# CPU_Power.net
KiCad netlist of a schematic drawn in Altium Designer
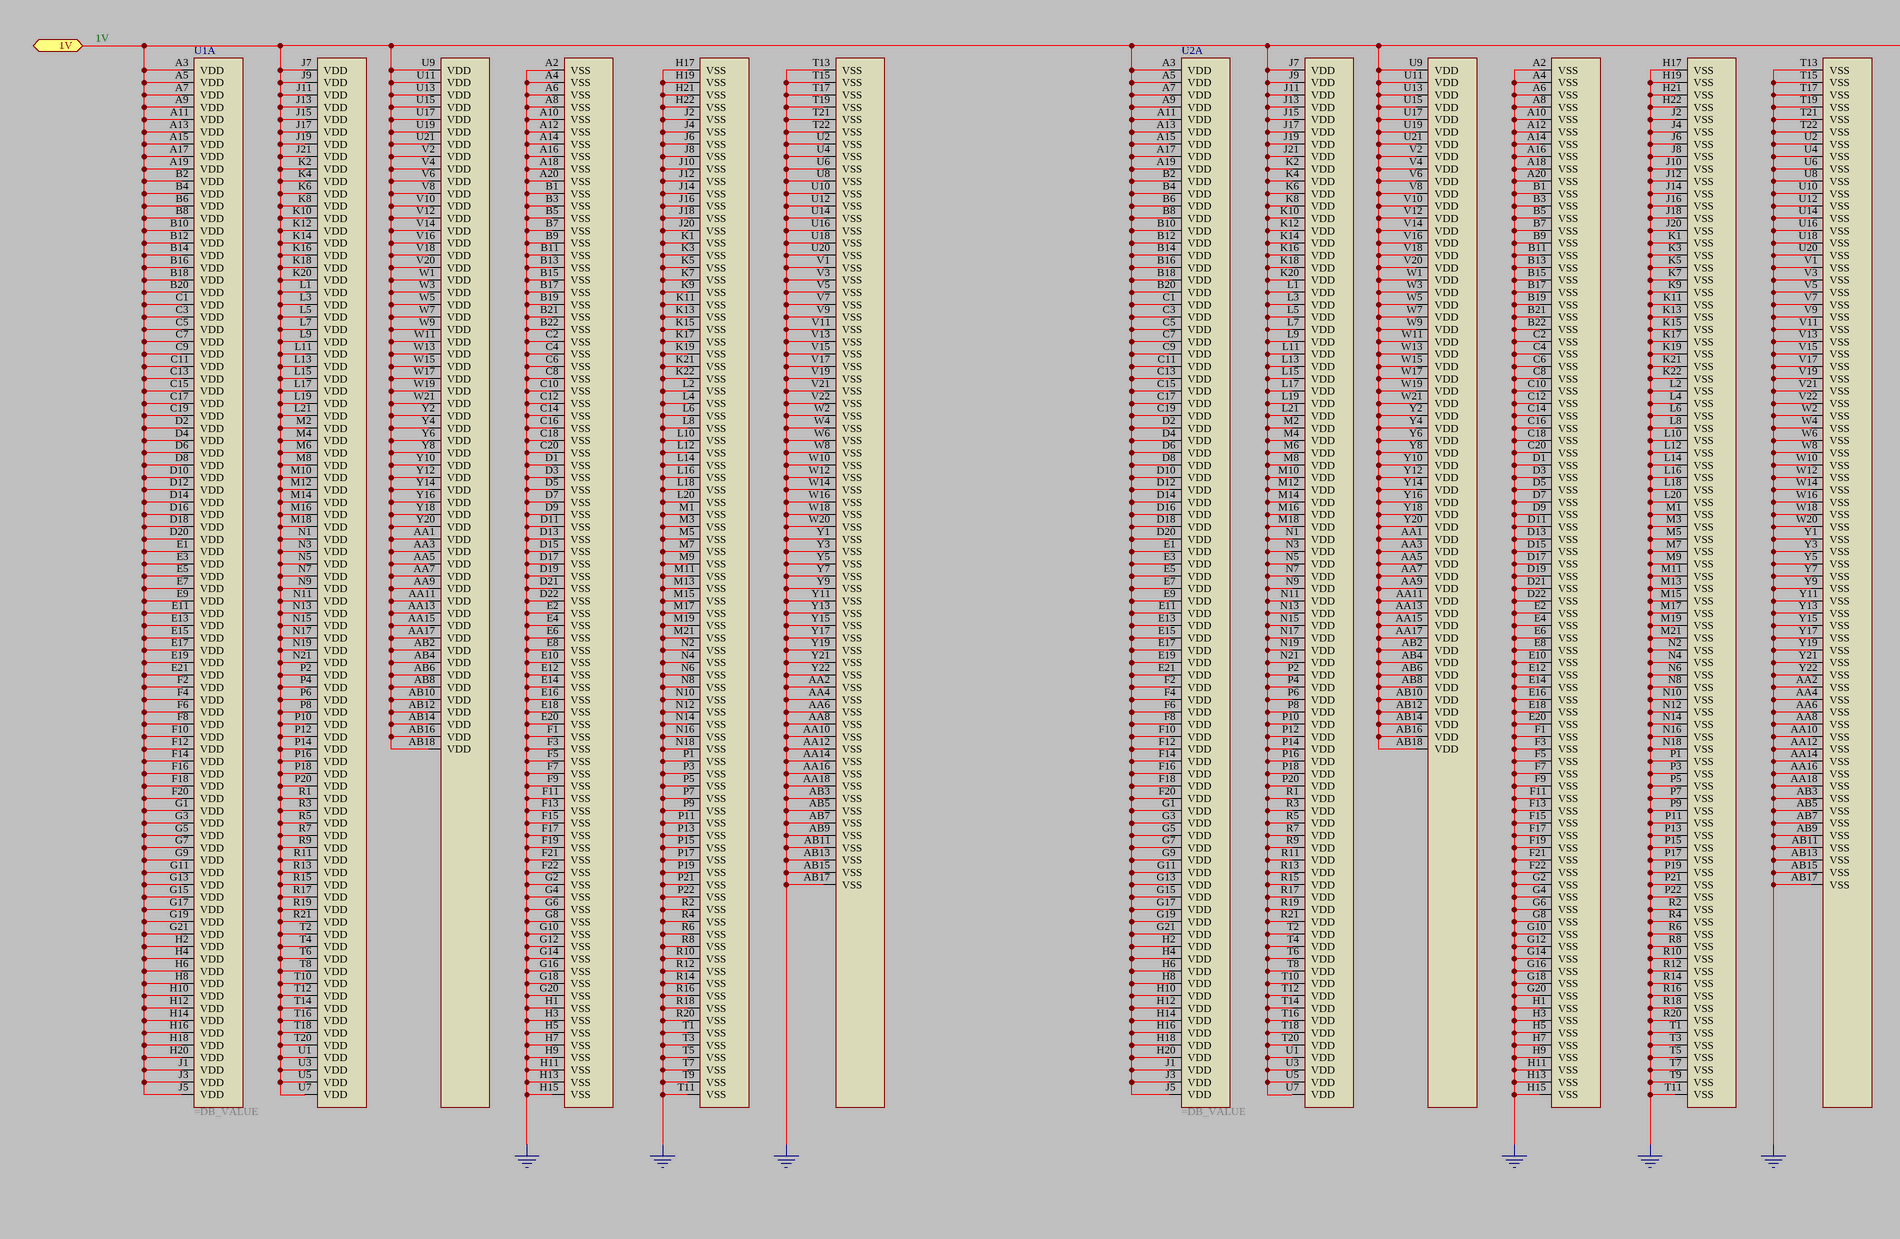
[diagram p0: CPU_Power.SchDoc, top left]
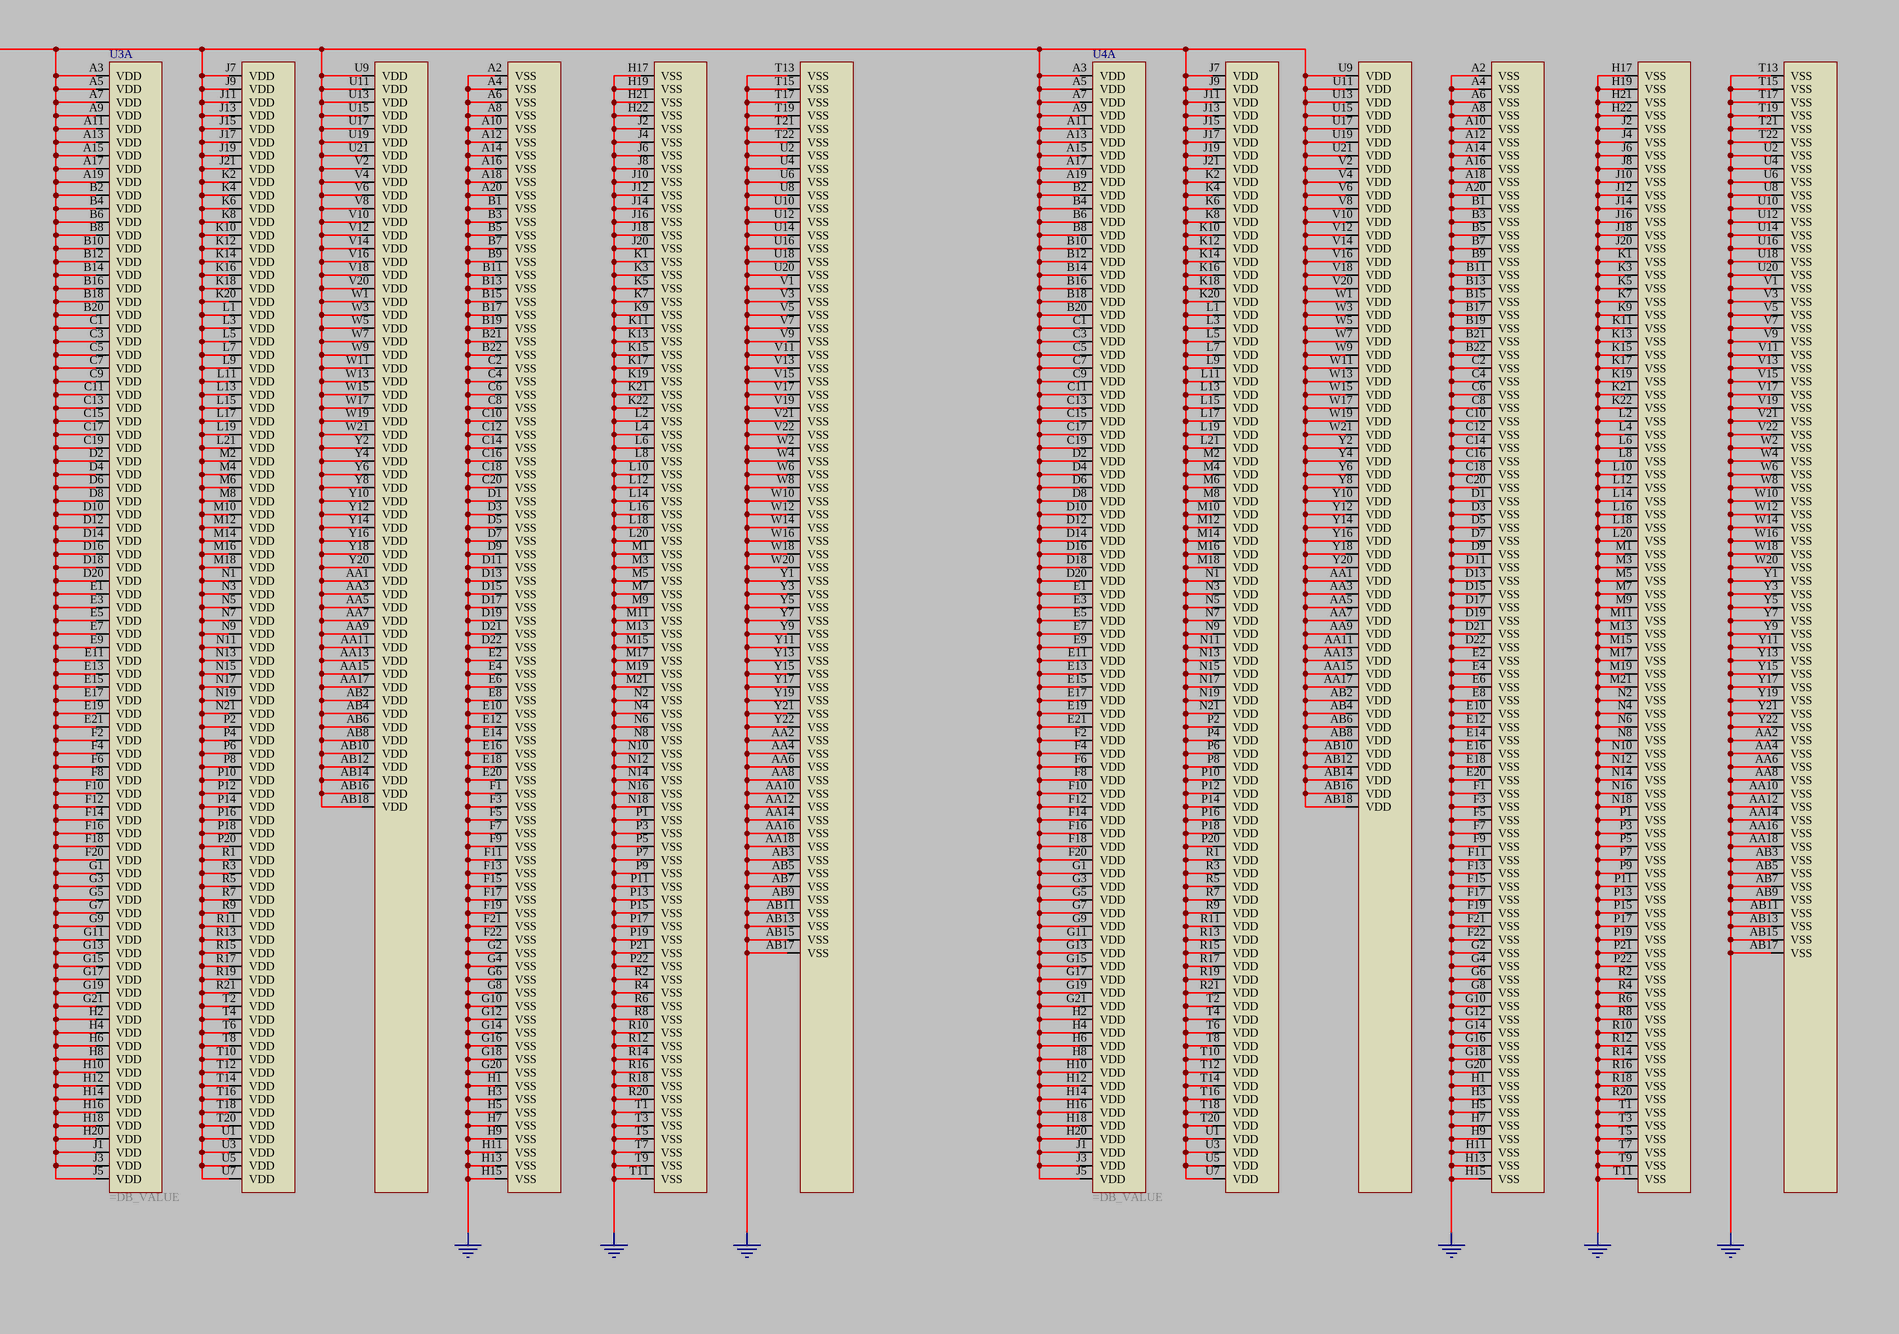
[diagram p1: CPU_Power.SchDoc, top right]
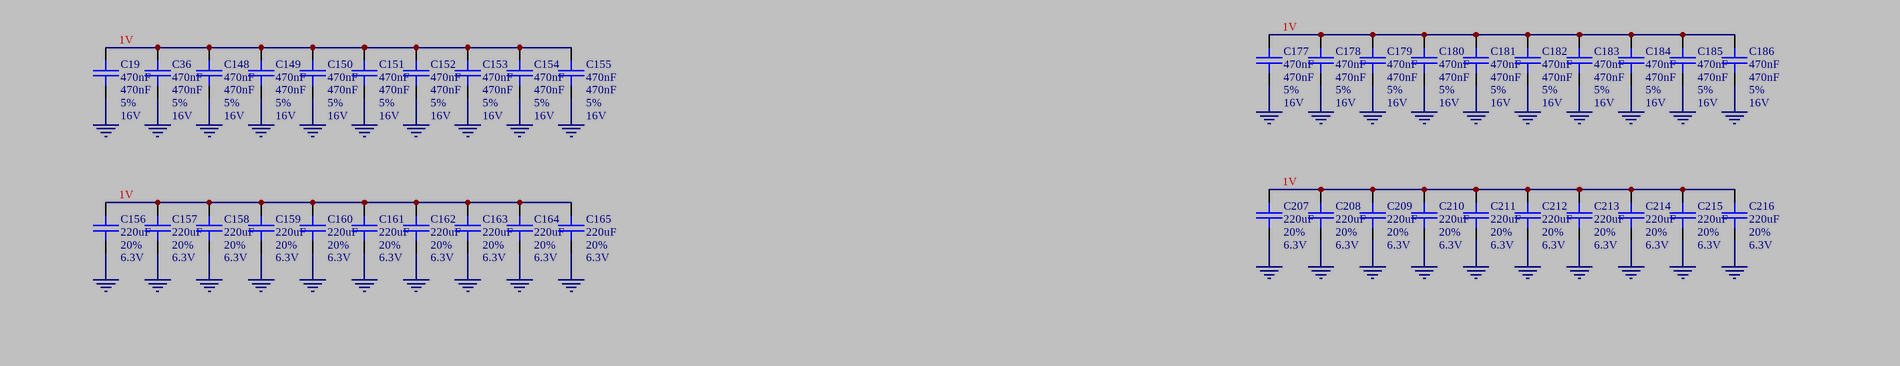
[diagram p2: CPU_Power.SchDoc, bottom left]
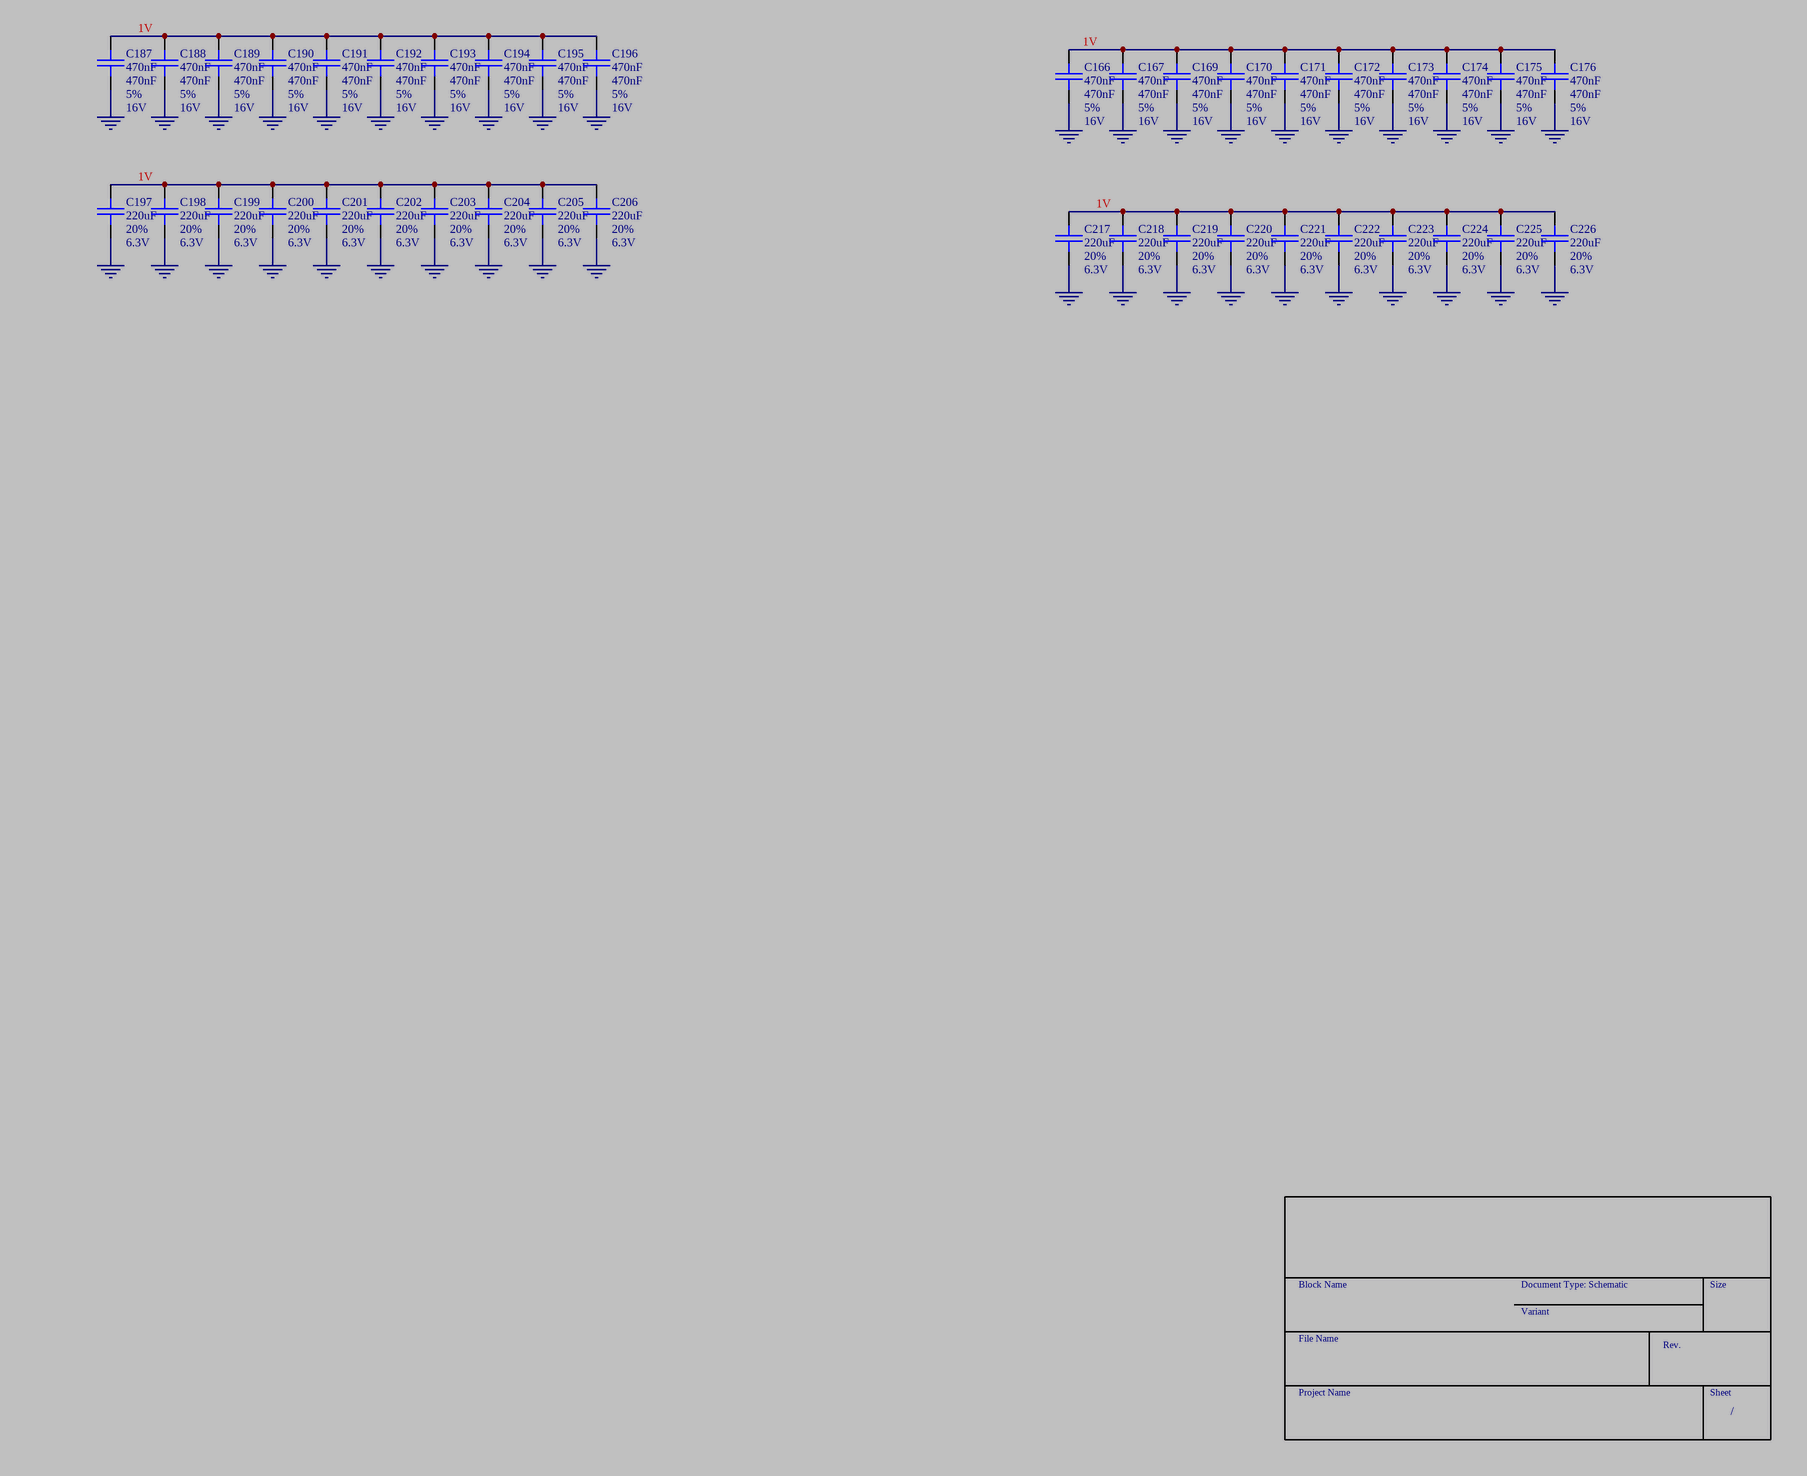
[diagram p3: CPU_Power.SchDoc, bottom right]

(export (version "E")
  (design (tool "Eeschema 10.0.6"))
  (components
    (comp (ref "C19")
      (value "470nF")
      (footprint "SMD_0603_CAPC1608X95N")
      (fields
        (field (name "DB_PART_NUMBER") "CAP000028169")
        (field (name "DB_VALUE") "470nF")
        (field (name "DB_TOLERANCE") "5%")
        (field (name "DB_VOLTAGE") "16V")
        (field (name "DB_MANUFACTURER_PART") "KEMET    C0603C474J4RAC")
      )
      (libsource (lib "Database_Libs1") (part "=DB_VALUE"))
    )
    (comp (ref "C36")
      (value "470nF")
      (footprint "SMD_0603_CAPC1608X95N")
      (fields
        (field (name "DB_PART_NUMBER") "CAP000028169")
        (field (name "DB_VALUE") "470nF")
        (field (name "DB_TOLERANCE") "5%")
        (field (name "DB_VOLTAGE") "16V")
        (field (name "DB_MANUFACTURER_PART") "KEMET    C0603C474J4RAC")
      )
      (libsource (lib "Database_Libs1") (part "=DB_VALUE"))
    )
    (comp (ref "C148")
      (value "470nF")
      (footprint "SMD_0603_CAPC1608X95N")
      (fields
        (field (name "DB_PART_NUMBER") "CAP000028169")
        (field (name "DB_VALUE") "470nF")
        (field (name "DB_TOLERANCE") "5%")
        (field (name "DB_VOLTAGE") "16V")
        (field (name "DB_MANUFACTURER_PART") "KEMET    C0603C474J4RAC")
      )
      (libsource (lib "Database_Libs1") (part "=DB_VALUE"))
    )
    (comp (ref "C149")
      (value "470nF")
      (footprint "SMD_0603_CAPC1608X95N")
      (fields
        (field (name "DB_PART_NUMBER") "CAP000028169")
        (field (name "DB_VALUE") "470nF")
        (field (name "DB_TOLERANCE") "5%")
        (field (name "DB_VOLTAGE") "16V")
        (field (name "DB_MANUFACTURER_PART") "KEMET    C0603C474J4RAC")
      )
      (libsource (lib "Database_Libs1") (part "=DB_VALUE"))
    )
    (comp (ref "C150")
      (value "470nF")
      (footprint "SMD_0603_CAPC1608X95N")
      (fields
        (field (name "DB_PART_NUMBER") "CAP000028169")
        (field (name "DB_VALUE") "470nF")
        (field (name "DB_TOLERANCE") "5%")
        (field (name "DB_VOLTAGE") "16V")
        (field (name "DB_MANUFACTURER_PART") "KEMET    C0603C474J4RAC")
      )
      (libsource (lib "Database_Libs1") (part "=DB_VALUE"))
    )
    (comp (ref "C151")
      (value "470nF")
      (footprint "SMD_0603_CAPC1608X95N")
      (fields
        (field (name "DB_PART_NUMBER") "CAP000028169")
        (field (name "DB_VALUE") "470nF")
        (field (name "DB_TOLERANCE") "5%")
        (field (name "DB_VOLTAGE") "16V")
        (field (name "DB_MANUFACTURER_PART") "KEMET    C0603C474J4RAC")
      )
      (libsource (lib "Database_Libs1") (part "=DB_VALUE"))
    )
    (comp (ref "C152")
      (value "470nF")
      (footprint "SMD_0603_CAPC1608X95N")
      (fields
        (field (name "DB_PART_NUMBER") "CAP000028169")
        (field (name "DB_VALUE") "470nF")
        (field (name "DB_TOLERANCE") "5%")
        (field (name "DB_VOLTAGE") "16V")
        (field (name "DB_MANUFACTURER_PART") "KEMET    C0603C474J4RAC")
      )
      (libsource (lib "Database_Libs1") (part "=DB_VALUE"))
    )
    (comp (ref "C153")
      (value "470nF")
      (footprint "SMD_0603_CAPC1608X95N")
      (fields
        (field (name "DB_PART_NUMBER") "CAP000028169")
        (field (name "DB_VALUE") "470nF")
        (field (name "DB_TOLERANCE") "5%")
        (field (name "DB_VOLTAGE") "16V")
        (field (name "DB_MANUFACTURER_PART") "KEMET    C0603C474J4RAC")
      )
      (libsource (lib "Database_Libs1") (part "=DB_VALUE"))
    )
    (comp (ref "C154")
      (value "470nF")
      (footprint "SMD_0603_CAPC1608X95N")
      (fields
        (field (name "DB_PART_NUMBER") "CAP000028169")
        (field (name "DB_VALUE") "470nF")
        (field (name "DB_TOLERANCE") "5%")
        (field (name "DB_VOLTAGE") "16V")
        (field (name "DB_MANUFACTURER_PART") "KEMET    C0603C474J4RAC")
      )
      (libsource (lib "Database_Libs1") (part "=DB_VALUE"))
    )
    (comp (ref "C155")
      (value "470nF")
      (footprint "SMD_0603_CAPC1608X95N")
      (fields
        (field (name "DB_PART_NUMBER") "CAP000028169")
        (field (name "DB_VALUE") "470nF")
        (field (name "DB_TOLERANCE") "5%")
        (field (name "DB_VOLTAGE") "16V")
        (field (name "DB_MANUFACTURER_PART") "KEMET    C0603C474J4RAC")
      )
      (libsource (lib "Database_Libs1") (part "=DB_VALUE"))
    )
    (comp (ref "C156")
      (value "220uF")
      (footprint "SMD_1210_CAPC3225X279N")
      (fields
        (field (name "DB_PART_NUMBER") "CAP000047355")
        (field (name "DB_VALUE") "220uF")
        (field (name "DB_TOLERANCE") "20%")
        (field (name "DB_VOLTAGE") "6.3V")
        (field (name "DB_MANUFACTURER_PART") "SAMSUNG    CL32A227MQVNNNE")
        (field (name "DB_APPROVED_BY") "VSN")
      )
      (libsource (lib "Database_Libs1") (part "=DB_VALUE"))
    )
    (comp (ref "C157")
      (value "220uF")
      (footprint "SMD_1210_CAPC3225X279N")
      (fields
        (field (name "DB_PART_NUMBER") "CAP000047355")
        (field (name "DB_VALUE") "220uF")
        (field (name "DB_TOLERANCE") "20%")
        (field (name "DB_VOLTAGE") "6.3V")
        (field (name "DB_MANUFACTURER_PART") "SAMSUNG    CL32A227MQVNNNE")
        (field (name "DB_APPROVED_BY") "VSN")
      )
      (libsource (lib "Database_Libs1") (part "=DB_VALUE"))
    )
    (comp (ref "C158")
      (value "220uF")
      (footprint "SMD_1210_CAPC3225X279N")
      (fields
        (field (name "DB_PART_NUMBER") "CAP000047355")
        (field (name "DB_VALUE") "220uF")
        (field (name "DB_TOLERANCE") "20%")
        (field (name "DB_VOLTAGE") "6.3V")
        (field (name "DB_MANUFACTURER_PART") "SAMSUNG    CL32A227MQVNNNE")
        (field (name "DB_APPROVED_BY") "VSN")
      )
      (libsource (lib "Database_Libs1") (part "=DB_VALUE"))
    )
    (comp (ref "C159")
      (value "220uF")
      (footprint "SMD_1210_CAPC3225X279N")
      (fields
        (field (name "DB_PART_NUMBER") "CAP000047355")
        (field (name "DB_VALUE") "220uF")
        (field (name "DB_TOLERANCE") "20%")
        (field (name "DB_VOLTAGE") "6.3V")
        (field (name "DB_MANUFACTURER_PART") "SAMSUNG    CL32A227MQVNNNE")
        (field (name "DB_APPROVED_BY") "VSN")
      )
      (libsource (lib "Database_Libs1") (part "=DB_VALUE"))
    )
    (comp (ref "C160")
      (value "220uF")
      (footprint "SMD_1210_CAPC3225X279N")
      (fields
        (field (name "DB_PART_NUMBER") "CAP000047355")
        (field (name "DB_VALUE") "220uF")
        (field (name "DB_TOLERANCE") "20%")
        (field (name "DB_VOLTAGE") "6.3V")
        (field (name "DB_MANUFACTURER_PART") "SAMSUNG    CL32A227MQVNNNE")
        (field (name "DB_APPROVED_BY") "VSN")
      )
      (libsource (lib "Database_Libs1") (part "=DB_VALUE"))
    )
    (comp (ref "C161")
      (value "220uF")
      (footprint "SMD_1210_CAPC3225X279N")
      (fields
        (field (name "DB_PART_NUMBER") "CAP000047355")
        (field (name "DB_VALUE") "220uF")
        (field (name "DB_TOLERANCE") "20%")
        (field (name "DB_VOLTAGE") "6.3V")
        (field (name "DB_MANUFACTURER_PART") "SAMSUNG    CL32A227MQVNNNE")
        (field (name "DB_APPROVED_BY") "VSN")
      )
      (libsource (lib "Database_Libs1") (part "=DB_VALUE"))
    )
    (comp (ref "C162")
      (value "220uF")
      (footprint "SMD_1210_CAPC3225X279N")
      (fields
        (field (name "DB_PART_NUMBER") "CAP000047355")
        (field (name "DB_VALUE") "220uF")
        (field (name "DB_TOLERANCE") "20%")
        (field (name "DB_VOLTAGE") "6.3V")
        (field (name "DB_MANUFACTURER_PART") "SAMSUNG    CL32A227MQVNNNE")
        (field (name "DB_APPROVED_BY") "VSN")
      )
      (libsource (lib "Database_Libs1") (part "=DB_VALUE"))
    )
    (comp (ref "C163")
      (value "220uF")
      (footprint "SMD_1210_CAPC3225X279N")
      (fields
        (field (name "DB_PART_NUMBER") "CAP000047355")
        (field (name "DB_VALUE") "220uF")
        (field (name "DB_TOLERANCE") "20%")
        (field (name "DB_VOLTAGE") "6.3V")
        (field (name "DB_MANUFACTURER_PART") "SAMSUNG    CL32A227MQVNNNE")
        (field (name "DB_APPROVED_BY") "VSN")
      )
      (libsource (lib "Database_Libs1") (part "=DB_VALUE"))
    )
    (comp (ref "C164")
      (value "220uF")
      (footprint "SMD_1210_CAPC3225X279N")
      (fields
        (field (name "DB_PART_NUMBER") "CAP000047355")
        (field (name "DB_VALUE") "220uF")
        (field (name "DB_TOLERANCE") "20%")
        (field (name "DB_VOLTAGE") "6.3V")
        (field (name "DB_MANUFACTURER_PART") "SAMSUNG    CL32A227MQVNNNE")
        (field (name "DB_APPROVED_BY") "VSN")
      )
      (libsource (lib "Database_Libs1") (part "=DB_VALUE"))
    )
    (comp (ref "C165")
      (value "220uF")
      (footprint "SMD_1210_CAPC3225X279N")
      (fields
        (field (name "DB_PART_NUMBER") "CAP000047355")
        (field (name "DB_VALUE") "220uF")
        (field (name "DB_TOLERANCE") "20%")
        (field (name "DB_VOLTAGE") "6.3V")
        (field (name "DB_MANUFACTURER_PART") "SAMSUNG    CL32A227MQVNNNE")
        (field (name "DB_APPROVED_BY") "VSN")
      )
      (libsource (lib "Database_Libs1") (part "=DB_VALUE"))
    )
    (comp (ref "C166")
      (value "470nF")
      (footprint "SMD_0603_CAPC1608X95N")
      (fields
        (field (name "DB_PART_NUMBER") "CAP000028169")
        (field (name "DB_VALUE") "470nF")
        (field (name "DB_TOLERANCE") "5%")
        (field (name "DB_VOLTAGE") "16V")
        (field (name "DB_MANUFACTURER_PART") "KEMET    C0603C474J4RAC")
      )
      (libsource (lib "Database_Libs1") (part "=DB_VALUE"))
    )
    (comp (ref "C167")
      (value "470nF")
      (footprint "SMD_0603_CAPC1608X95N")
      (fields
        (field (name "DB_PART_NUMBER") "CAP000028169")
        (field (name "DB_VALUE") "470nF")
        (field (name "DB_TOLERANCE") "5%")
        (field (name "DB_VOLTAGE") "16V")
        (field (name "DB_MANUFACTURER_PART") "KEMET    C0603C474J4RAC")
      )
      (libsource (lib "Database_Libs1") (part "=DB_VALUE"))
    )
    (comp (ref "C169")
      (value "470nF")
      (footprint "SMD_0603_CAPC1608X95N")
      (fields
        (field (name "DB_PART_NUMBER") "CAP000028169")
        (field (name "DB_VALUE") "470nF")
        (field (name "DB_TOLERANCE") "5%")
        (field (name "DB_VOLTAGE") "16V")
        (field (name "DB_MANUFACTURER_PART") "KEMET    C0603C474J4RAC")
      )
      (libsource (lib "Database_Libs1") (part "=DB_VALUE"))
    )
    (comp (ref "C170")
      (value "470nF")
      (footprint "SMD_0603_CAPC1608X95N")
      (fields
        (field (name "DB_PART_NUMBER") "CAP000028169")
        (field (name "DB_VALUE") "470nF")
        (field (name "DB_TOLERANCE") "5%")
        (field (name "DB_VOLTAGE") "16V")
        (field (name "DB_MANUFACTURER_PART") "KEMET    C0603C474J4RAC")
      )
      (libsource (lib "Database_Libs1") (part "=DB_VALUE"))
    )
    (comp (ref "C171")
      (value "470nF")
      (footprint "SMD_0603_CAPC1608X95N")
      (fields
        (field (name "DB_PART_NUMBER") "CAP000028169")
        (field (name "DB_VALUE") "470nF")
        (field (name "DB_TOLERANCE") "5%")
        (field (name "DB_VOLTAGE") "16V")
        (field (name "DB_MANUFACTURER_PART") "KEMET    C0603C474J4RAC")
      )
      (libsource (lib "Database_Libs1") (part "=DB_VALUE"))
    )
    (comp (ref "C172")
      (value "470nF")
      (footprint "SMD_0603_CAPC1608X95N")
      (fields
        (field (name "DB_PART_NUMBER") "CAP000028169")
        (field (name "DB_VALUE") "470nF")
        (field (name "DB_TOLERANCE") "5%")
        (field (name "DB_VOLTAGE") "16V")
        (field (name "DB_MANUFACTURER_PART") "KEMET    C0603C474J4RAC")
      )
      (libsource (lib "Database_Libs1") (part "=DB_VALUE"))
    )
    (comp (ref "C173")
      (value "470nF")
      (footprint "SMD_0603_CAPC1608X95N")
      (fields
        (field (name "DB_PART_NUMBER") "CAP000028169")
        (field (name "DB_VALUE") "470nF")
        (field (name "DB_TOLERANCE") "5%")
        (field (name "DB_VOLTAGE") "16V")
        (field (name "DB_MANUFACTURER_PART") "KEMET    C0603C474J4RAC")
      )
      (libsource (lib "Database_Libs1") (part "=DB_VALUE"))
    )
    (comp (ref "C174")
      (value "470nF")
      (footprint "SMD_0603_CAPC1608X95N")
      (fields
        (field (name "DB_PART_NUMBER") "CAP000028169")
        (field (name "DB_VALUE") "470nF")
        (field (name "DB_TOLERANCE") "5%")
        (field (name "DB_VOLTAGE") "16V")
        (field (name "DB_MANUFACTURER_PART") "KEMET    C0603C474J4RAC")
      )
      (libsource (lib "Database_Libs1") (part "=DB_VALUE"))
    )
    (comp (ref "C175")
      (value "470nF")
      (footprint "SMD_0603_CAPC1608X95N")
      (fields
        (field (name "DB_PART_NUMBER") "CAP000028169")
        (field (name "DB_VALUE") "470nF")
        (field (name "DB_TOLERANCE") "5%")
        (field (name "DB_VOLTAGE") "16V")
        (field (name "DB_MANUFACTURER_PART") "KEMET    C0603C474J4RAC")
      )
      (libsource (lib "Database_Libs1") (part "=DB_VALUE"))
    )
    (comp (ref "C176")
      (value "470nF")
      (footprint "SMD_0603_CAPC1608X95N")
      (fields
        (field (name "DB_PART_NUMBER") "CAP000028169")
        (field (name "DB_VALUE") "470nF")
        (field (name "DB_TOLERANCE") "5%")
        (field (name "DB_VOLTAGE") "16V")
        (field (name "DB_MANUFACTURER_PART") "KEMET    C0603C474J4RAC")
      )
      (libsource (lib "Database_Libs1") (part "=DB_VALUE"))
    )
    (comp (ref "C177")
      (value "470nF")
      (footprint "SMD_0603_CAPC1608X95N")
      (fields
        (field (name "DB_PART_NUMBER") "CAP000028169")
        (field (name "DB_VALUE") "470nF")
        (field (name "DB_TOLERANCE") "5%")
        (field (name "DB_VOLTAGE") "16V")
        (field (name "DB_MANUFACTURER_PART") "KEMET    C0603C474J4RAC")
      )
      (libsource (lib "Database_Libs1") (part "=DB_VALUE"))
    )
    (comp (ref "C178")
      (value "470nF")
      (footprint "SMD_0603_CAPC1608X95N")
      (fields
        (field (name "DB_PART_NUMBER") "CAP000028169")
        (field (name "DB_VALUE") "470nF")
        (field (name "DB_TOLERANCE") "5%")
        (field (name "DB_VOLTAGE") "16V")
        (field (name "DB_MANUFACTURER_PART") "KEMET    C0603C474J4RAC")
      )
      (libsource (lib "Database_Libs1") (part "=DB_VALUE"))
    )
    (comp (ref "C179")
      (value "470nF")
      (footprint "SMD_0603_CAPC1608X95N")
      (fields
        (field (name "DB_PART_NUMBER") "CAP000028169")
        (field (name "DB_VALUE") "470nF")
        (field (name "DB_TOLERANCE") "5%")
        (field (name "DB_VOLTAGE") "16V")
        (field (name "DB_MANUFACTURER_PART") "KEMET    C0603C474J4RAC")
      )
      (libsource (lib "Database_Libs1") (part "=DB_VALUE"))
    )
    (comp (ref "C180")
      (value "470nF")
      (footprint "SMD_0603_CAPC1608X95N")
      (fields
        (field (name "DB_PART_NUMBER") "CAP000028169")
        (field (name "DB_VALUE") "470nF")
        (field (name "DB_TOLERANCE") "5%")
        (field (name "DB_VOLTAGE") "16V")
        (field (name "DB_MANUFACTURER_PART") "KEMET    C0603C474J4RAC")
      )
      (libsource (lib "Database_Libs1") (part "=DB_VALUE"))
    )
    (comp (ref "C181")
      (value "470nF")
      (footprint "SMD_0603_CAPC1608X95N")
      (fields
        (field (name "DB_PART_NUMBER") "CAP000028169")
        (field (name "DB_VALUE") "470nF")
        (field (name "DB_TOLERANCE") "5%")
        (field (name "DB_VOLTAGE") "16V")
        (field (name "DB_MANUFACTURER_PART") "KEMET    C0603C474J4RAC")
      )
      (libsource (lib "Database_Libs1") (part "=DB_VALUE"))
    )
    (comp (ref "C182")
      (value "470nF")
      (footprint "SMD_0603_CAPC1608X95N")
      (fields
        (field (name "DB_PART_NUMBER") "CAP000028169")
        (field (name "DB_VALUE") "470nF")
        (field (name "DB_TOLERANCE") "5%")
        (field (name "DB_VOLTAGE") "16V")
        (field (name "DB_MANUFACTURER_PART") "KEMET    C0603C474J4RAC")
      )
      (libsource (lib "Database_Libs1") (part "=DB_VALUE"))
    )
    (comp (ref "C183")
      (value "470nF")
      (footprint "SMD_0603_CAPC1608X95N")
      (fields
        (field (name "DB_PART_NUMBER") "CAP000028169")
        (field (name "DB_VALUE") "470nF")
        (field (name "DB_TOLERANCE") "5%")
        (field (name "DB_VOLTAGE") "16V")
        (field (name "DB_MANUFACTURER_PART") "KEMET    C0603C474J4RAC")
      )
      (libsource (lib "Database_Libs1") (part "=DB_VALUE"))
    )
    (comp (ref "C184")
      (value "470nF")
      (footprint "SMD_0603_CAPC1608X95N")
      (fields
        (field (name "DB_PART_NUMBER") "CAP000028169")
        (field (name "DB_VALUE") "470nF")
        (field (name "DB_TOLERANCE") "5%")
        (field (name "DB_VOLTAGE") "16V")
        (field (name "DB_MANUFACTURER_PART") "KEMET    C0603C474J4RAC")
      )
      (libsource (lib "Database_Libs1") (part "=DB_VALUE"))
    )
    (comp (ref "C185")
      (value "470nF")
      (footprint "SMD_0603_CAPC1608X95N")
      (fields
        (field (name "DB_PART_NUMBER") "CAP000028169")
        (field (name "DB_VALUE") "470nF")
        (field (name "DB_TOLERANCE") "5%")
        (field (name "DB_VOLTAGE") "16V")
        (field (name "DB_MANUFACTURER_PART") "KEMET    C0603C474J4RAC")
      )
      (libsource (lib "Database_Libs1") (part "=DB_VALUE"))
    )
    (comp (ref "C186")
      (value "470nF")
      (footprint "SMD_0603_CAPC1608X95N")
      (fields
        (field (name "DB_PART_NUMBER") "CAP000028169")
        (field (name "DB_VALUE") "470nF")
        (field (name "DB_TOLERANCE") "5%")
        (field (name "DB_VOLTAGE") "16V")
        (field (name "DB_MANUFACTURER_PART") "KEMET    C0603C474J4RAC")
      )
      (libsource (lib "Database_Libs1") (part "=DB_VALUE"))
    )
    (comp (ref "C187")
      (value "470nF")
      (footprint "SMD_0603_CAPC1608X95N")
      (fields
        (field (name "DB_PART_NUMBER") "CAP000028169")
        (field (name "DB_VALUE") "470nF")
        (field (name "DB_TOLERANCE") "5%")
        (field (name "DB_VOLTAGE") "16V")
        (field (name "DB_MANUFACTURER_PART") "KEMET    C0603C474J4RAC")
      )
      (libsource (lib "Database_Libs1") (part "=DB_VALUE"))
    )
    (comp (ref "C188")
      (value "470nF")
      (footprint "SMD_0603_CAPC1608X95N")
      (fields
        (field (name "DB_PART_NUMBER") "CAP000028169")
        (field (name "DB_VALUE") "470nF")
        (field (name "DB_TOLERANCE") "5%")
        (field (name "DB_VOLTAGE") "16V")
        (field (name "DB_MANUFACTURER_PART") "KEMET    C0603C474J4RAC")
      )
      (libsource (lib "Database_Libs1") (part "=DB_VALUE"))
    )
    (comp (ref "C189")
      (value "470nF")
      (footprint "SMD_0603_CAPC1608X95N")
      (fields
        (field (name "DB_PART_NUMBER") "CAP000028169")
        (field (name "DB_VALUE") "470nF")
        (field (name "DB_TOLERANCE") "5%")
        (field (name "DB_VOLTAGE") "16V")
        (field (name "DB_MANUFACTURER_PART") "KEMET    C0603C474J4RAC")
      )
      (libsource (lib "Database_Libs1") (part "=DB_VALUE"))
    )
    (comp (ref "C190")
      (value "470nF")
      (footprint "SMD_0603_CAPC1608X95N")
      (fields
        (field (name "DB_PART_NUMBER") "CAP000028169")
        (field (name "DB_VALUE") "470nF")
        (field (name "DB_TOLERANCE") "5%")
        (field (name "DB_VOLTAGE") "16V")
        (field (name "DB_MANUFACTURER_PART") "KEMET    C0603C474J4RAC")
      )
      (libsource (lib "Database_Libs1") (part "=DB_VALUE"))
    )
    (comp (ref "C191")
      (value "470nF")
      (footprint "SMD_0603_CAPC1608X95N")
      (fields
        (field (name "DB_PART_NUMBER") "CAP000028169")
        (field (name "DB_VALUE") "470nF")
        (field (name "DB_TOLERANCE") "5%")
        (field (name "DB_VOLTAGE") "16V")
        (field (name "DB_MANUFACTURER_PART") "KEMET    C0603C474J4RAC")
      )
      (libsource (lib "Database_Libs1") (part "=DB_VALUE"))
    )
    (comp (ref "C192")
      (value "470nF")
      (footprint "SMD_0603_CAPC1608X95N")
      (fields
        (field (name "DB_PART_NUMBER") "CAP000028169")
        (field (name "DB_VALUE") "470nF")
        (field (name "DB_TOLERANCE") "5%")
        (field (name "DB_VOLTAGE") "16V")
        (field (name "DB_MANUFACTURER_PART") "KEMET    C0603C474J4RAC")
      )
      (libsource (lib "Database_Libs1") (part "=DB_VALUE"))
    )
    (comp (ref "C193")
      (value "470nF")
      (footprint "SMD_0603_CAPC1608X95N")
      (fields
        (field (name "DB_PART_NUMBER") "CAP000028169")
        (field (name "DB_VALUE") "470nF")
        (field (name "DB_TOLERANCE") "5%")
        (field (name "DB_VOLTAGE") "16V")
        (field (name "DB_MANUFACTURER_PART") "KEMET    C0603C474J4RAC")
      )
      (libsource (lib "Database_Libs1") (part "=DB_VALUE"))
    )
    (comp (ref "C194")
      (value "470nF")
      (footprint "SMD_0603_CAPC1608X95N")
      (fields
        (field (name "DB_PART_NUMBER") "CAP000028169")
        (field (name "DB_VALUE") "470nF")
        (field (name "DB_TOLERANCE") "5%")
        (field (name "DB_VOLTAGE") "16V")
        (field (name "DB_MANUFACTURER_PART") "KEMET    C0603C474J4RAC")
      )
      (libsource (lib "Database_Libs1") (part "=DB_VALUE"))
    )
    (comp (ref "C195")
      (value "470nF")
      (footprint "SMD_0603_CAPC1608X95N")
      (fields
        (field (name "DB_PART_NUMBER") "CAP000028169")
        (field (name "DB_VALUE") "470nF")
        (field (name "DB_TOLERANCE") "5%")
        (field (name "DB_VOLTAGE") "16V")
        (field (name "DB_MANUFACTURER_PART") "KEMET    C0603C474J4RAC")
      )
      (libsource (lib "Database_Libs1") (part "=DB_VALUE"))
    )
    (comp (ref "C196")
      (value "470nF")
      (footprint "SMD_0603_CAPC1608X95N")
      (fields
        (field (name "DB_PART_NUMBER") "CAP000028169")
        (field (name "DB_VALUE") "470nF")
        (field (name "DB_TOLERANCE") "5%")
        (field (name "DB_VOLTAGE") "16V")
        (field (name "DB_MANUFACTURER_PART") "KEMET    C0603C474J4RAC")
      )
      (libsource (lib "Database_Libs1") (part "=DB_VALUE"))
    )
    (comp (ref "C197")
      (value "220uF")
      (footprint "SMD_1210_CAPC3225X279N")
      (fields
        (field (name "DB_PART_NUMBER") "CAP000047355")
        (field (name "DB_VALUE") "220uF")
        (field (name "DB_TOLERANCE") "20%")
        (field (name "DB_VOLTAGE") "6.3V")
        (field (name "DB_MANUFACTURER_PART") "SAMSUNG    CL32A227MQVNNNE")
        (field (name "DB_APPROVED_BY") "VSN")
      )
      (libsource (lib "Database_Libs1") (part "=DB_VALUE"))
    )
    (comp (ref "C198")
      (value "220uF")
      (footprint "SMD_1210_CAPC3225X279N")
      (fields
        (field (name "DB_PART_NUMBER") "CAP000047355")
        (field (name "DB_VALUE") "220uF")
        (field (name "DB_TOLERANCE") "20%")
        (field (name "DB_VOLTAGE") "6.3V")
        (field (name "DB_MANUFACTURER_PART") "SAMSUNG    CL32A227MQVNNNE")
        (field (name "DB_APPROVED_BY") "VSN")
      )
      (libsource (lib "Database_Libs1") (part "=DB_VALUE"))
    )
    (comp (ref "C199")
      (value "220uF")
      (footprint "SMD_1210_CAPC3225X279N")
      (fields
        (field (name "DB_PART_NUMBER") "CAP000047355")
        (field (name "DB_VALUE") "220uF")
        (field (name "DB_TOLERANCE") "20%")
        (field (name "DB_VOLTAGE") "6.3V")
        (field (name "DB_MANUFACTURER_PART") "SAMSUNG    CL32A227MQVNNNE")
        (field (name "DB_APPROVED_BY") "VSN")
      )
      (libsource (lib "Database_Libs1") (part "=DB_VALUE"))
    )
    (comp (ref "C200")
      (value "220uF")
      (footprint "SMD_1210_CAPC3225X279N")
      (fields
        (field (name "DB_PART_NUMBER") "CAP000047355")
        (field (name "DB_VALUE") "220uF")
        (field (name "DB_TOLERANCE") "20%")
        (field (name "DB_VOLTAGE") "6.3V")
        (field (name "DB_MANUFACTURER_PART") "SAMSUNG    CL32A227MQVNNNE")
        (field (name "DB_APPROVED_BY") "VSN")
      )
      (libsource (lib "Database_Libs1") (part "=DB_VALUE"))
    )
    (comp (ref "C201")
      (value "220uF")
      (footprint "SMD_1210_CAPC3225X279N")
      (fields
        (field (name "DB_PART_NUMBER") "CAP000047355")
        (field (name "DB_VALUE") "220uF")
        (field (name "DB_TOLERANCE") "20%")
        (field (name "DB_VOLTAGE") "6.3V")
        (field (name "DB_MANUFACTURER_PART") "SAMSUNG    CL32A227MQVNNNE")
        (field (name "DB_APPROVED_BY") "VSN")
      )
      (libsource (lib "Database_Libs1") (part "=DB_VALUE"))
    )
    (comp (ref "C202")
      (value "220uF")
      (footprint "SMD_1210_CAPC3225X279N")
      (fields
        (field (name "DB_PART_NUMBER") "CAP000047355")
        (field (name "DB_VALUE") "220uF")
        (field (name "DB_TOLERANCE") "20%")
        (field (name "DB_VOLTAGE") "6.3V")
        (field (name "DB_MANUFACTURER_PART") "SAMSUNG    CL32A227MQVNNNE")
        (field (name "DB_APPROVED_BY") "VSN")
      )
      (libsource (lib "Database_Libs1") (part "=DB_VALUE"))
    )
    (comp (ref "C203")
      (value "220uF")
      (footprint "SMD_1210_CAPC3225X279N")
      (fields
        (field (name "DB_PART_NUMBER") "CAP000047355")
        (field (name "DB_VALUE") "220uF")
        (field (name "DB_TOLERANCE") "20%")
        (field (name "DB_VOLTAGE") "6.3V")
        (field (name "DB_MANUFACTURER_PART") "SAMSUNG    CL32A227MQVNNNE")
        (field (name "DB_APPROVED_BY") "VSN")
      )
      (libsource (lib "Database_Libs1") (part "=DB_VALUE"))
    )
    (comp (ref "C204")
      (value "220uF")
      (footprint "SMD_1210_CAPC3225X279N")
      (fields
        (field (name "DB_PART_NUMBER") "CAP000047355")
        (field (name "DB_VALUE") "220uF")
        (field (name "DB_TOLERANCE") "20%")
        (field (name "DB_VOLTAGE") "6.3V")
        (field (name "DB_MANUFACTURER_PART") "SAMSUNG    CL32A227MQVNNNE")
        (field (name "DB_APPROVED_BY") "VSN")
      )
      (libsource (lib "Database_Libs1") (part "=DB_VALUE"))
    )
    (comp (ref "C205")
      (value "220uF")
      (footprint "SMD_1210_CAPC3225X279N")
      (fields
        (field (name "DB_PART_NUMBER") "CAP000047355")
        (field (name "DB_VALUE") "220uF")
        (field (name "DB_TOLERANCE") "20%")
        (field (name "DB_VOLTAGE") "6.3V")
        (field (name "DB_MANUFACTURER_PART") "SAMSUNG    CL32A227MQVNNNE")
        (field (name "DB_APPROVED_BY") "VSN")
      )
      (libsource (lib "Database_Libs1") (part "=DB_VALUE"))
    )
    (comp (ref "C206")
      (value "220uF")
      (footprint "SMD_1210_CAPC3225X279N")
      (fields
        (field (name "DB_PART_NUMBER") "CAP000047355")
        (field (name "DB_VALUE") "220uF")
        (field (name "DB_TOLERANCE") "20%")
        (field (name "DB_VOLTAGE") "6.3V")
        (field (name "DB_MANUFACTURER_PART") "SAMSUNG    CL32A227MQVNNNE")
        (field (name "DB_APPROVED_BY") "VSN")
      )
      (libsource (lib "Database_Libs1") (part "=DB_VALUE"))
    )
    (comp (ref "C207")
      (value "220uF")
      (footprint "SMD_1210_CAPC3225X279N")
      (fields
        (field (name "DB_PART_NUMBER") "CAP000047355")
        (field (name "DB_VALUE") "220uF")
        (field (name "DB_TOLERANCE") "20%")
        (field (name "DB_VOLTAGE") "6.3V")
        (field (name "DB_MANUFACTURER_PART") "SAMSUNG    CL32A227MQVNNNE")
        (field (name "DB_APPROVED_BY") "VSN")
      )
      (libsource (lib "Database_Libs1") (part "=DB_VALUE"))
    )
    (comp (ref "C208")
      (value "220uF")
      (footprint "SMD_1210_CAPC3225X279N")
      (fields
        (field (name "DB_PART_NUMBER") "CAP000047355")
        (field (name "DB_VALUE") "220uF")
        (field (name "DB_TOLERANCE") "20%")
        (field (name "DB_VOLTAGE") "6.3V")
        (field (name "DB_MANUFACTURER_PART") "SAMSUNG    CL32A227MQVNNNE")
        (field (name "DB_APPROVED_BY") "VSN")
      )
      (libsource (lib "Database_Libs1") (part "=DB_VALUE"))
    )
    (comp (ref "C209")
      (value "220uF")
      (footprint "SMD_1210_CAPC3225X279N")
      (fields
        (field (name "DB_PART_NUMBER") "CAP000047355")
        (field (name "DB_VALUE") "220uF")
        (field (name "DB_TOLERANCE") "20%")
        (field (name "DB_VOLTAGE") "6.3V")
        (field (name "DB_MANUFACTURER_PART") "SAMSUNG    CL32A227MQVNNNE")
        (field (name "DB_APPROVED_BY") "VSN")
      )
      (libsource (lib "Database_Libs1") (part "=DB_VALUE"))
    )
    (comp (ref "C210")
      (value "220uF")
      (footprint "SMD_1210_CAPC3225X279N")
      (fields
        (field (name "DB_PART_NUMBER") "CAP000047355")
        (field (name "DB_VALUE") "220uF")
        (field (name "DB_TOLERANCE") "20%")
        (field (name "DB_VOLTAGE") "6.3V")
        (field (name "DB_MANUFACTURER_PART") "SAMSUNG    CL32A227MQVNNNE")
        (field (name "DB_APPROVED_BY") "VSN")
      )
      (libsource (lib "Database_Libs1") (part "=DB_VALUE"))
    )
    (comp (ref "C211")
      (value "220uF")
      (footprint "SMD_1210_CAPC3225X279N")
      (fields
        (field (name "DB_PART_NUMBER") "CAP000047355")
        (field (name "DB_VALUE") "220uF")
        (field (name "DB_TOLERANCE") "20%")
        (field (name "DB_VOLTAGE") "6.3V")
        (field (name "DB_MANUFACTURER_PART") "SAMSUNG    CL32A227MQVNNNE")
        (field (name "DB_APPROVED_BY") "VSN")
      )
      (libsource (lib "Database_Libs1") (part "=DB_VALUE"))
    )
    (comp (ref "C212")
      (value "220uF")
      (footprint "SMD_1210_CAPC3225X279N")
      (fields
        (field (name "DB_PART_NUMBER") "CAP000047355")
        (field (name "DB_VALUE") "220uF")
        (field (name "DB_TOLERANCE") "20%")
        (field (name "DB_VOLTAGE") "6.3V")
        (field (name "DB_MANUFACTURER_PART") "SAMSUNG    CL32A227MQVNNNE")
        (field (name "DB_APPROVED_BY") "VSN")
      )
      (libsource (lib "Database_Libs1") (part "=DB_VALUE"))
    )
    (comp (ref "C213")
      (value "220uF")
      (footprint "SMD_1210_CAPC3225X279N")
      (fields
        (field (name "DB_PART_NUMBER") "CAP000047355")
        (field (name "DB_VALUE") "220uF")
        (field (name "DB_TOLERANCE") "20%")
        (field (name "DB_VOLTAGE") "6.3V")
        (field (name "DB_MANUFACTURER_PART") "SAMSUNG    CL32A227MQVNNNE")
        (field (name "DB_APPROVED_BY") "VSN")
      )
      (libsource (lib "Database_Libs1") (part "=DB_VALUE"))
    )
    (comp (ref "C214")
      (value "220uF")
      (footprint "SMD_1210_CAPC3225X279N")
      (fields
        (field (name "DB_PART_NUMBER") "CAP000047355")
        (field (name "DB_VALUE") "220uF")
        (field (name "DB_TOLERANCE") "20%")
        (field (name "DB_VOLTAGE") "6.3V")
        (field (name "DB_MANUFACTURER_PART") "SAMSUNG    CL32A227MQVNNNE")
        (field (name "DB_APPROVED_BY") "VSN")
      )
      (libsource (lib "Database_Libs1") (part "=DB_VALUE"))
    )
    (comp (ref "C215")
      (value "220uF")
      (footprint "SMD_1210_CAPC3225X279N")
      (fields
        (field (name "DB_PART_NUMBER") "CAP000047355")
        (field (name "DB_VALUE") "220uF")
        (field (name "DB_TOLERANCE") "20%")
        (field (name "DB_VOLTAGE") "6.3V")
        (field (name "DB_MANUFACTURER_PART") "SAMSUNG    CL32A227MQVNNNE")
        (field (name "DB_APPROVED_BY") "VSN")
      )
      (libsource (lib "Database_Libs1") (part "=DB_VALUE"))
    )
    (comp (ref "C216")
      (value "220uF")
      (footprint "SMD_1210_CAPC3225X279N")
      (fields
        (field (name "DB_PART_NUMBER") "CAP000047355")
        (field (name "DB_VALUE") "220uF")
        (field (name "DB_TOLERANCE") "20%")
        (field (name "DB_VOLTAGE") "6.3V")
        (field (name "DB_MANUFACTURER_PART") "SAMSUNG    CL32A227MQVNNNE")
        (field (name "DB_APPROVED_BY") "VSN")
      )
      (libsource (lib "Database_Libs1") (part "=DB_VALUE"))
    )
    (comp (ref "C217")
      (value "220uF")
      (footprint "SMD_1210_CAPC3225X279N")
      (fields
        (field (name "DB_PART_NUMBER") "CAP000047355")
        (field (name "DB_VALUE") "220uF")
        (field (name "DB_TOLERANCE") "20%")
        (field (name "DB_VOLTAGE") "6.3V")
        (field (name "DB_MANUFACTURER_PART") "SAMSUNG    CL32A227MQVNNNE")
        (field (name "DB_APPROVED_BY") "VSN")
      )
      (libsource (lib "Database_Libs1") (part "=DB_VALUE"))
    )
    (comp (ref "C218")
      (value "220uF")
      (footprint "SMD_1210_CAPC3225X279N")
      (fields
        (field (name "DB_PART_NUMBER") "CAP000047355")
        (field (name "DB_VALUE") "220uF")
        (field (name "DB_TOLERANCE") "20%")
        (field (name "DB_VOLTAGE") "6.3V")
        (field (name "DB_MANUFACTURER_PART") "SAMSUNG    CL32A227MQVNNNE")
        (field (name "DB_APPROVED_BY") "VSN")
      )
      (libsource (lib "Database_Libs1") (part "=DB_VALUE"))
    )
    (comp (ref "C219")
      (value "220uF")
      (footprint "SMD_1210_CAPC3225X279N")
      (fields
        (field (name "DB_PART_NUMBER") "CAP000047355")
        (field (name "DB_VALUE") "220uF")
        (field (name "DB_TOLERANCE") "20%")
        (field (name "DB_VOLTAGE") "6.3V")
        (field (name "DB_MANUFACTURER_PART") "SAMSUNG    CL32A227MQVNNNE")
        (field (name "DB_APPROVED_BY") "VSN")
      )
      (libsource (lib "Database_Libs1") (part "=DB_VALUE"))
    )
    (comp (ref "C220")
      (value "220uF")
      (footprint "SMD_1210_CAPC3225X279N")
      (fields
        (field (name "DB_PART_NUMBER") "CAP000047355")
        (field (name "DB_VALUE") "220uF")
        (field (name "DB_TOLERANCE") "20%")
        (field (name "DB_VOLTAGE") "6.3V")
        (field (name "DB_MANUFACTURER_PART") "SAMSUNG    CL32A227MQVNNNE")
        (field (name "DB_APPROVED_BY") "VSN")
      )
      (libsource (lib "Database_Libs1") (part "=DB_VALUE"))
    )
    (comp (ref "C221")
      (value "220uF")
      (footprint "SMD_1210_CAPC3225X279N")
      (fields
        (field (name "DB_PART_NUMBER") "CAP000047355")
        (field (name "DB_VALUE") "220uF")
        (field (name "DB_TOLERANCE") "20%")
        (field (name "DB_VOLTAGE") "6.3V")
        (field (name "DB_MANUFACTURER_PART") "SAMSUNG    CL32A227MQVNNNE")
        (field (name "DB_APPROVED_BY") "VSN")
      )
      (libsource (lib "Database_Libs1") (part "=DB_VALUE"))
    )
    (comp (ref "C222")
      (value "220uF")
      (footprint "SMD_1210_CAPC3225X279N")
      (fields
        (field (name "DB_PART_NUMBER") "CAP000047355")
        (field (name "DB_VALUE") "220uF")
        (field (name "DB_TOLERANCE") "20%")
        (field (name "DB_VOLTAGE") "6.3V")
        (field (name "DB_MANUFACTURER_PART") "SAMSUNG    CL32A227MQVNNNE")
        (field (name "DB_APPROVED_BY") "VSN")
      )
      (libsource (lib "Database_Libs1") (part "=DB_VALUE"))
    )
    (comp (ref "C223")
      (value "220uF")
      (footprint "SMD_1210_CAPC3225X279N")
      (fields
        (field (name "DB_PART_NUMBER") "CAP000047355")
        (field (name "DB_VALUE") "220uF")
        (field (name "DB_TOLERANCE") "20%")
        (field (name "DB_VOLTAGE") "6.3V")
        (field (name "DB_MANUFACTURER_PART") "SAMSUNG    CL32A227MQVNNNE")
        (field (name "DB_APPROVED_BY") "VSN")
      )
      (libsource (lib "Database_Libs1") (part "=DB_VALUE"))
    )
    (comp (ref "C224")
      (value "220uF")
      (footprint "SMD_1210_CAPC3225X279N")
      (fields
        (field (name "DB_PART_NUMBER") "CAP000047355")
        (field (name "DB_VALUE") "220uF")
        (field (name "DB_TOLERANCE") "20%")
        (field (name "DB_VOLTAGE") "6.3V")
        (field (name "DB_MANUFACTURER_PART") "SAMSUNG    CL32A227MQVNNNE")
        (field (name "DB_APPROVED_BY") "VSN")
      )
      (libsource (lib "Database_Libs1") (part "=DB_VALUE"))
    )
    (comp (ref "C225")
      (value "220uF")
      (footprint "SMD_1210_CAPC3225X279N")
      (fields
        (field (name "DB_PART_NUMBER") "CAP000047355")
        (field (name "DB_VALUE") "220uF")
        (field (name "DB_TOLERANCE") "20%")
        (field (name "DB_VOLTAGE") "6.3V")
        (field (name "DB_MANUFACTURER_PART") "SAMSUNG    CL32A227MQVNNNE")
        (field (name "DB_APPROVED_BY") "VSN")
      )
      (libsource (lib "Database_Libs1") (part "=DB_VALUE"))
    )
    (comp (ref "C226")
      (value "220uF")
      (footprint "SMD_1210_CAPC3225X279N")
      (fields
        (field (name "DB_PART_NUMBER") "CAP000047355")
        (field (name "DB_VALUE") "220uF")
        (field (name "DB_TOLERANCE") "20%")
        (field (name "DB_VOLTAGE") "6.3V")
        (field (name "DB_MANUFACTURER_PART") "SAMSUNG    CL32A227MQVNNNE")
        (field (name "DB_APPROVED_BY") "VSN")
      )
      (libsource (lib "Database_Libs1") (part "=DB_VALUE"))
    )
    (comp (ref "U1")
      (value "~")
      (footprint "SMD_BGA480C80P22X22")
      (libsource (lib "RockerBox") (part "=DB_VALUE"))
    )
    (comp (ref "U2")
      (value "~")
      (footprint "SMD_BGA480C80P22X22")
      (libsource (lib "RockerBox") (part "=DB_VALUE"))
    )
    (comp (ref "U3")
      (value "~")
      (footprint "SMD_BGA480C80P22X22")
      (libsource (lib "RockerBox") (part "=DB_VALUE"))
    )
    (comp (ref "U4")
      (value "~")
      (footprint "SMD_BGA480C80P22X22")
      (libsource (lib "RockerBox") (part "=DB_VALUE"))
    )
  )
  (nets
    (net (code "1") (name "/1V") (class "Default")
      (node (ref "C148") (pin "2") (pinfunction "2_2") (pintype "passive"))
      (node (ref "C149") (pin "2") (pinfunction "2_2") (pintype "passive"))
      (node (ref "C150") (pin "2") (pinfunction "2_2") (pintype "passive"))
      (node (ref "C151") (pin "2") (pinfunction "2_2") (pintype "passive"))
      (node (ref "C152") (pin "2") (pinfunction "2_2") (pintype "passive"))
      (node (ref "C153") (pin "2") (pinfunction "2_2") (pintype "passive"))
      (node (ref "C154") (pin "2") (pinfunction "2_2") (pintype "passive"))
      (node (ref "C155") (pin "2") (pinfunction "2_2") (pintype "passive"))
      (node (ref "C156") (pin "2") (pinfunction "2_2") (pintype "passive"))
      (node (ref "C157") (pin "2") (pinfunction "2_2") (pintype "passive"))
      (node (ref "C158") (pin "2") (pinfunction "2_2") (pintype "passive"))
      (node (ref "C159") (pin "2") (pinfunction "2_2") (pintype "passive"))
      (node (ref "C160") (pin "2") (pinfunction "2_2") (pintype "passive"))
      (node (ref "C161") (pin "2") (pinfunction "2_2") (pintype "passive"))
      (node (ref "C162") (pin "2") (pinfunction "2_2") (pintype "passive"))
      (node (ref "C163") (pin "2") (pinfunction "2_2") (pintype "passive"))
      (node (ref "C164") (pin "2") (pinfunction "2_2") (pintype "passive"))
      (node (ref "C165") (pin "2") (pinfunction "2_2") (pintype "passive"))
      (node (ref "C166") (pin "2") (pinfunction "2_2") (pintype "passive"))
      (node (ref "C167") (pin "2") (pinfunction "2_2") (pintype "passive"))
      (node (ref "C169") (pin "2") (pinfunction "2_2") (pintype "passive"))
      (node (ref "C170") (pin "2") (pinfunction "2_2") (pintype "passive"))
      (node (ref "C171") (pin "2") (pinfunction "2_2") (pintype "passive"))
      (node (ref "C172") (pin "2") (pinfunction "2_2") (pintype "passive"))
      (node (ref "C173") (pin "2") (pinfunction "2_2") (pintype "passive"))
      (node (ref "C174") (pin "2") (pinfunction "2_2") (pintype "passive"))
      (node (ref "C175") (pin "2") (pinfunction "2_2") (pintype "passive"))
      (node (ref "C176") (pin "2") (pinfunction "2_2") (pintype "passive"))
      (node (ref "C177") (pin "2") (pinfunction "2_2") (pintype "passive"))
      (node (ref "C178") (pin "2") (pinfunction "2_2") (pintype "passive"))
      (node (ref "C179") (pin "2") (pinfunction "2_2") (pintype "passive"))
      (node (ref "C180") (pin "2") (pinfunction "2_2") (pintype "passive"))
      (node (ref "C181") (pin "2") (pinfunction "2_2") (pintype "passive"))
      (node (ref "C182") (pin "2") (pinfunction "2_2") (pintype "passive"))
      (node (ref "C183") (pin "2") (pinfunction "2_2") (pintype "passive"))
      (node (ref "C184") (pin "2") (pinfunction "2_2") (pintype "passive"))
      (node (ref "C185") (pin "2") (pinfunction "2_2") (pintype "passive"))
      (node (ref "C186") (pin "2") (pinfunction "2_2") (pintype "passive"))
      (node (ref "C187") (pin "2") (pinfunction "2_2") (pintype "passive"))
      (node (ref "C188") (pin "2") (pinfunction "2_2") (pintype "passive"))
      (node (ref "C189") (pin "2") (pinfunction "2_2") (pintype "passive"))
      (node (ref "C19") (pin "2") (pinfunction "2_2") (pintype "passive"))
      (node (ref "C190") (pin "2") (pinfunction "2_2") (pintype "passive"))
      (node (ref "C191") (pin "2") (pinfunction "2_2") (pintype "passive"))
      (node (ref "C192") (pin "2") (pinfunction "2_2") (pintype "passive"))
      (node (ref "C193") (pin "2") (pinfunction "2_2") (pintype "passive"))
      (node (ref "C194") (pin "2") (pinfunction "2_2") (pintype "passive"))
      (node (ref "C195") (pin "2") (pinfunction "2_2") (pintype "passive"))
      (node (ref "C196") (pin "2") (pinfunction "2_2") (pintype "passive"))
      (node (ref "C197") (pin "2") (pinfunction "2_2") (pintype "passive"))
      (node (ref "C198") (pin "2") (pinfunction "2_2") (pintype "passive"))
      (node (ref "C199") (pin "2") (pinfunction "2_2") (pintype "passive"))
      (node (ref "C200") (pin "2") (pinfunction "2_2") (pintype "passive"))
      (node (ref "C201") (pin "2") (pinfunction "2_2") (pintype "passive"))
      (node (ref "C202") (pin "2") (pinfunction "2_2") (pintype "passive"))
      (node (ref "C203") (pin "2") (pinfunction "2_2") (pintype "passive"))
      (node (ref "C204") (pin "2") (pinfunction "2_2") (pintype "passive"))
      (node (ref "C205") (pin "2") (pinfunction "2_2") (pintype "passive"))
      (node (ref "C206") (pin "2") (pinfunction "2_2") (pintype "passive"))
      (node (ref "C207") (pin "2") (pinfunction "2_2") (pintype "passive"))
      (node (ref "C208") (pin "2") (pinfunction "2_2") (pintype "passive"))
      (node (ref "C209") (pin "2") (pinfunction "2_2") (pintype "passive"))
      (node (ref "C210") (pin "2") (pinfunction "2_2") (pintype "passive"))
      (node (ref "C211") (pin "2") (pinfunction "2_2") (pintype "passive"))
      (node (ref "C212") (pin "2") (pinfunction "2_2") (pintype "passive"))
      (node (ref "C213") (pin "2") (pinfunction "2_2") (pintype "passive"))
      (node (ref "C214") (pin "2") (pinfunction "2_2") (pintype "passive"))
      (node (ref "C215") (pin "2") (pinfunction "2_2") (pintype "passive"))
      (node (ref "C216") (pin "2") (pinfunction "2_2") (pintype "passive"))
      (node (ref "C217") (pin "2") (pinfunction "2_2") (pintype "passive"))
      (node (ref "C218") (pin "2") (pinfunction "2_2") (pintype "passive"))
      (node (ref "C219") (pin "2") (pinfunction "2_2") (pintype "passive"))
      (node (ref "C220") (pin "2") (pinfunction "2_2") (pintype "passive"))
      (node (ref "C221") (pin "2") (pinfunction "2_2") (pintype "passive"))
      (node (ref "C222") (pin "2") (pinfunction "2_2") (pintype "passive"))
      (node (ref "C223") (pin "2") (pinfunction "2_2") (pintype "passive"))
      (node (ref "C224") (pin "2") (pinfunction "2_2") (pintype "passive"))
      (node (ref "C225") (pin "2") (pinfunction "2_2") (pintype "passive"))
      (node (ref "C226") (pin "2") (pinfunction "2_2") (pintype "passive"))
      (node (ref "C36") (pin "2") (pinfunction "2_2") (pintype "passive"))
      (node (ref "U1") (pin "A11") (pinfunction "VDD_A11") (pintype "passive"))
      (node (ref "U1") (pin "A13") (pinfunction "VDD_A13") (pintype "passive"))
      (node (ref "U1") (pin "A15") (pinfunction "VDD_A15") (pintype "passive"))
      (node (ref "U1") (pin "A17") (pinfunction "VDD_A17") (pintype "passive"))
      (node (ref "U1") (pin "A19") (pinfunction "VDD_A19") (pintype "passive"))
      (node (ref "U1") (pin "A3") (pinfunction "VDD_A3") (pintype "passive"))
      (node (ref "U1") (pin "A5") (pinfunction "VDD_A5") (pintype "passive"))
      (node (ref "U1") (pin "A7") (pinfunction "VDD_A7") (pintype "passive"))
      (node (ref "U1") (pin "A9") (pinfunction "VDD_A9") (pintype "passive"))
      (node (ref "U1") (pin "AA1") (pinfunction "VDD_AA1") (pintype "passive"))
      (node (ref "U1") (pin "AA11") (pinfunction "VDD_AA11") (pintype "passive"))
      (node (ref "U1") (pin "AA13") (pinfunction "VDD_AA13") (pintype "passive"))
      (node (ref "U1") (pin "AA15") (pinfunction "VDD_AA15") (pintype "passive"))
      (node (ref "U1") (pin "AA17") (pinfunction "VDD_AA17") (pintype "passive"))
      (node (ref "U1") (pin "AA3") (pinfunction "VDD_AA3") (pintype "passive"))
      (node (ref "U1") (pin "AA5") (pinfunction "VDD_AA5") (pintype "passive"))
      (node (ref "U1") (pin "AA7") (pinfunction "VDD_AA7") (pintype "passive"))
      (node (ref "U1") (pin "AA9") (pinfunction "VDD_AA9") (pintype "passive"))
      (node (ref "U1") (pin "AB10") (pinfunction "VDD_AB10") (pintype "passive"))
      (node (ref "U1") (pin "AB12") (pinfunction "VDD_AB12") (pintype "passive"))
      (node (ref "U1") (pin "AB14") (pinfunction "VDD_AB14") (pintype "passive"))
      (node (ref "U1") (pin "AB16") (pinfunction "VDD_AB16") (pintype "passive"))
      (node (ref "U1") (pin "AB18") (pinfunction "VDD_AB18") (pintype "passive"))
      (node (ref "U1") (pin "AB2") (pinfunction "VDD_AB2") (pintype "passive"))
      (node (ref "U1") (pin "AB4") (pinfunction "VDD_AB4") (pintype "passive"))
      (node (ref "U1") (pin "AB6") (pinfunction "VDD_AB6") (pintype "passive"))
      (node (ref "U1") (pin "AB8") (pinfunction "VDD_AB8") (pintype "passive"))
      (node (ref "U1") (pin "B10") (pinfunction "VDD_B10") (pintype "passive"))
      (node (ref "U1") (pin "B12") (pinfunction "VDD_B12") (pintype "passive"))
      (node (ref "U1") (pin "B14") (pinfunction "VDD_B14") (pintype "passive"))
      (node (ref "U1") (pin "B16") (pinfunction "VDD_B16") (pintype "passive"))
      (node (ref "U1") (pin "B18") (pinfunction "VDD_B18") (pintype "passive"))
      (node (ref "U1") (pin "B2") (pinfunction "VDD_B2") (pintype "passive"))
      (node (ref "U1") (pin "B20") (pinfunction "VDD_B20") (pintype "passive"))
      (node (ref "U1") (pin "B4") (pinfunction "VDD_B4") (pintype "passive"))
      (node (ref "U1") (pin "B6") (pinfunction "VDD_B6") (pintype "passive"))
      (node (ref "U1") (pin "B8") (pinfunction "VDD_B8") (pintype "passive"))
      (node (ref "U1") (pin "C1") (pinfunction "VDD_C1") (pintype "passive"))
      (node (ref "U1") (pin "C11") (pinfunction "VDD_C11") (pintype "passive"))
      (node (ref "U1") (pin "C13") (pinfunction "VDD_C13") (pintype "passive"))
      (node (ref "U1") (pin "C15") (pinfunction "VDD_C15") (pintype "passive"))
      (node (ref "U1") (pin "C17") (pinfunction "VDD_C17") (pintype "passive"))
      (node (ref "U1") (pin "C19") (pinfunction "VDD_C19") (pintype "passive"))
      (node (ref "U1") (pin "C3") (pinfunction "VDD_C3") (pintype "passive"))
      (node (ref "U1") (pin "C5") (pinfunction "VDD_C5") (pintype "passive"))
      (node (ref "U1") (pin "C7") (pinfunction "VDD_C7") (pintype "passive"))
      (node (ref "U1") (pin "C9") (pinfunction "VDD_C9") (pintype "passive"))
      (node (ref "U1") (pin "D10") (pinfunction "VDD_D10") (pintype "passive"))
      (node (ref "U1") (pin "D12") (pinfunction "VDD_D12") (pintype "passive"))
      (node (ref "U1") (pin "D14") (pinfunction "VDD_D14") (pintype "passive"))
      (node (ref "U1") (pin "D16") (pinfunction "VDD_D16") (pintype "passive"))
      (node (ref "U1") (pin "D18") (pinfunction "VDD_D18") (pintype "passive"))
      (node (ref "U1") (pin "D2") (pinfunction "VDD_D2") (pintype "passive"))
      (node (ref "U1") (pin "D20") (pinfunction "VDD_D20") (pintype "passive"))
      (node (ref "U1") (pin "D4") (pinfunction "VDD_D4") (pintype "passive"))
      (node (ref "U1") (pin "D6") (pinfunction "VDD_D6") (pintype "passive"))
      (node (ref "U1") (pin "D8") (pinfunction "VDD_D8") (pintype "passive"))
      (node (ref "U1") (pin "E1") (pinfunction "VDD_E1") (pintype "passive"))
      (node (ref "U1") (pin "E11") (pinfunction "VDD_E11") (pintype "passive"))
      (node (ref "U1") (pin "E13") (pinfunction "VDD_E13") (pintype "passive"))
      (node (ref "U1") (pin "E15") (pinfunction "VDD_E15") (pintype "passive"))
      (node (ref "U1") (pin "E17") (pinfunction "VDD_E17") (pintype "passive"))
      (node (ref "U1") (pin "E19") (pinfunction "VDD_E19") (pintype "passive"))
      (node (ref "U1") (pin "E21") (pinfunction "VDD_E21") (pintype "passive"))
      (node (ref "U1") (pin "E3") (pinfunction "VDD_E3") (pintype "passive"))
      (node (ref "U1") (pin "E5") (pinfunction "VDD_E5") (pintype "passive"))
      (node (ref "U1") (pin "E7") (pinfunction "VDD_E7") (pintype "passive"))
      (node (ref "U1") (pin "E9") (pinfunction "VDD_E9") (pintype "passive"))
      (node (ref "U1") (pin "F10") (pinfunction "VDD_F10") (pintype "passive"))
      (node (ref "U1") (pin "F12") (pinfunction "VDD_F12") (pintype "passive"))
      (node (ref "U1") (pin "F14") (pinfunction "VDD_F14") (pintype "passive"))
      (node (ref "U1") (pin "F16") (pinfunction "VDD_F16") (pintype "passive"))
      (node (ref "U1") (pin "F18") (pinfunction "VDD_F18") (pintype "passive"))
      (node (ref "U1") (pin "F2") (pinfunction "VDD_F2") (pintype "passive"))
      (node (ref "U1") (pin "F20") (pinfunction "VDD_F20") (pintype "passive"))
      (node (ref "U1") (pin "F4") (pinfunction "VDD_F4") (pintype "passive"))
      (node (ref "U1") (pin "F6") (pinfunction "VDD_F6") (pintype "passive"))
      (node (ref "U1") (pin "F8") (pinfunction "VDD_F8") (pintype "passive"))
      (node (ref "U1") (pin "G1") (pinfunction "VDD_G1") (pintype "passive"))
      (node (ref "U1") (pin "G11") (pinfunction "VDD_G11") (pintype "passive"))
      (node (ref "U1") (pin "G13") (pinfunction "VDD_G13") (pintype "passive"))
      (node (ref "U1") (pin "G15") (pinfunction "VDD_G15") (pintype "passive"))
      (node (ref "U1") (pin "G17") (pinfunction "VDD_G17") (pintype "passive"))
      (node (ref "U1") (pin "G19") (pinfunction "VDD_G19") (pintype "passive"))
      (node (ref "U1") (pin "G21") (pinfunction "VDD_G21") (pintype "passive"))
      (node (ref "U1") (pin "G3") (pinfunction "VDD_G3") (pintype "passive"))
      (node (ref "U1") (pin "G5") (pinfunction "VDD_G5") (pintype "passive"))
      (node (ref "U1") (pin "G7") (pinfunction "VDD_G7") (pintype "passive"))
      (node (ref "U1") (pin "G9") (pinfunction "VDD_G9") (pintype "passive"))
      (node (ref "U1") (pin "H10") (pinfunction "VDD_H10") (pintype "passive"))
      (node (ref "U1") (pin "H12") (pinfunction "VDD_H12") (pintype "passive"))
      (node (ref "U1") (pin "H14") (pinfunction "VDD_H14") (pintype "passive"))
      (node (ref "U1") (pin "H16") (pinfunction "VDD_H16") (pintype "passive"))
      (node (ref "U1") (pin "H18") (pinfunction "VDD_H18") (pintype "passive"))
      (node (ref "U1") (pin "H2") (pinfunction "VDD_H2") (pintype "passive"))
      (node (ref "U1") (pin "H20") (pinfunction "VDD_H20") (pintype "passive"))
      (node (ref "U1") (pin "H4") (pinfunction "VDD_H4") (pintype "passive"))
      (node (ref "U1") (pin "H6") (pinfunction "VDD_H6") (pintype "passive"))
      (node (ref "U1") (pin "H8") (pinfunction "VDD_H8") (pintype "passive"))
      (node (ref "U1") (pin "J1") (pinfunction "VDD_J1") (pintype "passive"))
      (node (ref "U1") (pin "J11") (pinfunction "VDD_J11") (pintype "passive"))
      (node (ref "U1") (pin "J13") (pinfunction "VDD_J13") (pintype "passive"))
      (node (ref "U1") (pin "J15") (pinfunction "VDD_J15") (pintype "passive"))
      (node (ref "U1") (pin "J17") (pinfunction "VDD_J17") (pintype "passive"))
      (node (ref "U1") (pin "J19") (pinfunction "VDD_J19") (pintype "passive"))
      (node (ref "U1") (pin "J21") (pinfunction "VDD_J21") (pintype "passive"))
      (node (ref "U1") (pin "J3") (pinfunction "VDD_J3") (pintype "passive"))
      (node (ref "U1") (pin "J5") (pinfunction "VDD_J5") (pintype "passive"))
      (node (ref "U1") (pin "J7") (pinfunction "VDD_J7") (pintype "passive"))
      (node (ref "U1") (pin "J9") (pinfunction "VDD_J9") (pintype "passive"))
      (node (ref "U1") (pin "K10") (pinfunction "VDD_K10") (pintype "passive"))
      (node (ref "U1") (pin "K12") (pinfunction "VDD_K12") (pintype "passive"))
      (node (ref "U1") (pin "K14") (pinfunction "VDD_K14") (pintype "passive"))
      (node (ref "U1") (pin "K16") (pinfunction "VDD_K16") (pintype "passive"))
      (node (ref "U1") (pin "K18") (pinfunction "VDD_K18") (pintype "passive"))
      (node (ref "U1") (pin "K2") (pinfunction "VDD_K2") (pintype "passive"))
      (node (ref "U1") (pin "K20") (pinfunction "VDD_K20") (pintype "passive"))
      (node (ref "U1") (pin "K4") (pinfunction "VDD_K4") (pintype "passive"))
      (node (ref "U1") (pin "K6") (pinfunction "VDD_K6") (pintype "passive"))
      (node (ref "U1") (pin "K8") (pinfunction "VDD_K8") (pintype "passive"))
      (node (ref "U1") (pin "L1") (pinfunction "VDD_L1") (pintype "passive"))
      (node (ref "U1") (pin "L11") (pinfunction "VDD_L11") (pintype "passive"))
      (node (ref "U1") (pin "L13") (pinfunction "VDD_L13") (pintype "passive"))
      (node (ref "U1") (pin "L15") (pinfunction "VDD_L15") (pintype "passive"))
      (node (ref "U1") (pin "L17") (pinfunction "VDD_L17") (pintype "passive"))
      (node (ref "U1") (pin "L19") (pinfunction "VDD_L19") (pintype "passive"))
      (node (ref "U1") (pin "L21") (pinfunction "VDD_L21") (pintype "passive"))
      (node (ref "U1") (pin "L3") (pinfunction "VDD_L3") (pintype "passive"))
      (node (ref "U1") (pin "L5") (pinfunction "VDD_L5") (pintype "passive"))
      (node (ref "U1") (pin "L7") (pinfunction "VDD_L7") (pintype "passive"))
      (node (ref "U1") (pin "L9") (pinfunction "VDD_L9") (pintype "passive"))
      (node (ref "U1") (pin "M10") (pinfunction "VDD_M10") (pintype "passive"))
      (node (ref "U1") (pin "M12") (pinfunction "VDD_M12") (pintype "passive"))
      (node (ref "U1") (pin "M14") (pinfunction "VDD_M14") (pintype "passive"))
      (node (ref "U1") (pin "M16") (pinfunction "VDD_M16") (pintype "passive"))
      (node (ref "U1") (pin "M18") (pinfunction "VDD_M18") (pintype "passive"))
      (node (ref "U1") (pin "M2") (pinfunction "VDD_M2") (pintype "passive"))
      (node (ref "U1") (pin "M4") (pinfunction "VDD_M4") (pintype "passive"))
      (node (ref "U1") (pin "M6") (pinfunction "VDD_M6") (pintype "passive"))
      (node (ref "U1") (pin "M8") (pinfunction "VDD_M8") (pintype "passive"))
      (node (ref "U1") (pin "N1") (pinfunction "VDD_N1") (pintype "passive"))
      (node (ref "U1") (pin "N11") (pinfunction "VDD_N11") (pintype "passive"))
      (node (ref "U1") (pin "N13") (pinfunction "VDD_N13") (pintype "passive"))
      (node (ref "U1") (pin "N15") (pinfunction "VDD_N15") (pintype "passive"))
      (node (ref "U1") (pin "N17") (pinfunction "VDD_N17") (pintype "passive"))
      (node (ref "U1") (pin "N19") (pinfunction "VDD_N19") (pintype "passive"))
      (node (ref "U1") (pin "N21") (pinfunction "VDD_N21") (pintype "passive"))
      (node (ref "U1") (pin "N3") (pinfunction "VDD_N3") (pintype "passive"))
      (node (ref "U1") (pin "N5") (pinfunction "VDD_N5") (pintype "passive"))
      (node (ref "U1") (pin "N7") (pinfunction "VDD_N7") (pintype "passive"))
      (node (ref "U1") (pin "N9") (pinfunction "VDD_N9") (pintype "passive"))
      (node (ref "U1") (pin "P10") (pinfunction "VDD_P10") (pintype "passive"))
      (node (ref "U1") (pin "P12") (pinfunction "VDD_P12") (pintype "passive"))
      (node (ref "U1") (pin "P14") (pinfunction "VDD_P14") (pintype "passive"))
      (node (ref "U1") (pin "P16") (pinfunction "VDD_P16") (pintype "passive"))
      (node (ref "U1") (pin "P18") (pinfunction "VDD_P18") (pintype "passive"))
      (node (ref "U1") (pin "P2") (pinfunction "VDD_P2") (pintype "passive"))
      (node (ref "U1") (pin "P20") (pinfunction "VDD_P20") (pintype "passive"))
      (node (ref "U1") (pin "P4") (pinfunction "VDD_P4") (pintype "passive"))
      (node (ref "U1") (pin "P6") (pinfunction "VDD_P6") (pintype "passive"))
      (node (ref "U1") (pin "P8") (pinfunction "VDD_P8") (pintype "passive"))
      (node (ref "U1") (pin "R1") (pinfunction "VDD_R1") (pintype "passive"))
      (node (ref "U1") (pin "R11") (pinfunction "VDD_R11") (pintype "passive"))
      (node (ref "U1") (pin "R13") (pinfunction "VDD_R13") (pintype "passive"))
      (node (ref "U1") (pin "R15") (pinfunction "VDD_R15") (pintype "passive"))
      (node (ref "U1") (pin "R17") (pinfunction "VDD_R17") (pintype "passive"))
      (node (ref "U1") (pin "R19") (pinfunction "VDD_R19") (pintype "passive"))
      (node (ref "U1") (pin "R21") (pinfunction "VDD_R21") (pintype "passive"))
      (node (ref "U1") (pin "R3") (pinfunction "VDD_R3") (pintype "passive"))
      (node (ref "U1") (pin "R5") (pinfunction "VDD_R5") (pintype "passive"))
      (node (ref "U1") (pin "R7") (pinfunction "VDD_R7") (pintype "passive"))
      (node (ref "U1") (pin "R9") (pinfunction "VDD_R9") (pintype "passive"))
      (node (ref "U1") (pin "T10") (pinfunction "VDD_T10") (pintype "passive"))
      (node (ref "U1") (pin "T12") (pinfunction "VDD_T12") (pintype "passive"))
      (node (ref "U1") (pin "T14") (pinfunction "VDD_T14") (pintype "passive"))
      (node (ref "U1") (pin "T16") (pinfunction "VDD_T16") (pintype "passive"))
      (node (ref "U1") (pin "T18") (pinfunction "VDD_T18") (pintype "passive"))
      (node (ref "U1") (pin "T2") (pinfunction "VDD_T2") (pintype "passive"))
      (node (ref "U1") (pin "T20") (pinfunction "VDD_T20") (pintype "passive"))
      (node (ref "U1") (pin "T4") (pinfunction "VDD_T4") (pintype "passive"))
      (node (ref "U1") (pin "T6") (pinfunction "VDD_T6") (pintype "passive"))
      (node (ref "U1") (pin "T8") (pinfunction "VDD_T8") (pintype "passive"))
      (node (ref "U1") (pin "U1") (pinfunction "VDD_U1") (pintype "passive"))
      (node (ref "U1") (pin "U11") (pinfunction "VDD_U11") (pintype "passive"))
      (node (ref "U1") (pin "U13") (pinfunction "VDD_U13") (pintype "passive"))
      (node (ref "U1") (pin "U15") (pinfunction "VDD_U15") (pintype "passive"))
      (node (ref "U1") (pin "U17") (pinfunction "VDD_U17") (pintype "passive"))
      (node (ref "U1") (pin "U19") (pinfunction "VDD_U19") (pintype "passive"))
      (node (ref "U1") (pin "U21") (pinfunction "VDD_U21") (pintype "passive"))
      (node (ref "U1") (pin "U3") (pinfunction "VDD_U3") (pintype "passive"))
      (node (ref "U1") (pin "U5") (pinfunction "VDD_U5") (pintype "passive"))
      (node (ref "U1") (pin "U7") (pinfunction "VDD_U7") (pintype "passive"))
      (node (ref "U1") (pin "U9") (pinfunction "VDD_U9") (pintype "passive"))
      (node (ref "U1") (pin "V10") (pinfunction "VDD_V10") (pintype "passive"))
      (node (ref "U1") (pin "V12") (pinfunction "VDD_V12") (pintype "passive"))
      (node (ref "U1") (pin "V14") (pinfunction "VDD_V14") (pintype "passive"))
      (node (ref "U1") (pin "V16") (pinfunction "VDD_V16") (pintype "passive"))
      (node (ref "U1") (pin "V18") (pinfunction "VDD_V18") (pintype "passive"))
      (node (ref "U1") (pin "V2") (pinfunction "VDD_V2") (pintype "passive"))
      (node (ref "U1") (pin "V20") (pinfunction "VDD_V20") (pintype "passive"))
      (node (ref "U1") (pin "V4") (pinfunction "VDD_V4") (pintype "passive"))
      (node (ref "U1") (pin "V6") (pinfunction "VDD_V6") (pintype "passive"))
      (node (ref "U1") (pin "V8") (pinfunction "VDD_V8") (pintype "passive"))
      (node (ref "U1") (pin "W1") (pinfunction "VDD_W1") (pintype "passive"))
      (node (ref "U1") (pin "W11") (pinfunction "VDD_W11") (pintype "passive"))
      (node (ref "U1") (pin "W13") (pinfunction "VDD_W13") (pintype "passive"))
      (node (ref "U1") (pin "W15") (pinfunction "VDD_W15") (pintype "passive"))
      (node (ref "U1") (pin "W17") (pinfunction "VDD_W17") (pintype "passive"))
      (node (ref "U1") (pin "W19") (pinfunction "VDD_W19") (pintype "passive"))
      (node (ref "U1") (pin "W21") (pinfunction "VDD_W21") (pintype "passive"))
      (node (ref "U1") (pin "W3") (pinfunction "VDD_W3") (pintype "passive"))
      (node (ref "U1") (pin "W5") (pinfunction "VDD_W5") (pintype "passive"))
      (node (ref "U1") (pin "W7") (pinfunction "VDD_W7") (pintype "passive"))
      (node (ref "U1") (pin "W9") (pinfunction "VDD_W9") (pintype "passive"))
      (node (ref "U1") (pin "Y10") (pinfunction "VDD_Y10") (pintype "passive"))
      (node (ref "U1") (pin "Y12") (pinfunction "VDD_Y12") (pintype "passive"))
      (node (ref "U1") (pin "Y14") (pinfunction "VDD_Y14") (pintype "passive"))
      (node (ref "U1") (pin "Y16") (pinfunction "VDD_Y16") (pintype "passive"))
      (node (ref "U1") (pin "Y18") (pinfunction "VDD_Y18") (pintype "passive"))
      (node (ref "U1") (pin "Y2") (pinfunction "VDD_Y2") (pintype "passive"))
      (node (ref "U1") (pin "Y20") (pinfunction "VDD_Y20") (pintype "passive"))
      (node (ref "U1") (pin "Y4") (pinfunction "VDD_Y4") (pintype "passive"))
      (node (ref "U1") (pin "Y6") (pinfunction "VDD_Y6") (pintype "passive"))
      (node (ref "U1") (pin "Y8") (pinfunction "VDD_Y8") (pintype "passive"))
      (node (ref "U2") (pin "A11") (pinfunction "VDD_A11") (pintype "passive"))
      (node (ref "U2") (pin "A13") (pinfunction "VDD_A13") (pintype "passive"))
      (node (ref "U2") (pin "A15") (pinfunction "VDD_A15") (pintype "passive"))
      (node (ref "U2") (pin "A17") (pinfunction "VDD_A17") (pintype "passive"))
      (node (ref "U2") (pin "A19") (pinfunction "VDD_A19") (pintype "passive"))
      (node (ref "U2") (pin "A3") (pinfunction "VDD_A3") (pintype "passive"))
      (node (ref "U2") (pin "A5") (pinfunction "VDD_A5") (pintype "passive"))
      (node (ref "U2") (pin "A7") (pinfunction "VDD_A7") (pintype "passive"))
      (node (ref "U2") (pin "A9") (pinfunction "VDD_A9") (pintype "passive"))
      (node (ref "U2") (pin "AA1") (pinfunction "VDD_AA1") (pintype "passive"))
      (node (ref "U2") (pin "AA11") (pinfunction "VDD_AA11") (pintype "passive"))
      (node (ref "U2") (pin "AA13") (pinfunction "VDD_AA13") (pintype "passive"))
      (node (ref "U2") (pin "AA15") (pinfunction "VDD_AA15") (pintype "passive"))
      (node (ref "U2") (pin "AA17") (pinfunction "VDD_AA17") (pintype "passive"))
      (node (ref "U2") (pin "AA3") (pinfunction "VDD_AA3") (pintype "passive"))
      (node (ref "U2") (pin "AA5") (pinfunction "VDD_AA5") (pintype "passive"))
      (node (ref "U2") (pin "AA7") (pinfunction "VDD_AA7") (pintype "passive"))
      (node (ref "U2") (pin "AA9") (pinfunction "VDD_AA9") (pintype "passive"))
      (node (ref "U2") (pin "AB10") (pinfunction "VDD_AB10") (pintype "passive"))
      (node (ref "U2") (pin "AB12") (pinfunction "VDD_AB12") (pintype "passive"))
      (node (ref "U2") (pin "AB14") (pinfunction "VDD_AB14") (pintype "passive"))
      (node (ref "U2") (pin "AB16") (pinfunction "VDD_AB16") (pintype "passive"))
      (node (ref "U2") (pin "AB18") (pinfunction "VDD_AB18") (pintype "passive"))
      (node (ref "U2") (pin "AB2") (pinfunction "VDD_AB2") (pintype "passive"))
      (node (ref "U2") (pin "AB4") (pinfunction "VDD_AB4") (pintype "passive"))
      (node (ref "U2") (pin "AB6") (pinfunction "VDD_AB6") (pintype "passive"))
      (node (ref "U2") (pin "AB8") (pinfunction "VDD_AB8") (pintype "passive"))
      (node (ref "U2") (pin "B10") (pinfunction "VDD_B10") (pintype "passive"))
      (node (ref "U2") (pin "B12") (pinfunction "VDD_B12") (pintype "passive"))
      (node (ref "U2") (pin "B14") (pinfunction "VDD_B14") (pintype "passive"))
      (node (ref "U2") (pin "B16") (pinfunction "VDD_B16") (pintype "passive"))
      (node (ref "U2") (pin "B18") (pinfunction "VDD_B18") (pintype "passive"))
      (node (ref "U2") (pin "B2") (pinfunction "VDD_B2") (pintype "passive"))
      (node (ref "U2") (pin "B20") (pinfunction "VDD_B20") (pintype "passive"))
      (node (ref "U2") (pin "B4") (pinfunction "VDD_B4") (pintype "passive"))
      (node (ref "U2") (pin "B6") (pinfunction "VDD_B6") (pintype "passive"))
      (node (ref "U2") (pin "B8") (pinfunction "VDD_B8") (pintype "passive"))
      (node (ref "U2") (pin "C1") (pinfunction "VDD_C1") (pintype "passive"))
      (node (ref "U2") (pin "C11") (pinfunction "VDD_C11") (pintype "passive"))
      (node (ref "U2") (pin "C13") (pinfunction "VDD_C13") (pintype "passive"))
      (node (ref "U2") (pin "C15") (pinfunction "VDD_C15") (pintype "passive"))
      (node (ref "U2") (pin "C17") (pinfunction "VDD_C17") (pintype "passive"))
      (node (ref "U2") (pin "C19") (pinfunction "VDD_C19") (pintype "passive"))
      (node (ref "U2") (pin "C3") (pinfunction "VDD_C3") (pintype "passive"))
      (node (ref "U2") (pin "C5") (pinfunction "VDD_C5") (pintype "passive"))
      (node (ref "U2") (pin "C7") (pinfunction "VDD_C7") (pintype "passive"))
      (node (ref "U2") (pin "C9") (pinfunction "VDD_C9") (pintype "passive"))
      (node (ref "U2") (pin "D10") (pinfunction "VDD_D10") (pintype "passive"))
      (node (ref "U2") (pin "D12") (pinfunction "VDD_D12") (pintype "passive"))
      (node (ref "U2") (pin "D14") (pinfunction "VDD_D14") (pintype "passive"))
      (node (ref "U2") (pin "D16") (pinfunction "VDD_D16") (pintype "passive"))
      (node (ref "U2") (pin "D18") (pinfunction "VDD_D18") (pintype "passive"))
      (node (ref "U2") (pin "D2") (pinfunction "VDD_D2") (pintype "passive"))
      (node (ref "U2") (pin "D20") (pinfunction "VDD_D20") (pintype "passive"))
      (node (ref "U2") (pin "D4") (pinfunction "VDD_D4") (pintype "passive"))
      (node (ref "U2") (pin "D6") (pinfunction "VDD_D6") (pintype "passive"))
      (node (ref "U2") (pin "D8") (pinfunction "VDD_D8") (pintype "passive"))
      (node (ref "U2") (pin "E1") (pinfunction "VDD_E1") (pintype "passive"))
      (node (ref "U2") (pin "E11") (pinfunction "VDD_E11") (pintype "passive"))
      (node (ref "U2") (pin "E13") (pinfunction "VDD_E13") (pintype "passive"))
      (node (ref "U2") (pin "E15") (pinfunction "VDD_E15") (pintype "passive"))
      (node (ref "U2") (pin "E17") (pinfunction "VDD_E17") (pintype "passive"))
      (node (ref "U2") (pin "E19") (pinfunction "VDD_E19") (pintype "passive"))
      (node (ref "U2") (pin "E21") (pinfunction "VDD_E21") (pintype "passive"))
      (node (ref "U2") (pin "E3") (pinfunction "VDD_E3") (pintype "passive"))
      (node (ref "U2") (pin "E5") (pinfunction "VDD_E5") (pintype "passive"))
      (node (ref "U2") (pin "E7") (pinfunction "VDD_E7") (pintype "passive"))
      (node (ref "U2") (pin "E9") (pinfunction "VDD_E9") (pintype "passive"))
      (node (ref "U2") (pin "F10") (pinfunction "VDD_F10") (pintype "passive"))
      (node (ref "U2") (pin "F12") (pinfunction "VDD_F12") (pintype "passive"))
      (node (ref "U2") (pin "F14") (pinfunction "VDD_F14") (pintype "passive"))
      (node (ref "U2") (pin "F16") (pinfunction "VDD_F16") (pintype "passive"))
      (node (ref "U2") (pin "F18") (pinfunction "VDD_F18") (pintype "passive"))
      (node (ref "U2") (pin "F2") (pinfunction "VDD_F2") (pintype "passive"))
      (node (ref "U2") (pin "F20") (pinfunction "VDD_F20") (pintype "passive"))
      (node (ref "U2") (pin "F4") (pinfunction "VDD_F4") (pintype "passive"))
      (node (ref "U2") (pin "F6") (pinfunction "VDD_F6") (pintype "passive"))
      (node (ref "U2") (pin "F8") (pinfunction "VDD_F8") (pintype "passive"))
      (node (ref "U2") (pin "G1") (pinfunction "VDD_G1") (pintype "passive"))
      (node (ref "U2") (pin "G11") (pinfunction "VDD_G11") (pintype "passive"))
      (node (ref "U2") (pin "G13") (pinfunction "VDD_G13") (pintype "passive"))
      (node (ref "U2") (pin "G15") (pinfunction "VDD_G15") (pintype "passive"))
      (node (ref "U2") (pin "G17") (pinfunction "VDD_G17") (pintype "passive"))
      (node (ref "U2") (pin "G19") (pinfunction "VDD_G19") (pintype "passive"))
      (node (ref "U2") (pin "G21") (pinfunction "VDD_G21") (pintype "passive"))
      (node (ref "U2") (pin "G3") (pinfunction "VDD_G3") (pintype "passive"))
      (node (ref "U2") (pin "G5") (pinfunction "VDD_G5") (pintype "passive"))
      (node (ref "U2") (pin "G7") (pinfunction "VDD_G7") (pintype "passive"))
      (node (ref "U2") (pin "G9") (pinfunction "VDD_G9") (pintype "passive"))
      (node (ref "U2") (pin "H10") (pinfunction "VDD_H10") (pintype "passive"))
      (node (ref "U2") (pin "H12") (pinfunction "VDD_H12") (pintype "passive"))
      (node (ref "U2") (pin "H14") (pinfunction "VDD_H14") (pintype "passive"))
      (node (ref "U2") (pin "H16") (pinfunction "VDD_H16") (pintype "passive"))
      (node (ref "U2") (pin "H18") (pinfunction "VDD_H18") (pintype "passive"))
      (node (ref "U2") (pin "H2") (pinfunction "VDD_H2") (pintype "passive"))
      (node (ref "U2") (pin "H20") (pinfunction "VDD_H20") (pintype "passive"))
      (node (ref "U2") (pin "H4") (pinfunction "VDD_H4") (pintype "passive"))
      (node (ref "U2") (pin "H6") (pinfunction "VDD_H6") (pintype "passive"))
      (node (ref "U2") (pin "H8") (pinfunction "VDD_H8") (pintype "passive"))
      (node (ref "U2") (pin "J1") (pinfunction "VDD_J1") (pintype "passive"))
      (node (ref "U2") (pin "J11") (pinfunction "VDD_J11") (pintype "passive"))
      (node (ref "U2") (pin "J13") (pinfunction "VDD_J13") (pintype "passive"))
      (node (ref "U2") (pin "J15") (pinfunction "VDD_J15") (pintype "passive"))
      (node (ref "U2") (pin "J17") (pinfunction "VDD_J17") (pintype "passive"))
      (node (ref "U2") (pin "J19") (pinfunction "VDD_J19") (pintype "passive"))
      (node (ref "U2") (pin "J21") (pinfunction "VDD_J21") (pintype "passive"))
      (node (ref "U2") (pin "J3") (pinfunction "VDD_J3") (pintype "passive"))
      (node (ref "U2") (pin "J5") (pinfunction "VDD_J5") (pintype "passive"))
      (node (ref "U2") (pin "J7") (pinfunction "VDD_J7") (pintype "passive"))
      (node (ref "U2") (pin "J9") (pinfunction "VDD_J9") (pintype "passive"))
      (node (ref "U2") (pin "K10") (pinfunction "VDD_K10") (pintype "passive"))
      (node (ref "U2") (pin "K12") (pinfunction "VDD_K12") (pintype "passive"))
      (node (ref "U2") (pin "K14") (pinfunction "VDD_K14") (pintype "passive"))
      (node (ref "U2") (pin "K16") (pinfunction "VDD_K16") (pintype "passive"))
      (node (ref "U2") (pin "K18") (pinfunction "VDD_K18") (pintype "passive"))
      (node (ref "U2") (pin "K2") (pinfunction "VDD_K2") (pintype "passive"))
      (node (ref "U2") (pin "K20") (pinfunction "VDD_K20") (pintype "passive"))
      (node (ref "U2") (pin "K4") (pinfunction "VDD_K4") (pintype "passive"))
      (node (ref "U2") (pin "K6") (pinfunction "VDD_K6") (pintype "passive"))
      (node (ref "U2") (pin "K8") (pinfunction "VDD_K8") (pintype "passive"))
      (node (ref "U2") (pin "L1") (pinfunction "VDD_L1") (pintype "passive"))
      (node (ref "U2") (pin "L11") (pinfunction "VDD_L11") (pintype "passive"))
      (node (ref "U2") (pin "L13") (pinfunction "VDD_L13") (pintype "passive"))
      (node (ref "U2") (pin "L15") (pinfunction "VDD_L15") (pintype "passive"))
      (node (ref "U2") (pin "L17") (pinfunction "VDD_L17") (pintype "passive"))
      (node (ref "U2") (pin "L19") (pinfunction "VDD_L19") (pintype "passive"))
      (node (ref "U2") (pin "L21") (pinfunction "VDD_L21") (pintype "passive"))
      (node (ref "U2") (pin "L3") (pinfunction "VDD_L3") (pintype "passive"))
      (node (ref "U2") (pin "L5") (pinfunction "VDD_L5") (pintype "passive"))
      (node (ref "U2") (pin "L7") (pinfunction "VDD_L7") (pintype "passive"))
      (node (ref "U2") (pin "L9") (pinfunction "VDD_L9") (pintype "passive"))
      (node (ref "U2") (pin "M10") (pinfunction "VDD_M10") (pintype "passive"))
      (node (ref "U2") (pin "M12") (pinfunction "VDD_M12") (pintype "passive"))
      (node (ref "U2") (pin "M14") (pinfunction "VDD_M14") (pintype "passive"))
      (node (ref "U2") (pin "M16") (pinfunction "VDD_M16") (pintype "passive"))
      (node (ref "U2") (pin "M18") (pinfunction "VDD_M18") (pintype "passive"))
      (node (ref "U2") (pin "M2") (pinfunction "VDD_M2") (pintype "passive"))
      (node (ref "U2") (pin "M4") (pinfunction "VDD_M4") (pintype "passive"))
      (node (ref "U2") (pin "M6") (pinfunction "VDD_M6") (pintype "passive"))
      (node (ref "U2") (pin "M8") (pinfunction "VDD_M8") (pintype "passive"))
      (node (ref "U2") (pin "N1") (pinfunction "VDD_N1") (pintype "passive"))
      (node (ref "U2") (pin "N11") (pinfunction "VDD_N11") (pintype "passive"))
      (node (ref "U2") (pin "N13") (pinfunction "VDD_N13") (pintype "passive"))
      (node (ref "U2") (pin "N15") (pinfunction "VDD_N15") (pintype "passive"))
      (node (ref "U2") (pin "N17") (pinfunction "VDD_N17") (pintype "passive"))
      (node (ref "U2") (pin "N19") (pinfunction "VDD_N19") (pintype "passive"))
      (node (ref "U2") (pin "N21") (pinfunction "VDD_N21") (pintype "passive"))
      (node (ref "U2") (pin "N3") (pinfunction "VDD_N3") (pintype "passive"))
      (node (ref "U2") (pin "N5") (pinfunction "VDD_N5") (pintype "passive"))
      (node (ref "U2") (pin "N7") (pinfunction "VDD_N7") (pintype "passive"))
      (node (ref "U2") (pin "N9") (pinfunction "VDD_N9") (pintype "passive"))
      (node (ref "U2") (pin "P10") (pinfunction "VDD_P10") (pintype "passive"))
      (node (ref "U2") (pin "P12") (pinfunction "VDD_P12") (pintype "passive"))
      (node (ref "U2") (pin "P14") (pinfunction "VDD_P14") (pintype "passive"))
      (node (ref "U2") (pin "P16") (pinfunction "VDD_P16") (pintype "passive"))
      (node (ref "U2") (pin "P18") (pinfunction "VDD_P18") (pintype "passive"))
      (node (ref "U2") (pin "P2") (pinfunction "VDD_P2") (pintype "passive"))
      (node (ref "U2") (pin "P20") (pinfunction "VDD_P20") (pintype "passive"))
      (node (ref "U2") (pin "P4") (pinfunction "VDD_P4") (pintype "passive"))
      (node (ref "U2") (pin "P6") (pinfunction "VDD_P6") (pintype "passive"))
      (node (ref "U2") (pin "P8") (pinfunction "VDD_P8") (pintype "passive"))
      (node (ref "U2") (pin "R1") (pinfunction "VDD_R1") (pintype "passive"))
      (node (ref "U2") (pin "R11") (pinfunction "VDD_R11") (pintype "passive"))
      (node (ref "U2") (pin "R13") (pinfunction "VDD_R13") (pintype "passive"))
      (node (ref "U2") (pin "R15") (pinfunction "VDD_R15") (pintype "passive"))
      (node (ref "U2") (pin "R17") (pinfunction "VDD_R17") (pintype "passive"))
      (node (ref "U2") (pin "R19") (pinfunction "VDD_R19") (pintype "passive"))
      (node (ref "U2") (pin "R21") (pinfunction "VDD_R21") (pintype "passive"))
      (node (ref "U2") (pin "R3") (pinfunction "VDD_R3") (pintype "passive"))
      (node (ref "U2") (pin "R5") (pinfunction "VDD_R5") (pintype "passive"))
      (node (ref "U2") (pin "R7") (pinfunction "VDD_R7") (pintype "passive"))
      (node (ref "U2") (pin "R9") (pinfunction "VDD_R9") (pintype "passive"))
      (node (ref "U2") (pin "T10") (pinfunction "VDD_T10") (pintype "passive"))
      (node (ref "U2") (pin "T12") (pinfunction "VDD_T12") (pintype "passive"))
      (node (ref "U2") (pin "T14") (pinfunction "VDD_T14") (pintype "passive"))
      (node (ref "U2") (pin "T16") (pinfunction "VDD_T16") (pintype "passive"))
      (node (ref "U2") (pin "T18") (pinfunction "VDD_T18") (pintype "passive"))
      (node (ref "U2") (pin "T2") (pinfunction "VDD_T2") (pintype "passive"))
      (node (ref "U2") (pin "T20") (pinfunction "VDD_T20") (pintype "passive"))
      (node (ref "U2") (pin "T4") (pinfunction "VDD_T4") (pintype "passive"))
      (node (ref "U2") (pin "T6") (pinfunction "VDD_T6") (pintype "passive"))
      (node (ref "U2") (pin "T8") (pinfunction "VDD_T8") (pintype "passive"))
      (node (ref "U2") (pin "U1") (pinfunction "VDD_U1") (pintype "passive"))
      (node (ref "U2") (pin "U11") (pinfunction "VDD_U11") (pintype "passive"))
      (node (ref "U2") (pin "U13") (pinfunction "VDD_U13") (pintype "passive"))
      (node (ref "U2") (pin "U15") (pinfunction "VDD_U15") (pintype "passive"))
      (node (ref "U2") (pin "U17") (pinfunction "VDD_U17") (pintype "passive"))
      (node (ref "U2") (pin "U19") (pinfunction "VDD_U19") (pintype "passive"))
      (node (ref "U2") (pin "U21") (pinfunction "VDD_U21") (pintype "passive"))
      (node (ref "U2") (pin "U3") (pinfunction "VDD_U3") (pintype "passive"))
      (node (ref "U2") (pin "U5") (pinfunction "VDD_U5") (pintype "passive"))
      (node (ref "U2") (pin "U7") (pinfunction "VDD_U7") (pintype "passive"))
      (node (ref "U2") (pin "U9") (pinfunction "VDD_U9") (pintype "passive"))
      (node (ref "U2") (pin "V10") (pinfunction "VDD_V10") (pintype "passive"))
      (node (ref "U2") (pin "V12") (pinfunction "VDD_V12") (pintype "passive"))
      (node (ref "U2") (pin "V14") (pinfunction "VDD_V14") (pintype "passive"))
      (node (ref "U2") (pin "V16") (pinfunction "VDD_V16") (pintype "passive"))
      (node (ref "U2") (pin "V18") (pinfunction "VDD_V18") (pintype "passive"))
      (node (ref "U2") (pin "V2") (pinfunction "VDD_V2") (pintype "passive"))
      (node (ref "U2") (pin "V20") (pinfunction "VDD_V20") (pintype "passive"))
      (node (ref "U2") (pin "V4") (pinfunction "VDD_V4") (pintype "passive"))
      (node (ref "U2") (pin "V6") (pinfunction "VDD_V6") (pintype "passive"))
      (node (ref "U2") (pin "V8") (pinfunction "VDD_V8") (pintype "passive"))
      (node (ref "U2") (pin "W1") (pinfunction "VDD_W1") (pintype "passive"))
      (node (ref "U2") (pin "W11") (pinfunction "VDD_W11") (pintype "passive"))
      (node (ref "U2") (pin "W13") (pinfunction "VDD_W13") (pintype "passive"))
      (node (ref "U2") (pin "W15") (pinfunction "VDD_W15") (pintype "passive"))
      (node (ref "U2") (pin "W17") (pinfunction "VDD_W17") (pintype "passive"))
      (node (ref "U2") (pin "W19") (pinfunction "VDD_W19") (pintype "passive"))
      (node (ref "U2") (pin "W21") (pinfunction "VDD_W21") (pintype "passive"))
      (node (ref "U2") (pin "W3") (pinfunction "VDD_W3") (pintype "passive"))
      (node (ref "U2") (pin "W5") (pinfunction "VDD_W5") (pintype "passive"))
      (node (ref "U2") (pin "W7") (pinfunction "VDD_W7") (pintype "passive"))
      (node (ref "U2") (pin "W9") (pinfunction "VDD_W9") (pintype "passive"))
      (node (ref "U2") (pin "Y10") (pinfunction "VDD_Y10") (pintype "passive"))
      (node (ref "U2") (pin "Y12") (pinfunction "VDD_Y12") (pintype "passive"))
      (node (ref "U2") (pin "Y14") (pinfunction "VDD_Y14") (pintype "passive"))
      (node (ref "U2") (pin "Y16") (pinfunction "VDD_Y16") (pintype "passive"))
      (node (ref "U2") (pin "Y18") (pinfunction "VDD_Y18") (pintype "passive"))
      (node (ref "U2") (pin "Y2") (pinfunction "VDD_Y2") (pintype "passive"))
      (node (ref "U2") (pin "Y20") (pinfunction "VDD_Y20") (pintype "passive"))
      (node (ref "U2") (pin "Y4") (pinfunction "VDD_Y4") (pintype "passive"))
      (node (ref "U2") (pin "Y6") (pinfunction "VDD_Y6") (pintype "passive"))
      (node (ref "U2") (pin "Y8") (pinfunction "VDD_Y8") (pintype "passive"))
      (node (ref "U3") (pin "A11") (pinfunction "VDD_A11") (pintype "passive"))
      (node (ref "U3") (pin "A13") (pinfunction "VDD_A13") (pintype "passive"))
      (node (ref "U3") (pin "A15") (pinfunction "VDD_A15") (pintype "passive"))
      (node (ref "U3") (pin "A17") (pinfunction "VDD_A17") (pintype "passive"))
      (node (ref "U3") (pin "A19") (pinfunction "VDD_A19") (pintype "passive"))
      (node (ref "U3") (pin "A3") (pinfunction "VDD_A3") (pintype "passive"))
      (node (ref "U3") (pin "A5") (pinfunction "VDD_A5") (pintype "passive"))
      (node (ref "U3") (pin "A7") (pinfunction "VDD_A7") (pintype "passive"))
      (node (ref "U3") (pin "A9") (pinfunction "VDD_A9") (pintype "passive"))
      (node (ref "U3") (pin "AA1") (pinfunction "VDD_AA1") (pintype "passive"))
      (node (ref "U3") (pin "AA11") (pinfunction "VDD_AA11") (pintype "passive"))
      (node (ref "U3") (pin "AA13") (pinfunction "VDD_AA13") (pintype "passive"))
      (node (ref "U3") (pin "AA15") (pinfunction "VDD_AA15") (pintype "passive"))
      (node (ref "U3") (pin "AA17") (pinfunction "VDD_AA17") (pintype "passive"))
      (node (ref "U3") (pin "AA3") (pinfunction "VDD_AA3") (pintype "passive"))
      (node (ref "U3") (pin "AA5") (pinfunction "VDD_AA5") (pintype "passive"))
      (node (ref "U3") (pin "AA7") (pinfunction "VDD_AA7") (pintype "passive"))
      (node (ref "U3") (pin "AA9") (pinfunction "VDD_AA9") (pintype "passive"))
      (node (ref "U3") (pin "AB10") (pinfunction "VDD_AB10") (pintype "passive"))
      (node (ref "U3") (pin "AB12") (pinfunction "VDD_AB12") (pintype "passive"))
      (node (ref "U3") (pin "AB14") (pinfunction "VDD_AB14") (pintype "passive"))
      (node (ref "U3") (pin "AB16") (pinfunction "VDD_AB16") (pintype "passive"))
      (node (ref "U3") (pin "AB18") (pinfunction "VDD_AB18") (pintype "passive"))
      (node (ref "U3") (pin "AB2") (pinfunction "VDD_AB2") (pintype "passive"))
      (node (ref "U3") (pin "AB4") (pinfunction "VDD_AB4") (pintype "passive"))
      (node (ref "U3") (pin "AB6") (pinfunction "VDD_AB6") (pintype "passive"))
      (node (ref "U3") (pin "AB8") (pinfunction "VDD_AB8") (pintype "passive"))
      (node (ref "U3") (pin "B10") (pinfunction "VDD_B10") (pintype "passive"))
      (node (ref "U3") (pin "B12") (pinfunction "VDD_B12") (pintype "passive"))
      (node (ref "U3") (pin "B14") (pinfunction "VDD_B14") (pintype "passive"))
      (node (ref "U3") (pin "B16") (pinfunction "VDD_B16") (pintype "passive"))
      (node (ref "U3") (pin "B18") (pinfunction "VDD_B18") (pintype "passive"))
      (node (ref "U3") (pin "B2") (pinfunction "VDD_B2") (pintype "passive"))
      (node (ref "U3") (pin "B20") (pinfunction "VDD_B20") (pintype "passive"))
      (node (ref "U3") (pin "B4") (pinfunction "VDD_B4") (pintype "passive"))
      (node (ref "U3") (pin "B6") (pinfunction "VDD_B6") (pintype "passive"))
      (node (ref "U3") (pin "B8") (pinfunction "VDD_B8") (pintype "passive"))
      (node (ref "U3") (pin "C1") (pinfunction "VDD_C1") (pintype "passive"))
      (node (ref "U3") (pin "C11") (pinfunction "VDD_C11") (pintype "passive"))
      (node (ref "U3") (pin "C13") (pinfunction "VDD_C13") (pintype "passive"))
      (node (ref "U3") (pin "C15") (pinfunction "VDD_C15") (pintype "passive"))
      (node (ref "U3") (pin "C17") (pinfunction "VDD_C17") (pintype "passive"))
      (node (ref "U3") (pin "C19") (pinfunction "VDD_C19") (pintype "passive"))
      (node (ref "U3") (pin "C3") (pinfunction "VDD_C3") (pintype "passive"))
      (node (ref "U3") (pin "C5") (pinfunction "VDD_C5") (pintype "passive"))
      (node (ref "U3") (pin "C7") (pinfunction "VDD_C7") (pintype "passive"))
      (node (ref "U3") (pin "C9") (pinfunction "VDD_C9") (pintype "passive"))
      (node (ref "U3") (pin "D10") (pinfunction "VDD_D10") (pintype "passive"))
      (node (ref "U3") (pin "D12") (pinfunction "VDD_D12") (pintype "passive"))
      (node (ref "U3") (pin "D14") (pinfunction "VDD_D14") (pintype "passive"))
      (node (ref "U3") (pin "D16") (pinfunction "VDD_D16") (pintype "passive"))
      (node (ref "U3") (pin "D18") (pinfunction "VDD_D18") (pintype "passive"))
      (node (ref "U3") (pin "D2") (pinfunction "VDD_D2") (pintype "passive"))
      (node (ref "U3") (pin "D20") (pinfunction "VDD_D20") (pintype "passive"))
      (node (ref "U3") (pin "D4") (pinfunction "VDD_D4") (pintype "passive"))
      (node (ref "U3") (pin "D6") (pinfunction "VDD_D6") (pintype "passive"))
      (node (ref "U3") (pin "D8") (pinfunction "VDD_D8") (pintype "passive"))
      (node (ref "U3") (pin "E1") (pinfunction "VDD_E1") (pintype "passive"))
      (node (ref "U3") (pin "E11") (pinfunction "VDD_E11") (pintype "passive"))
      (node (ref "U3") (pin "E13") (pinfunction "VDD_E13") (pintype "passive"))
      (node (ref "U3") (pin "E15") (pinfunction "VDD_E15") (pintype "passive"))
      (node (ref "U3") (pin "E17") (pinfunction "VDD_E17") (pintype "passive"))
      (node (ref "U3") (pin "E19") (pinfunction "VDD_E19") (pintype "passive"))
      (node (ref "U3") (pin "E21") (pinfunction "VDD_E21") (pintype "passive"))
      (node (ref "U3") (pin "E3") (pinfunction "VDD_E3") (pintype "passive"))
      (node (ref "U3") (pin "E5") (pinfunction "VDD_E5") (pintype "passive"))
      (node (ref "U3") (pin "E7") (pinfunction "VDD_E7") (pintype "passive"))
      (node (ref "U3") (pin "E9") (pinfunction "VDD_E9") (pintype "passive"))
      (node (ref "U3") (pin "F10") (pinfunction "VDD_F10") (pintype "passive"))
      (node (ref "U3") (pin "F12") (pinfunction "VDD_F12") (pintype "passive"))
      (node (ref "U3") (pin "F14") (pinfunction "VDD_F14") (pintype "passive"))
      (node (ref "U3") (pin "F16") (pinfunction "VDD_F16") (pintype "passive"))
      (node (ref "U3") (pin "F18") (pinfunction "VDD_F18") (pintype "passive"))
      (node (ref "U3") (pin "F2") (pinfunction "VDD_F2") (pintype "passive"))
      (node (ref "U3") (pin "F20") (pinfunction "VDD_F20") (pintype "passive"))
      (node (ref "U3") (pin "F4") (pinfunction "VDD_F4") (pintype "passive"))
      (node (ref "U3") (pin "F6") (pinfunction "VDD_F6") (pintype "passive"))
      (node (ref "U3") (pin "F8") (pinfunction "VDD_F8") (pintype "passive"))
      (node (ref "U3") (pin "G1") (pinfunction "VDD_G1") (pintype "passive"))
      (node (ref "U3") (pin "G11") (pinfunction "VDD_G11") (pintype "passive"))
      (node (ref "U3") (pin "G13") (pinfunction "VDD_G13") (pintype "passive"))
      (node (ref "U3") (pin "G15") (pinfunction "VDD_G15") (pintype "passive"))
      (node (ref "U3") (pin "G17") (pinfunction "VDD_G17") (pintype "passive"))
      (node (ref "U3") (pin "G19") (pinfunction "VDD_G19") (pintype "passive"))
      (node (ref "U3") (pin "G21") (pinfunction "VDD_G21") (pintype "passive"))
      (node (ref "U3") (pin "G3") (pinfunction "VDD_G3") (pintype "passive"))
      (node (ref "U3") (pin "G5") (pinfunction "VDD_G5") (pintype "passive"))
      (node (ref "U3") (pin "G7") (pinfunction "VDD_G7") (pintype "passive"))
      (node (ref "U3") (pin "G9") (pinfunction "VDD_G9") (pintype "passive"))
      (node (ref "U3") (pin "H10") (pinfunction "VDD_H10") (pintype "passive"))
      (node (ref "U3") (pin "H12") (pinfunction "VDD_H12") (pintype "passive"))
      (node (ref "U3") (pin "H14") (pinfunction "VDD_H14") (pintype "passive"))
      (node (ref "U3") (pin "H16") (pinfunction "VDD_H16") (pintype "passive"))
      (node (ref "U3") (pin "H18") (pinfunction "VDD_H18") (pintype "passive"))
      (node (ref "U3") (pin "H2") (pinfunction "VDD_H2") (pintype "passive"))
      (node (ref "U3") (pin "H20") (pinfunction "VDD_H20") (pintype "passive"))
      (node (ref "U3") (pin "H4") (pinfunction "VDD_H4") (pintype "passive"))
      (node (ref "U3") (pin "H6") (pinfunction "VDD_H6") (pintype "passive"))
      (node (ref "U3") (pin "H8") (pinfunction "VDD_H8") (pintype "passive"))
      (node (ref "U3") (pin "J1") (pinfunction "VDD_J1") (pintype "passive"))
      (node (ref "U3") (pin "J11") (pinfunction "VDD_J11") (pintype "passive"))
      (node (ref "U3") (pin "J13") (pinfunction "VDD_J13") (pintype "passive"))
      (node (ref "U3") (pin "J15") (pinfunction "VDD_J15") (pintype "passive"))
      (node (ref "U3") (pin "J17") (pinfunction "VDD_J17") (pintype "passive"))
      (node (ref "U3") (pin "J19") (pinfunction "VDD_J19") (pintype "passive"))
      (node (ref "U3") (pin "J21") (pinfunction "VDD_J21") (pintype "passive"))
      (node (ref "U3") (pin "J3") (pinfunction "VDD_J3") (pintype "passive"))
      (node (ref "U3") (pin "J5") (pinfunction "VDD_J5") (pintype "passive"))
      (node (ref "U3") (pin "J7") (pinfunction "VDD_J7") (pintype "passive"))
      (node (ref "U3") (pin "J9") (pinfunction "VDD_J9") (pintype "passive"))
      (node (ref "U3") (pin "K10") (pinfunction "VDD_K10") (pintype "passive"))
      (node (ref "U3") (pin "K12") (pinfunction "VDD_K12") (pintype "passive"))
      (node (ref "U3") (pin "K14") (pinfunction "VDD_K14") (pintype "passive"))
      (node (ref "U3") (pin "K16") (pinfunction "VDD_K16") (pintype "passive"))
      (node (ref "U3") (pin "K18") (pinfunction "VDD_K18") (pintype "passive"))
      (node (ref "U3") (pin "K2") (pinfunction "VDD_K2") (pintype "passive"))
      (node (ref "U3") (pin "K20") (pinfunction "VDD_K20") (pintype "passive"))
      (node (ref "U3") (pin "K4") (pinfunction "VDD_K4") (pintype "passive"))
      (node (ref "U3") (pin "K6") (pinfunction "VDD_K6") (pintype "passive"))
      (node (ref "U3") (pin "K8") (pinfunction "VDD_K8") (pintype "passive"))
      (node (ref "U3") (pin "L1") (pinfunction "VDD_L1") (pintype "passive"))
      (node (ref "U3") (pin "L11") (pinfunction "VDD_L11") (pintype "passive"))
      (node (ref "U3") (pin "L13") (pinfunction "VDD_L13") (pintype "passive"))
      (node (ref "U3") (pin "L15") (pinfunction "VDD_L15") (pintype "passive"))
      (node (ref "U3") (pin "L17") (pinfunction "VDD_L17") (pintype "passive"))
      (node (ref "U3") (pin "L19") (pinfunction "VDD_L19") (pintype "passive"))
      (node (ref "U3") (pin "L21") (pinfunction "VDD_L21") (pintype "passive"))
      (node (ref "U3") (pin "L3") (pinfunction "VDD_L3") (pintype "passive"))
      (node (ref "U3") (pin "L5") (pinfunction "VDD_L5") (pintype "passive"))
      (node (ref "U3") (pin "L7") (pinfunction "VDD_L7") (pintype "passive"))
      (node (ref "U3") (pin "L9") (pinfunction "VDD_L9") (pintype "passive"))
      (node (ref "U3") (pin "M10") (pinfunction "VDD_M10") (pintype "passive"))
      (node (ref "U3") (pin "M12") (pinfunction "VDD_M12") (pintype "passive"))
      (node (ref "U3") (pin "M14") (pinfunction "VDD_M14") (pintype "passive"))
      (node (ref "U3") (pin "M16") (pinfunction "VDD_M16") (pintype "passive"))
      (node (ref "U3") (pin "M18") (pinfunction "VDD_M18") (pintype "passive"))
      (node (ref "U3") (pin "M2") (pinfunction "VDD_M2") (pintype "passive"))
      (node (ref "U3") (pin "M4") (pinfunction "VDD_M4") (pintype "passive"))
      (node (ref "U3") (pin "M6") (pinfunction "VDD_M6") (pintype "passive"))
      (node (ref "U3") (pin "M8") (pinfunction "VDD_M8") (pintype "passive"))
      (node (ref "U3") (pin "N1") (pinfunction "VDD_N1") (pintype "passive"))
      (node (ref "U3") (pin "N11") (pinfunction "VDD_N11") (pintype "passive"))
      (node (ref "U3") (pin "N13") (pinfunction "VDD_N13") (pintype "passive"))
      (node (ref "U3") (pin "N15") (pinfunction "VDD_N15") (pintype "passive"))
      (node (ref "U3") (pin "N17") (pinfunction "VDD_N17") (pintype "passive"))
      (node (ref "U3") (pin "N19") (pinfunction "VDD_N19") (pintype "passive"))
      (node (ref "U3") (pin "N21") (pinfunction "VDD_N21") (pintype "passive"))
      (node (ref "U3") (pin "N3") (pinfunction "VDD_N3") (pintype "passive"))
      (node (ref "U3") (pin "N5") (pinfunction "VDD_N5") (pintype "passive"))
      (node (ref "U3") (pin "N7") (pinfunction "VDD_N7") (pintype "passive"))
      (node (ref "U3") (pin "N9") (pinfunction "VDD_N9") (pintype "passive"))
      (node (ref "U3") (pin "P10") (pinfunction "VDD_P10") (pintype "passive"))
      (node (ref "U3") (pin "P12") (pinfunction "VDD_P12") (pintype "passive"))
      (node (ref "U3") (pin "P14") (pinfunction "VDD_P14") (pintype "passive"))
      (node (ref "U3") (pin "P16") (pinfunction "VDD_P16") (pintype "passive"))
      (node (ref "U3") (pin "P18") (pinfunction "VDD_P18") (pintype "passive"))
      (node (ref "U3") (pin "P2") (pinfunction "VDD_P2") (pintype "passive"))
      (node (ref "U3") (pin "P20") (pinfunction "VDD_P20") (pintype "passive"))
      (node (ref "U3") (pin "P4") (pinfunction "VDD_P4") (pintype "passive"))
      (node (ref "U3") (pin "P6") (pinfunction "VDD_P6") (pintype "passive"))
      (node (ref "U3") (pin "P8") (pinfunction "VDD_P8") (pintype "passive"))
      (node (ref "U3") (pin "R1") (pinfunction "VDD_R1") (pintype "passive"))
      (node (ref "U3") (pin "R11") (pinfunction "VDD_R11") (pintype "passive"))
      (node (ref "U3") (pin "R13") (pinfunction "VDD_R13") (pintype "passive"))
      (node (ref "U3") (pin "R15") (pinfunction "VDD_R15") (pintype "passive"))
      (node (ref "U3") (pin "R17") (pinfunction "VDD_R17") (pintype "passive"))
      (node (ref "U3") (pin "R19") (pinfunction "VDD_R19") (pintype "passive"))
      (node (ref "U3") (pin "R21") (pinfunction "VDD_R21") (pintype "passive"))
      (node (ref "U3") (pin "R3") (pinfunction "VDD_R3") (pintype "passive"))
      (node (ref "U3") (pin "R5") (pinfunction "VDD_R5") (pintype "passive"))
      (node (ref "U3") (pin "R7") (pinfunction "VDD_R7") (pintype "passive"))
      (node (ref "U3") (pin "R9") (pinfunction "VDD_R9") (pintype "passive"))
      (node (ref "U3") (pin "T10") (pinfunction "VDD_T10") (pintype "passive"))
      (node (ref "U3") (pin "T12") (pinfunction "VDD_T12") (pintype "passive"))
      (node (ref "U3") (pin "T14") (pinfunction "VDD_T14") (pintype "passive"))
      (node (ref "U3") (pin "T16") (pinfunction "VDD_T16") (pintype "passive"))
      (node (ref "U3") (pin "T18") (pinfunction "VDD_T18") (pintype "passive"))
      (node (ref "U3") (pin "T2") (pinfunction "VDD_T2") (pintype "passive"))
      (node (ref "U3") (pin "T20") (pinfunction "VDD_T20") (pintype "passive"))
      (node (ref "U3") (pin "T4") (pinfunction "VDD_T4") (pintype "passive"))
      (node (ref "U3") (pin "T6") (pinfunction "VDD_T6") (pintype "passive"))
      (node (ref "U3") (pin "T8") (pinfunction "VDD_T8") (pintype "passive"))
      (node (ref "U3") (pin "U1") (pinfunction "VDD_U1") (pintype "passive"))
      (node (ref "U3") (pin "U11") (pinfunction "VDD_U11") (pintype "passive"))
      (node (ref "U3") (pin "U13") (pinfunction "VDD_U13") (pintype "passive"))
      (node (ref "U3") (pin "U15") (pinfunction "VDD_U15") (pintype "passive"))
      (node (ref "U3") (pin "U17") (pinfunction "VDD_U17") (pintype "passive"))
      (node (ref "U3") (pin "U19") (pinfunction "VDD_U19") (pintype "passive"))
      (node (ref "U3") (pin "U21") (pinfunction "VDD_U21") (pintype "passive"))
      (node (ref "U3") (pin "U3") (pinfunction "VDD_U3") (pintype "passive"))
      (node (ref "U3") (pin "U5") (pinfunction "VDD_U5") (pintype "passive"))
      (node (ref "U3") (pin "U7") (pinfunction "VDD_U7") (pintype "passive"))
      (node (ref "U3") (pin "U9") (pinfunction "VDD_U9") (pintype "passive"))
      (node (ref "U3") (pin "V10") (pinfunction "VDD_V10") (pintype "passive"))
      (node (ref "U3") (pin "V12") (pinfunction "VDD_V12") (pintype "passive"))
      (node (ref "U3") (pin "V14") (pinfunction "VDD_V14") (pintype "passive"))
      (node (ref "U3") (pin "V16") (pinfunction "VDD_V16") (pintype "passive"))
      (node (ref "U3") (pin "V18") (pinfunction "VDD_V18") (pintype "passive"))
      (node (ref "U3") (pin "V2") (pinfunction "VDD_V2") (pintype "passive"))
      (node (ref "U3") (pin "V20") (pinfunction "VDD_V20") (pintype "passive"))
      (node (ref "U3") (pin "V4") (pinfunction "VDD_V4") (pintype "passive"))
      (node (ref "U3") (pin "V6") (pinfunction "VDD_V6") (pintype "passive"))
      (node (ref "U3") (pin "V8") (pinfunction "VDD_V8") (pintype "passive"))
      (node (ref "U3") (pin "W1") (pinfunction "VDD_W1") (pintype "passive"))
      (node (ref "U3") (pin "W11") (pinfunction "VDD_W11") (pintype "passive"))
      (node (ref "U3") (pin "W13") (pinfunction "VDD_W13") (pintype "passive"))
      (node (ref "U3") (pin "W15") (pinfunction "VDD_W15") (pintype "passive"))
      (node (ref "U3") (pin "W17") (pinfunction "VDD_W17") (pintype "passive"))
      (node (ref "U3") (pin "W19") (pinfunction "VDD_W19") (pintype "passive"))
      (node (ref "U3") (pin "W21") (pinfunction "VDD_W21") (pintype "passive"))
      (node (ref "U3") (pin "W3") (pinfunction "VDD_W3") (pintype "passive"))
      (node (ref "U3") (pin "W5") (pinfunction "VDD_W5") (pintype "passive"))
      (node (ref "U3") (pin "W7") (pinfunction "VDD_W7") (pintype "passive"))
      (node (ref "U3") (pin "W9") (pinfunction "VDD_W9") (pintype "passive"))
      (node (ref "U3") (pin "Y10") (pinfunction "VDD_Y10") (pintype "passive"))
      (node (ref "U3") (pin "Y12") (pinfunction "VDD_Y12") (pintype "passive"))
      (node (ref "U3") (pin "Y14") (pinfunction "VDD_Y14") (pintype "passive"))
      (node (ref "U3") (pin "Y16") (pinfunction "VDD_Y16") (pintype "passive"))
      (node (ref "U3") (pin "Y18") (pinfunction "VDD_Y18") (pintype "passive"))
      (node (ref "U3") (pin "Y2") (pinfunction "VDD_Y2") (pintype "passive"))
      (node (ref "U3") (pin "Y20") (pinfunction "VDD_Y20") (pintype "passive"))
      (node (ref "U3") (pin "Y4") (pinfunction "VDD_Y4") (pintype "passive"))
      (node (ref "U3") (pin "Y6") (pinfunction "VDD_Y6") (pintype "passive"))
      (node (ref "U3") (pin "Y8") (pinfunction "VDD_Y8") (pintype "passive"))
      (node (ref "U4") (pin "A11") (pinfunction "VDD_A11") (pintype "passive"))
      (node (ref "U4") (pin "A13") (pinfunction "VDD_A13") (pintype "passive"))
      (node (ref "U4") (pin "A15") (pinfunction "VDD_A15") (pintype "passive"))
      (node (ref "U4") (pin "A17") (pinfunction "VDD_A17") (pintype "passive"))
      (node (ref "U4") (pin "A19") (pinfunction "VDD_A19") (pintype "passive"))
      (node (ref "U4") (pin "A3") (pinfunction "VDD_A3") (pintype "passive"))
      (node (ref "U4") (pin "A5") (pinfunction "VDD_A5") (pintype "passive"))
      (node (ref "U4") (pin "A7") (pinfunction "VDD_A7") (pintype "passive"))
      (node (ref "U4") (pin "A9") (pinfunction "VDD_A9") (pintype "passive"))
      (node (ref "U4") (pin "AA1") (pinfunction "VDD_AA1") (pintype "passive"))
      (node (ref "U4") (pin "AA11") (pinfunction "VDD_AA11") (pintype "passive"))
      (node (ref "U4") (pin "AA13") (pinfunction "VDD_AA13") (pintype "passive"))
      (node (ref "U4") (pin "AA15") (pinfunction "VDD_AA15") (pintype "passive"))
      (node (ref "U4") (pin "AA17") (pinfunction "VDD_AA17") (pintype "passive"))
      (node (ref "U4") (pin "AA3") (pinfunction "VDD_AA3") (pintype "passive"))
      (node (ref "U4") (pin "AA5") (pinfunction "VDD_AA5") (pintype "passive"))
      (node (ref "U4") (pin "AA7") (pinfunction "VDD_AA7") (pintype "passive"))
      (node (ref "U4") (pin "AA9") (pinfunction "VDD_AA9") (pintype "passive"))
      (node (ref "U4") (pin "AB10") (pinfunction "VDD_AB10") (pintype "passive"))
      (node (ref "U4") (pin "AB12") (pinfunction "VDD_AB12") (pintype "passive"))
      (node (ref "U4") (pin "AB14") (pinfunction "VDD_AB14") (pintype "passive"))
      (node (ref "U4") (pin "AB16") (pinfunction "VDD_AB16") (pintype "passive"))
      (node (ref "U4") (pin "AB18") (pinfunction "VDD_AB18") (pintype "passive"))
      (node (ref "U4") (pin "AB2") (pinfunction "VDD_AB2") (pintype "passive"))
      (node (ref "U4") (pin "AB4") (pinfunction "VDD_AB4") (pintype "passive"))
      (node (ref "U4") (pin "AB6") (pinfunction "VDD_AB6") (pintype "passive"))
      (node (ref "U4") (pin "AB8") (pinfunction "VDD_AB8") (pintype "passive"))
      (node (ref "U4") (pin "B10") (pinfunction "VDD_B10") (pintype "passive"))
      (node (ref "U4") (pin "B12") (pinfunction "VDD_B12") (pintype "passive"))
      (node (ref "U4") (pin "B14") (pinfunction "VDD_B14") (pintype "passive"))
      (node (ref "U4") (pin "B16") (pinfunction "VDD_B16") (pintype "passive"))
      (node (ref "U4") (pin "B18") (pinfunction "VDD_B18") (pintype "passive"))
      (node (ref "U4") (pin "B2") (pinfunction "VDD_B2") (pintype "passive"))
      (node (ref "U4") (pin "B20") (pinfunction "VDD_B20") (pintype "passive"))
      (node (ref "U4") (pin "B4") (pinfunction "VDD_B4") (pintype "passive"))
      (node (ref "U4") (pin "B6") (pinfunction "VDD_B6") (pintype "passive"))
      (node (ref "U4") (pin "B8") (pinfunction "VDD_B8") (pintype "passive"))
      (node (ref "U4") (pin "C1") (pinfunction "VDD_C1") (pintype "passive"))
      (node (ref "U4") (pin "C11") (pinfunction "VDD_C11") (pintype "passive"))
      (node (ref "U4") (pin "C13") (pinfunction "VDD_C13") (pintype "passive"))
      (node (ref "U4") (pin "C15") (pinfunction "VDD_C15") (pintype "passive"))
      (node (ref "U4") (pin "C17") (pinfunction "VDD_C17") (pintype "passive"))
      (node (ref "U4") (pin "C19") (pinfunction "VDD_C19") (pintype "passive"))
      (node (ref "U4") (pin "C3") (pinfunction "VDD_C3") (pintype "passive"))
      (node (ref "U4") (pin "C5") (pinfunction "VDD_C5") (pintype "passive"))
      (node (ref "U4") (pin "C7") (pinfunction "VDD_C7") (pintype "passive"))
      (node (ref "U4") (pin "C9") (pinfunction "VDD_C9") (pintype "passive"))
      (node (ref "U4") (pin "D10") (pinfunction "VDD_D10") (pintype "passive"))
      (node (ref "U4") (pin "D12") (pinfunction "VDD_D12") (pintype "passive"))
      (node (ref "U4") (pin "D14") (pinfunction "VDD_D14") (pintype "passive"))
      (node (ref "U4") (pin "D16") (pinfunction "VDD_D16") (pintype "passive"))
      (node (ref "U4") (pin "D18") (pinfunction "VDD_D18") (pintype "passive"))
      (node (ref "U4") (pin "D2") (pinfunction "VDD_D2") (pintype "passive"))
      (node (ref "U4") (pin "D20") (pinfunction "VDD_D20") (pintype "passive"))
      (node (ref "U4") (pin "D4") (pinfunction "VDD_D4") (pintype "passive"))
      (node (ref "U4") (pin "D6") (pinfunction "VDD_D6") (pintype "passive"))
      (node (ref "U4") (pin "D8") (pinfunction "VDD_D8") (pintype "passive"))
      (node (ref "U4") (pin "E1") (pinfunction "VDD_E1") (pintype "passive"))
      (node (ref "U4") (pin "E11") (pinfunction "VDD_E11") (pintype "passive"))
      (node (ref "U4") (pin "E13") (pinfunction "VDD_E13") (pintype "passive"))
      (node (ref "U4") (pin "E15") (pinfunction "VDD_E15") (pintype "passive"))
      (node (ref "U4") (pin "E17") (pinfunction "VDD_E17") (pintype "passive"))
      (node (ref "U4") (pin "E19") (pinfunction "VDD_E19") (pintype "passive"))
      (node (ref "U4") (pin "E21") (pinfunction "VDD_E21") (pintype "passive"))
      (node (ref "U4") (pin "E3") (pinfunction "VDD_E3") (pintype "passive"))
      (node (ref "U4") (pin "E5") (pinfunction "VDD_E5") (pintype "passive"))
      (node (ref "U4") (pin "E7") (pinfunction "VDD_E7") (pintype "passive"))
      (node (ref "U4") (pin "E9") (pinfunction "VDD_E9") (pintype "passive"))
      (node (ref "U4") (pin "F10") (pinfunction "VDD_F10") (pintype "passive"))
      (node (ref "U4") (pin "F12") (pinfunction "VDD_F12") (pintype "passive"))
      (node (ref "U4") (pin "F14") (pinfunction "VDD_F14") (pintype "passive"))
      (node (ref "U4") (pin "F16") (pinfunction "VDD_F16") (pintype "passive"))
      (node (ref "U4") (pin "F18") (pinfunction "VDD_F18") (pintype "passive"))
      (node (ref "U4") (pin "F2") (pinfunction "VDD_F2") (pintype "passive"))
      (node (ref "U4") (pin "F20") (pinfunction "VDD_F20") (pintype "passive"))
      (node (ref "U4") (pin "F4") (pinfunction "VDD_F4") (pintype "passive"))
      (node (ref "U4") (pin "F6") (pinfunction "VDD_F6") (pintype "passive"))
      (node (ref "U4") (pin "F8") (pinfunction "VDD_F8") (pintype "passive"))
      (node (ref "U4") (pin "G1") (pinfunction "VDD_G1") (pintype "passive"))
      (node (ref "U4") (pin "G11") (pinfunction "VDD_G11") (pintype "passive"))
      (node (ref "U4") (pin "G13") (pinfunction "VDD_G13") (pintype "passive"))
      (node (ref "U4") (pin "G15") (pinfunction "VDD_G15") (pintype "passive"))
      (node (ref "U4") (pin "G17") (pinfunction "VDD_G17") (pintype "passive"))
      (node (ref "U4") (pin "G19") (pinfunction "VDD_G19") (pintype "passive"))
      (node (ref "U4") (pin "G21") (pinfunction "VDD_G21") (pintype "passive"))
      (node (ref "U4") (pin "G3") (pinfunction "VDD_G3") (pintype "passive"))
      (node (ref "U4") (pin "G5") (pinfunction "VDD_G5") (pintype "passive"))
      (node (ref "U4") (pin "G7") (pinfunction "VDD_G7") (pintype "passive"))
      (node (ref "U4") (pin "G9") (pinfunction "VDD_G9") (pintype "passive"))
      (node (ref "U4") (pin "H10") (pinfunction "VDD_H10") (pintype "passive"))
      (node (ref "U4") (pin "H12") (pinfunction "VDD_H12") (pintype "passive"))
      (node (ref "U4") (pin "H14") (pinfunction "VDD_H14") (pintype "passive"))
      (node (ref "U4") (pin "H16") (pinfunction "VDD_H16") (pintype "passive"))
      (node (ref "U4") (pin "H18") (pinfunction "VDD_H18") (pintype "passive"))
      (node (ref "U4") (pin "H2") (pinfunction "VDD_H2") (pintype "passive"))
      (node (ref "U4") (pin "H20") (pinfunction "VDD_H20") (pintype "passive"))
      (node (ref "U4") (pin "H4") (pinfunction "VDD_H4") (pintype "passive"))
      (node (ref "U4") (pin "H6") (pinfunction "VDD_H6") (pintype "passive"))
      (node (ref "U4") (pin "H8") (pinfunction "VDD_H8") (pintype "passive"))
      (node (ref "U4") (pin "J1") (pinfunction "VDD_J1") (pintype "passive"))
      (node (ref "U4") (pin "J11") (pinfunction "VDD_J11") (pintype "passive"))
      (node (ref "U4") (pin "J13") (pinfunction "VDD_J13") (pintype "passive"))
      (node (ref "U4") (pin "J15") (pinfunction "VDD_J15") (pintype "passive"))
      (node (ref "U4") (pin "J17") (pinfunction "VDD_J17") (pintype "passive"))
      (node (ref "U4") (pin "J19") (pinfunction "VDD_J19") (pintype "passive"))
      (node (ref "U4") (pin "J21") (pinfunction "VDD_J21") (pintype "passive"))
      (node (ref "U4") (pin "J3") (pinfunction "VDD_J3") (pintype "passive"))
      (node (ref "U4") (pin "J5") (pinfunction "VDD_J5") (pintype "passive"))
      (node (ref "U4") (pin "J7") (pinfunction "VDD_J7") (pintype "passive"))
      (node (ref "U4") (pin "J9") (pinfunction "VDD_J9") (pintype "passive"))
      (node (ref "U4") (pin "K10") (pinfunction "VDD_K10") (pintype "passive"))
      (node (ref "U4") (pin "K12") (pinfunction "VDD_K12") (pintype "passive"))
      (node (ref "U4") (pin "K14") (pinfunction "VDD_K14") (pintype "passive"))
      (node (ref "U4") (pin "K16") (pinfunction "VDD_K16") (pintype "passive"))
      (node (ref "U4") (pin "K18") (pinfunction "VDD_K18") (pintype "passive"))
      (node (ref "U4") (pin "K2") (pinfunction "VDD_K2") (pintype "passive"))
      (node (ref "U4") (pin "K20") (pinfunction "VDD_K20") (pintype "passive"))
      (node (ref "U4") (pin "K4") (pinfunction "VDD_K4") (pintype "passive"))
      (node (ref "U4") (pin "K6") (pinfunction "VDD_K6") (pintype "passive"))
      (node (ref "U4") (pin "K8") (pinfunction "VDD_K8") (pintype "passive"))
      (node (ref "U4") (pin "L1") (pinfunction "VDD_L1") (pintype "passive"))
      (node (ref "U4") (pin "L11") (pinfunction "VDD_L11") (pintype "passive"))
      (node (ref "U4") (pin "L13") (pinfunction "VDD_L13") (pintype "passive"))
      (node (ref "U4") (pin "L15") (pinfunction "VDD_L15") (pintype "passive"))
      (node (ref "U4") (pin "L17") (pinfunction "VDD_L17") (pintype "passive"))
      (node (ref "U4") (pin "L19") (pinfunction "VDD_L19") (pintype "passive"))
      (node (ref "U4") (pin "L21") (pinfunction "VDD_L21") (pintype "passive"))
      (node (ref "U4") (pin "L3") (pinfunction "VDD_L3") (pintype "passive"))
      (node (ref "U4") (pin "L5") (pinfunction "VDD_L5") (pintype "passive"))
      (node (ref "U4") (pin "L7") (pinfunction "VDD_L7") (pintype "passive"))
      (node (ref "U4") (pin "L9") (pinfunction "VDD_L9") (pintype "passive"))
      (node (ref "U4") (pin "M10") (pinfunction "VDD_M10") (pintype "passive"))
      (node (ref "U4") (pin "M12") (pinfunction "VDD_M12") (pintype "passive"))
      (node (ref "U4") (pin "M14") (pinfunction "VDD_M14") (pintype "passive"))
      (node (ref "U4") (pin "M16") (pinfunction "VDD_M16") (pintype "passive"))
      (node (ref "U4") (pin "M18") (pinfunction "VDD_M18") (pintype "passive"))
      (node (ref "U4") (pin "M2") (pinfunction "VDD_M2") (pintype "passive"))
      (node (ref "U4") (pin "M4") (pinfunction "VDD_M4") (pintype "passive"))
      (node (ref "U4") (pin "M6") (pinfunction "VDD_M6") (pintype "passive"))
      (node (ref "U4") (pin "M8") (pinfunction "VDD_M8") (pintype "passive"))
      (node (ref "U4") (pin "N1") (pinfunction "VDD_N1") (pintype "passive"))
      (node (ref "U4") (pin "N11") (pinfunction "VDD_N11") (pintype "passive"))
      (node (ref "U4") (pin "N13") (pinfunction "VDD_N13") (pintype "passive"))
      (node (ref "U4") (pin "N15") (pinfunction "VDD_N15") (pintype "passive"))
      (node (ref "U4") (pin "N17") (pinfunction "VDD_N17") (pintype "passive"))
      (node (ref "U4") (pin "N19") (pinfunction "VDD_N19") (pintype "passive"))
      (node (ref "U4") (pin "N21") (pinfunction "VDD_N21") (pintype "passive"))
      (node (ref "U4") (pin "N3") (pinfunction "VDD_N3") (pintype "passive"))
      (node (ref "U4") (pin "N5") (pinfunction "VDD_N5") (pintype "passive"))
      (node (ref "U4") (pin "N7") (pinfunction "VDD_N7") (pintype "passive"))
      (node (ref "U4") (pin "N9") (pinfunction "VDD_N9") (pintype "passive"))
      (node (ref "U4") (pin "P10") (pinfunction "VDD_P10") (pintype "passive"))
      (node (ref "U4") (pin "P12") (pinfunction "VDD_P12") (pintype "passive"))
      (node (ref "U4") (pin "P14") (pinfunction "VDD_P14") (pintype "passive"))
      (node (ref "U4") (pin "P16") (pinfunction "VDD_P16") (pintype "passive"))
      (node (ref "U4") (pin "P18") (pinfunction "VDD_P18") (pintype "passive"))
      (node (ref "U4") (pin "P2") (pinfunction "VDD_P2") (pintype "passive"))
      (node (ref "U4") (pin "P20") (pinfunction "VDD_P20") (pintype "passive"))
      (node (ref "U4") (pin "P4") (pinfunction "VDD_P4") (pintype "passive"))
      (node (ref "U4") (pin "P6") (pinfunction "VDD_P6") (pintype "passive"))
      (node (ref "U4") (pin "P8") (pinfunction "VDD_P8") (pintype "passive"))
      (node (ref "U4") (pin "R1") (pinfunction "VDD_R1") (pintype "passive"))
      (node (ref "U4") (pin "R11") (pinfunction "VDD_R11") (pintype "passive"))
      (node (ref "U4") (pin "R13") (pinfunction "VDD_R13") (pintype "passive"))
      (node (ref "U4") (pin "R15") (pinfunction "VDD_R15") (pintype "passive"))
      (node (ref "U4") (pin "R17") (pinfunction "VDD_R17") (pintype "passive"))
      (node (ref "U4") (pin "R19") (pinfunction "VDD_R19") (pintype "passive"))
      (node (ref "U4") (pin "R21") (pinfunction "VDD_R21") (pintype "passive"))
      (node (ref "U4") (pin "R3") (pinfunction "VDD_R3") (pintype "passive"))
      (node (ref "U4") (pin "R5") (pinfunction "VDD_R5") (pintype "passive"))
      (node (ref "U4") (pin "R7") (pinfunction "VDD_R7") (pintype "passive"))
      (node (ref "U4") (pin "R9") (pinfunction "VDD_R9") (pintype "passive"))
      (node (ref "U4") (pin "T10") (pinfunction "VDD_T10") (pintype "passive"))
      (node (ref "U4") (pin "T12") (pinfunction "VDD_T12") (pintype "passive"))
      (node (ref "U4") (pin "T14") (pinfunction "VDD_T14") (pintype "passive"))
      (node (ref "U4") (pin "T16") (pinfunction "VDD_T16") (pintype "passive"))
      (node (ref "U4") (pin "T18") (pinfunction "VDD_T18") (pintype "passive"))
      (node (ref "U4") (pin "T2") (pinfunction "VDD_T2") (pintype "passive"))
      (node (ref "U4") (pin "T20") (pinfunction "VDD_T20") (pintype "passive"))
      (node (ref "U4") (pin "T4") (pinfunction "VDD_T4") (pintype "passive"))
      (node (ref "U4") (pin "T6") (pinfunction "VDD_T6") (pintype "passive"))
      (node (ref "U4") (pin "T8") (pinfunction "VDD_T8") (pintype "passive"))
      (node (ref "U4") (pin "U1") (pinfunction "VDD_U1") (pintype "passive"))
      (node (ref "U4") (pin "U11") (pinfunction "VDD_U11") (pintype "passive"))
      (node (ref "U4") (pin "U13") (pinfunction "VDD_U13") (pintype "passive"))
      (node (ref "U4") (pin "U15") (pinfunction "VDD_U15") (pintype "passive"))
      (node (ref "U4") (pin "U17") (pinfunction "VDD_U17") (pintype "passive"))
      (node (ref "U4") (pin "U19") (pinfunction "VDD_U19") (pintype "passive"))
      (node (ref "U4") (pin "U21") (pinfunction "VDD_U21") (pintype "passive"))
      (node (ref "U4") (pin "U3") (pinfunction "VDD_U3") (pintype "passive"))
      (node (ref "U4") (pin "U5") (pinfunction "VDD_U5") (pintype "passive"))
      (node (ref "U4") (pin "U7") (pinfunction "VDD_U7") (pintype "passive"))
      (node (ref "U4") (pin "U9") (pinfunction "VDD_U9") (pintype "passive"))
      (node (ref "U4") (pin "V10") (pinfunction "VDD_V10") (pintype "passive"))
      (node (ref "U4") (pin "V12") (pinfunction "VDD_V12") (pintype "passive"))
      (node (ref "U4") (pin "V14") (pinfunction "VDD_V14") (pintype "passive"))
      (node (ref "U4") (pin "V16") (pinfunction "VDD_V16") (pintype "passive"))
      (node (ref "U4") (pin "V18") (pinfunction "VDD_V18") (pintype "passive"))
      (node (ref "U4") (pin "V2") (pinfunction "VDD_V2") (pintype "passive"))
      (node (ref "U4") (pin "V20") (pinfunction "VDD_V20") (pintype "passive"))
      (node (ref "U4") (pin "V4") (pinfunction "VDD_V4") (pintype "passive"))
      (node (ref "U4") (pin "V6") (pinfunction "VDD_V6") (pintype "passive"))
      (node (ref "U4") (pin "V8") (pinfunction "VDD_V8") (pintype "passive"))
      (node (ref "U4") (pin "W1") (pinfunction "VDD_W1") (pintype "passive"))
      (node (ref "U4") (pin "W11") (pinfunction "VDD_W11") (pintype "passive"))
      (node (ref "U4") (pin "W13") (pinfunction "VDD_W13") (pintype "passive"))
      (node (ref "U4") (pin "W15") (pinfunction "VDD_W15") (pintype "passive"))
      (node (ref "U4") (pin "W17") (pinfunction "VDD_W17") (pintype "passive"))
      (node (ref "U4") (pin "W19") (pinfunction "VDD_W19") (pintype "passive"))
      (node (ref "U4") (pin "W21") (pinfunction "VDD_W21") (pintype "passive"))
      (node (ref "U4") (pin "W3") (pinfunction "VDD_W3") (pintype "passive"))
      (node (ref "U4") (pin "W5") (pinfunction "VDD_W5") (pintype "passive"))
      (node (ref "U4") (pin "W7") (pinfunction "VDD_W7") (pintype "passive"))
      (node (ref "U4") (pin "W9") (pinfunction "VDD_W9") (pintype "passive"))
      (node (ref "U4") (pin "Y10") (pinfunction "VDD_Y10") (pintype "passive"))
      (node (ref "U4") (pin "Y12") (pinfunction "VDD_Y12") (pintype "passive"))
      (node (ref "U4") (pin "Y14") (pinfunction "VDD_Y14") (pintype "passive"))
      (node (ref "U4") (pin "Y16") (pinfunction "VDD_Y16") (pintype "passive"))
      (node (ref "U4") (pin "Y18") (pinfunction "VDD_Y18") (pintype "passive"))
      (node (ref "U4") (pin "Y2") (pinfunction "VDD_Y2") (pintype "passive"))
      (node (ref "U4") (pin "Y20") (pinfunction "VDD_Y20") (pintype "passive"))
      (node (ref "U4") (pin "Y4") (pinfunction "VDD_Y4") (pintype "passive"))
      (node (ref "U4") (pin "Y6") (pinfunction "VDD_Y6") (pintype "passive"))
      (node (ref "U4") (pin "Y8") (pinfunction "VDD_Y8") (pintype "passive"))
    )
    (net (code "2") (name "GND") (class "Default")
      (node (ref "C148") (pin "1") (pinfunction "1_1") (pintype "passive"))
      (node (ref "C149") (pin "1") (pinfunction "1_1") (pintype "passive"))
      (node (ref "C150") (pin "1") (pinfunction "1_1") (pintype "passive"))
      (node (ref "C151") (pin "1") (pinfunction "1_1") (pintype "passive"))
      (node (ref "C152") (pin "1") (pinfunction "1_1") (pintype "passive"))
      (node (ref "C153") (pin "1") (pinfunction "1_1") (pintype "passive"))
      (node (ref "C154") (pin "1") (pinfunction "1_1") (pintype "passive"))
      (node (ref "C155") (pin "1") (pinfunction "1_1") (pintype "passive"))
      (node (ref "C156") (pin "1") (pinfunction "1_1") (pintype "passive"))
      (node (ref "C157") (pin "1") (pinfunction "1_1") (pintype "passive"))
      (node (ref "C158") (pin "1") (pinfunction "1_1") (pintype "passive"))
      (node (ref "C159") (pin "1") (pinfunction "1_1") (pintype "passive"))
      (node (ref "C160") (pin "1") (pinfunction "1_1") (pintype "passive"))
      (node (ref "C161") (pin "1") (pinfunction "1_1") (pintype "passive"))
      (node (ref "C162") (pin "1") (pinfunction "1_1") (pintype "passive"))
      (node (ref "C163") (pin "1") (pinfunction "1_1") (pintype "passive"))
      (node (ref "C164") (pin "1") (pinfunction "1_1") (pintype "passive"))
      (node (ref "C165") (pin "1") (pinfunction "1_1") (pintype "passive"))
      (node (ref "C166") (pin "1") (pinfunction "1_1") (pintype "passive"))
      (node (ref "C167") (pin "1") (pinfunction "1_1") (pintype "passive"))
      (node (ref "C169") (pin "1") (pinfunction "1_1") (pintype "passive"))
      (node (ref "C170") (pin "1") (pinfunction "1_1") (pintype "passive"))
      (node (ref "C171") (pin "1") (pinfunction "1_1") (pintype "passive"))
      (node (ref "C172") (pin "1") (pinfunction "1_1") (pintype "passive"))
      (node (ref "C173") (pin "1") (pinfunction "1_1") (pintype "passive"))
      (node (ref "C174") (pin "1") (pinfunction "1_1") (pintype "passive"))
      (node (ref "C175") (pin "1") (pinfunction "1_1") (pintype "passive"))
      (node (ref "C176") (pin "1") (pinfunction "1_1") (pintype "passive"))
      (node (ref "C177") (pin "1") (pinfunction "1_1") (pintype "passive"))
      (node (ref "C178") (pin "1") (pinfunction "1_1") (pintype "passive"))
      (node (ref "C179") (pin "1") (pinfunction "1_1") (pintype "passive"))
      (node (ref "C180") (pin "1") (pinfunction "1_1") (pintype "passive"))
      (node (ref "C181") (pin "1") (pinfunction "1_1") (pintype "passive"))
      (node (ref "C182") (pin "1") (pinfunction "1_1") (pintype "passive"))
      (node (ref "C183") (pin "1") (pinfunction "1_1") (pintype "passive"))
      (node (ref "C184") (pin "1") (pinfunction "1_1") (pintype "passive"))
      (node (ref "C185") (pin "1") (pinfunction "1_1") (pintype "passive"))
      (node (ref "C186") (pin "1") (pinfunction "1_1") (pintype "passive"))
      (node (ref "C187") (pin "1") (pinfunction "1_1") (pintype "passive"))
      (node (ref "C188") (pin "1") (pinfunction "1_1") (pintype "passive"))
      (node (ref "C189") (pin "1") (pinfunction "1_1") (pintype "passive"))
      (node (ref "C19") (pin "1") (pinfunction "1_1") (pintype "passive"))
      (node (ref "C190") (pin "1") (pinfunction "1_1") (pintype "passive"))
      (node (ref "C191") (pin "1") (pinfunction "1_1") (pintype "passive"))
      (node (ref "C192") (pin "1") (pinfunction "1_1") (pintype "passive"))
      (node (ref "C193") (pin "1") (pinfunction "1_1") (pintype "passive"))
      (node (ref "C194") (pin "1") (pinfunction "1_1") (pintype "passive"))
      (node (ref "C195") (pin "1") (pinfunction "1_1") (pintype "passive"))
      (node (ref "C196") (pin "1") (pinfunction "1_1") (pintype "passive"))
      (node (ref "C197") (pin "1") (pinfunction "1_1") (pintype "passive"))
      (node (ref "C198") (pin "1") (pinfunction "1_1") (pintype "passive"))
      (node (ref "C199") (pin "1") (pinfunction "1_1") (pintype "passive"))
      (node (ref "C200") (pin "1") (pinfunction "1_1") (pintype "passive"))
      (node (ref "C201") (pin "1") (pinfunction "1_1") (pintype "passive"))
      (node (ref "C202") (pin "1") (pinfunction "1_1") (pintype "passive"))
      (node (ref "C203") (pin "1") (pinfunction "1_1") (pintype "passive"))
      (node (ref "C204") (pin "1") (pinfunction "1_1") (pintype "passive"))
      (node (ref "C205") (pin "1") (pinfunction "1_1") (pintype "passive"))
      (node (ref "C206") (pin "1") (pinfunction "1_1") (pintype "passive"))
      (node (ref "C207") (pin "1") (pinfunction "1_1") (pintype "passive"))
      (node (ref "C208") (pin "1") (pinfunction "1_1") (pintype "passive"))
      (node (ref "C209") (pin "1") (pinfunction "1_1") (pintype "passive"))
      (node (ref "C210") (pin "1") (pinfunction "1_1") (pintype "passive"))
      (node (ref "C211") (pin "1") (pinfunction "1_1") (pintype "passive"))
      (node (ref "C212") (pin "1") (pinfunction "1_1") (pintype "passive"))
      (node (ref "C213") (pin "1") (pinfunction "1_1") (pintype "passive"))
      (node (ref "C214") (pin "1") (pinfunction "1_1") (pintype "passive"))
      (node (ref "C215") (pin "1") (pinfunction "1_1") (pintype "passive"))
      (node (ref "C216") (pin "1") (pinfunction "1_1") (pintype "passive"))
      (node (ref "C217") (pin "1") (pinfunction "1_1") (pintype "passive"))
      (node (ref "C218") (pin "1") (pinfunction "1_1") (pintype "passive"))
      (node (ref "C219") (pin "1") (pinfunction "1_1") (pintype "passive"))
      (node (ref "C220") (pin "1") (pinfunction "1_1") (pintype "passive"))
      (node (ref "C221") (pin "1") (pinfunction "1_1") (pintype "passive"))
      (node (ref "C222") (pin "1") (pinfunction "1_1") (pintype "passive"))
      (node (ref "C223") (pin "1") (pinfunction "1_1") (pintype "passive"))
      (node (ref "C224") (pin "1") (pinfunction "1_1") (pintype "passive"))
      (node (ref "C225") (pin "1") (pinfunction "1_1") (pintype "passive"))
      (node (ref "C226") (pin "1") (pinfunction "1_1") (pintype "passive"))
      (node (ref "C36") (pin "1") (pinfunction "1_1") (pintype "passive"))
      (node (ref "U1") (pin "A10") (pinfunction "VSS_A10") (pintype "passive"))
      (node (ref "U1") (pin "A12") (pinfunction "VSS_A12") (pintype "passive"))
      (node (ref "U1") (pin "A14") (pinfunction "VSS_A14") (pintype "passive"))
      (node (ref "U1") (pin "A16") (pinfunction "VSS_A16") (pintype "passive"))
      (node (ref "U1") (pin "A18") (pinfunction "VSS_A18") (pintype "passive"))
      (node (ref "U1") (pin "A2") (pinfunction "VSS_A2") (pintype "passive"))
      (node (ref "U1") (pin "A20") (pinfunction "VSS_A20") (pintype "passive"))
      (node (ref "U1") (pin "A4") (pinfunction "VSS_A4") (pintype "passive"))
      (node (ref "U1") (pin "A6") (pinfunction "VSS_A6") (pintype "passive"))
      (node (ref "U1") (pin "A8") (pinfunction "VSS_A8") (pintype "passive"))
      (node (ref "U1") (pin "AA10") (pinfunction "VSS_AA10") (pintype "passive"))
      (node (ref "U1") (pin "AA12") (pinfunction "VSS_AA12") (pintype "passive"))
      (node (ref "U1") (pin "AA14") (pinfunction "VSS_AA14") (pintype "passive"))
      (node (ref "U1") (pin "AA16") (pinfunction "VSS_AA16") (pintype "passive"))
      (node (ref "U1") (pin "AA18") (pinfunction "VSS_AA18") (pintype "passive"))
      (node (ref "U1") (pin "AA2") (pinfunction "VSS_AA2") (pintype "passive"))
      (node (ref "U1") (pin "AA4") (pinfunction "VSS_AA4") (pintype "passive"))
      (node (ref "U1") (pin "AA6") (pinfunction "VSS_AA6") (pintype "passive"))
      (node (ref "U1") (pin "AA8") (pinfunction "VSS_AA8") (pintype "passive"))
      (node (ref "U1") (pin "AB11") (pinfunction "VSS_AB11") (pintype "passive"))
      (node (ref "U1") (pin "AB13") (pinfunction "VSS_AB13") (pintype "passive"))
      (node (ref "U1") (pin "AB15") (pinfunction "VSS_AB15") (pintype "passive"))
      (node (ref "U1") (pin "AB17") (pinfunction "VSS_AB17") (pintype "passive"))
      (node (ref "U1") (pin "AB3") (pinfunction "VSS_AB3") (pintype "passive"))
      (node (ref "U1") (pin "AB5") (pinfunction "VSS_AB5") (pintype "passive"))
      (node (ref "U1") (pin "AB7") (pinfunction "VSS_AB7") (pintype "passive"))
      (node (ref "U1") (pin "AB9") (pinfunction "VSS_AB9") (pintype "passive"))
      (node (ref "U1") (pin "B1") (pinfunction "VSS_B1") (pintype "passive"))
      (node (ref "U1") (pin "B11") (pinfunction "VSS_B11") (pintype "passive"))
      (node (ref "U1") (pin "B13") (pinfunction "VSS_B13") (pintype "passive"))
      (node (ref "U1") (pin "B15") (pinfunction "VSS_B15") (pintype "passive"))
      (node (ref "U1") (pin "B17") (pinfunction "VSS_B17") (pintype "passive"))
      (node (ref "U1") (pin "B19") (pinfunction "VSS_B19") (pintype "passive"))
      (node (ref "U1") (pin "B21") (pinfunction "VSS_B21") (pintype "passive"))
      (node (ref "U1") (pin "B22") (pinfunction "VSS_B22") (pintype "passive"))
      (node (ref "U1") (pin "B3") (pinfunction "VSS_B3") (pintype "passive"))
      (node (ref "U1") (pin "B5") (pinfunction "VSS_B5") (pintype "passive"))
      (node (ref "U1") (pin "B7") (pinfunction "VSS_B7") (pintype "passive"))
      (node (ref "U1") (pin "B9") (pinfunction "VSS_B9") (pintype "passive"))
      (node (ref "U1") (pin "C10") (pinfunction "VSS_C10") (pintype "passive"))
      (node (ref "U1") (pin "C12") (pinfunction "VSS_C12") (pintype "passive"))
      (node (ref "U1") (pin "C14") (pinfunction "VSS_C14") (pintype "passive"))
      (node (ref "U1") (pin "C16") (pinfunction "VSS_C16") (pintype "passive"))
      (node (ref "U1") (pin "C18") (pinfunction "VSS_C18") (pintype "passive"))
      (node (ref "U1") (pin "C2") (pinfunction "VSS_C2") (pintype "passive"))
      (node (ref "U1") (pin "C20") (pinfunction "VSS_C20") (pintype "passive"))
      (node (ref "U1") (pin "C4") (pinfunction "VSS_C4") (pintype "passive"))
      (node (ref "U1") (pin "C6") (pinfunction "VSS_C6") (pintype "passive"))
      (node (ref "U1") (pin "C8") (pinfunction "VSS_C8") (pintype "passive"))
      (node (ref "U1") (pin "D1") (pinfunction "VSS_D1") (pintype "passive"))
      (node (ref "U1") (pin "D11") (pinfunction "VSS_D11") (pintype "passive"))
      (node (ref "U1") (pin "D13") (pinfunction "VSS_D13") (pintype "passive"))
      (node (ref "U1") (pin "D15") (pinfunction "VSS_D15") (pintype "passive"))
      (node (ref "U1") (pin "D17") (pinfunction "VSS_D17") (pintype "passive"))
      (node (ref "U1") (pin "D19") (pinfunction "VSS_D19") (pintype "passive"))
      (node (ref "U1") (pin "D21") (pinfunction "VSS_D21") (pintype "passive"))
      (node (ref "U1") (pin "D22") (pinfunction "VSS_D22") (pintype "passive"))
      (node (ref "U1") (pin "D3") (pinfunction "VSS_D3") (pintype "passive"))
      (node (ref "U1") (pin "D5") (pinfunction "VSS_D5") (pintype "passive"))
      (node (ref "U1") (pin "D7") (pinfunction "VSS_D7") (pintype "passive"))
      (node (ref "U1") (pin "D9") (pinfunction "VSS_D9") (pintype "passive"))
      (node (ref "U1") (pin "E10") (pinfunction "VSS_E10") (pintype "passive"))
      (node (ref "U1") (pin "E12") (pinfunction "VSS_E12") (pintype "passive"))
      (node (ref "U1") (pin "E14") (pinfunction "VSS_E14") (pintype "passive"))
      (node (ref "U1") (pin "E16") (pinfunction "VSS_E16") (pintype "passive"))
      (node (ref "U1") (pin "E18") (pinfunction "VSS_E18") (pintype "passive"))
      (node (ref "U1") (pin "E2") (pinfunction "VSS_E2") (pintype "passive"))
      (node (ref "U1") (pin "E20") (pinfunction "VSS_E20") (pintype "passive"))
      (node (ref "U1") (pin "E4") (pinfunction "VSS_E4") (pintype "passive"))
      (node (ref "U1") (pin "E6") (pinfunction "VSS_E6") (pintype "passive"))
      (node (ref "U1") (pin "E8") (pinfunction "VSS_E8") (pintype "passive"))
      (node (ref "U1") (pin "F1") (pinfunction "VSS_F1") (pintype "passive"))
      (node (ref "U1") (pin "F11") (pinfunction "VSS_F11") (pintype "passive"))
      (node (ref "U1") (pin "F13") (pinfunction "VSS_F13") (pintype "passive"))
      (node (ref "U1") (pin "F15") (pinfunction "VSS_F15") (pintype "passive"))
      (node (ref "U1") (pin "F17") (pinfunction "VSS_F17") (pintype "passive"))
      (node (ref "U1") (pin "F19") (pinfunction "VSS_F19") (pintype "passive"))
      (node (ref "U1") (pin "F21") (pinfunction "VSS_F21") (pintype "passive"))
      (node (ref "U1") (pin "F22") (pinfunction "VSS_F22") (pintype "passive"))
      (node (ref "U1") (pin "F3") (pinfunction "VSS_F3") (pintype "passive"))
      (node (ref "U1") (pin "F5") (pinfunction "VSS_F5") (pintype "passive"))
      (node (ref "U1") (pin "F7") (pinfunction "VSS_F7") (pintype "passive"))
      (node (ref "U1") (pin "F9") (pinfunction "VSS_F9") (pintype "passive"))
      (node (ref "U1") (pin "G10") (pinfunction "VSS_G10") (pintype "passive"))
      (node (ref "U1") (pin "G12") (pinfunction "VSS_G12") (pintype "passive"))
      (node (ref "U1") (pin "G14") (pinfunction "VSS_G14") (pintype "passive"))
      (node (ref "U1") (pin "G16") (pinfunction "VSS_G16") (pintype "passive"))
      (node (ref "U1") (pin "G18") (pinfunction "VSS_G18") (pintype "passive"))
      (node (ref "U1") (pin "G2") (pinfunction "VSS_G2") (pintype "passive"))
      (node (ref "U1") (pin "G20") (pinfunction "VSS_G20") (pintype "passive"))
      (node (ref "U1") (pin "G4") (pinfunction "VSS_G4") (pintype "passive"))
      (node (ref "U1") (pin "G6") (pinfunction "VSS_G6") (pintype "passive"))
      (node (ref "U1") (pin "G8") (pinfunction "VSS_G8") (pintype "passive"))
      (node (ref "U1") (pin "H1") (pinfunction "VSS_H1") (pintype "passive"))
      (node (ref "U1") (pin "H11") (pinfunction "VSS_H11") (pintype "passive"))
      (node (ref "U1") (pin "H13") (pinfunction "VSS_H13") (pintype "passive"))
      (node (ref "U1") (pin "H15") (pinfunction "VSS_H15") (pintype "passive"))
      (node (ref "U1") (pin "H17") (pinfunction "VSS_H17") (pintype "passive"))
      (node (ref "U1") (pin "H19") (pinfunction "VSS_H19") (pintype "passive"))
      (node (ref "U1") (pin "H21") (pinfunction "VSS_H21") (pintype "passive"))
      (node (ref "U1") (pin "H22") (pinfunction "VSS_H22") (pintype "passive"))
      (node (ref "U1") (pin "H3") (pinfunction "VSS_H3") (pintype "passive"))
      (node (ref "U1") (pin "H5") (pinfunction "VSS_H5") (pintype "passive"))
      (node (ref "U1") (pin "H7") (pinfunction "VSS_H7") (pintype "passive"))
      (node (ref "U1") (pin "H9") (pinfunction "VSS_H9") (pintype "passive"))
      (node (ref "U1") (pin "J10") (pinfunction "VSS_J10") (pintype "passive"))
      (node (ref "U1") (pin "J12") (pinfunction "VSS_J12") (pintype "passive"))
      (node (ref "U1") (pin "J14") (pinfunction "VSS_J14") (pintype "passive"))
      (node (ref "U1") (pin "J16") (pinfunction "VSS_J16") (pintype "passive"))
      (node (ref "U1") (pin "J18") (pinfunction "VSS_J18") (pintype "passive"))
      (node (ref "U1") (pin "J2") (pinfunction "VSS_J2") (pintype "passive"))
      (node (ref "U1") (pin "J20") (pinfunction "VSS_J20") (pintype "passive"))
      (node (ref "U1") (pin "J4") (pinfunction "VSS_J4") (pintype "passive"))
      (node (ref "U1") (pin "J6") (pinfunction "VSS_J6") (pintype "passive"))
      (node (ref "U1") (pin "J8") (pinfunction "VSS_J8") (pintype "passive"))
      (node (ref "U1") (pin "K1") (pinfunction "VSS_K1") (pintype "passive"))
      (node (ref "U1") (pin "K11") (pinfunction "VSS_K11") (pintype "passive"))
      (node (ref "U1") (pin "K13") (pinfunction "VSS_K13") (pintype "passive"))
      (node (ref "U1") (pin "K15") (pinfunction "VSS_K15") (pintype "passive"))
      (node (ref "U1") (pin "K17") (pinfunction "VSS_K17") (pintype "passive"))
      (node (ref "U1") (pin "K19") (pinfunction "VSS_K19") (pintype "passive"))
      (node (ref "U1") (pin "K21") (pinfunction "VSS_K21") (pintype "passive"))
      (node (ref "U1") (pin "K22") (pinfunction "VSS_K22") (pintype "passive"))
      (node (ref "U1") (pin "K3") (pinfunction "VSS_K3") (pintype "passive"))
      (node (ref "U1") (pin "K5") (pinfunction "VSS_K5") (pintype "passive"))
      (node (ref "U1") (pin "K7") (pinfunction "VSS_K7") (pintype "passive"))
      (node (ref "U1") (pin "K9") (pinfunction "VSS_K9") (pintype "passive"))
      (node (ref "U1") (pin "L10") (pinfunction "VSS_L10") (pintype "passive"))
      (node (ref "U1") (pin "L12") (pinfunction "VSS_L12") (pintype "passive"))
      (node (ref "U1") (pin "L14") (pinfunction "VSS_L14") (pintype "passive"))
      (node (ref "U1") (pin "L16") (pinfunction "VSS_L16") (pintype "passive"))
      (node (ref "U1") (pin "L18") (pinfunction "VSS_L18") (pintype "passive"))
      (node (ref "U1") (pin "L2") (pinfunction "VSS_L2") (pintype "passive"))
      (node (ref "U1") (pin "L20") (pinfunction "VSS_L20") (pintype "passive"))
      (node (ref "U1") (pin "L4") (pinfunction "VSS_L4") (pintype "passive"))
      (node (ref "U1") (pin "L6") (pinfunction "VSS_L6") (pintype "passive"))
      (node (ref "U1") (pin "L8") (pinfunction "VSS_L8") (pintype "passive"))
      (node (ref "U1") (pin "M1") (pinfunction "VSS_M1") (pintype "passive"))
      (node (ref "U1") (pin "M11") (pinfunction "VSS_M11") (pintype "passive"))
      (node (ref "U1") (pin "M13") (pinfunction "VSS_M13") (pintype "passive"))
      (node (ref "U1") (pin "M15") (pinfunction "VSS_M15") (pintype "passive"))
      (node (ref "U1") (pin "M17") (pinfunction "VSS_M17") (pintype "passive"))
      (node (ref "U1") (pin "M19") (pinfunction "VSS_M19") (pintype "passive"))
      (node (ref "U1") (pin "M21") (pinfunction "VSS_M21") (pintype "passive"))
      (node (ref "U1") (pin "M3") (pinfunction "VSS_M3") (pintype "passive"))
      (node (ref "U1") (pin "M5") (pinfunction "VSS_M5") (pintype "passive"))
      (node (ref "U1") (pin "M7") (pinfunction "VSS_M7") (pintype "passive"))
      (node (ref "U1") (pin "M9") (pinfunction "VSS_M9") (pintype "passive"))
      (node (ref "U1") (pin "N10") (pinfunction "VSS_N10") (pintype "passive"))
      (node (ref "U1") (pin "N12") (pinfunction "VSS_N12") (pintype "passive"))
      (node (ref "U1") (pin "N14") (pinfunction "VSS_N14") (pintype "passive"))
      (node (ref "U1") (pin "N16") (pinfunction "VSS_N16") (pintype "passive"))
      (node (ref "U1") (pin "N18") (pinfunction "VSS_N18") (pintype "passive"))
      (node (ref "U1") (pin "N2") (pinfunction "VSS_N2") (pintype "passive"))
      (node (ref "U1") (pin "N4") (pinfunction "VSS_N4") (pintype "passive"))
      (node (ref "U1") (pin "N6") (pinfunction "VSS_N6") (pintype "passive"))
      (node (ref "U1") (pin "N8") (pinfunction "VSS_N8") (pintype "passive"))
      (node (ref "U1") (pin "P1") (pinfunction "VSS_P1") (pintype "passive"))
      (node (ref "U1") (pin "P11") (pinfunction "VSS_P11") (pintype "passive"))
      (node (ref "U1") (pin "P13") (pinfunction "VSS_P13") (pintype "passive"))
      (node (ref "U1") (pin "P15") (pinfunction "VSS_P15") (pintype "passive"))
      (node (ref "U1") (pin "P17") (pinfunction "VSS_P17") (pintype "passive"))
      (node (ref "U1") (pin "P19") (pinfunction "VSS_P19") (pintype "passive"))
      (node (ref "U1") (pin "P21") (pinfunction "VSS_P21") (pintype "passive"))
      (node (ref "U1") (pin "P22") (pinfunction "VSS_P22") (pintype "passive"))
      (node (ref "U1") (pin "P3") (pinfunction "VSS_P3") (pintype "passive"))
      (node (ref "U1") (pin "P5") (pinfunction "VSS_P5") (pintype "passive"))
      (node (ref "U1") (pin "P7") (pinfunction "VSS_P7") (pintype "passive"))
      (node (ref "U1") (pin "P9") (pinfunction "VSS_P9") (pintype "passive"))
      (node (ref "U1") (pin "R10") (pinfunction "VSS_R10") (pintype "passive"))
      (node (ref "U1") (pin "R12") (pinfunction "VSS_R12") (pintype "passive"))
      (node (ref "U1") (pin "R14") (pinfunction "VSS_R14") (pintype "passive"))
      (node (ref "U1") (pin "R16") (pinfunction "VSS_R16") (pintype "passive"))
      (node (ref "U1") (pin "R18") (pinfunction "VSS_R18") (pintype "passive"))
      (node (ref "U1") (pin "R2") (pinfunction "VSS_R2") (pintype "passive"))
      (node (ref "U1") (pin "R20") (pinfunction "VSS_R20") (pintype "passive"))
      (node (ref "U1") (pin "R4") (pinfunction "VSS_R4") (pintype "passive"))
      (node (ref "U1") (pin "R6") (pinfunction "VSS_R6") (pintype "passive"))
      (node (ref "U1") (pin "R8") (pinfunction "VSS_R8") (pintype "passive"))
      (node (ref "U1") (pin "T1") (pinfunction "VSS_T1") (pintype "passive"))
      (node (ref "U1") (pin "T11") (pinfunction "VSS_T11") (pintype "passive"))
      (node (ref "U1") (pin "T13") (pinfunction "VSS_T13") (pintype "passive"))
      (node (ref "U1") (pin "T15") (pinfunction "VSS_T15") (pintype "passive"))
      (node (ref "U1") (pin "T17") (pinfunction "VSS_T17") (pintype "passive"))
      (node (ref "U1") (pin "T19") (pinfunction "VSS_T19") (pintype "passive"))
      (node (ref "U1") (pin "T21") (pinfunction "VSS_T21") (pintype "passive"))
      (node (ref "U1") (pin "T22") (pinfunction "VSS_T22") (pintype "passive"))
      (node (ref "U1") (pin "T3") (pinfunction "VSS_T3") (pintype "passive"))
      (node (ref "U1") (pin "T5") (pinfunction "VSS_T5") (pintype "passive"))
      (node (ref "U1") (pin "T7") (pinfunction "VSS_T7") (pintype "passive"))
      (node (ref "U1") (pin "T9") (pinfunction "VSS_T9") (pintype "passive"))
      (node (ref "U1") (pin "U10") (pinfunction "VSS_U10") (pintype "passive"))
      (node (ref "U1") (pin "U12") (pinfunction "VSS_U12") (pintype "passive"))
      (node (ref "U1") (pin "U14") (pinfunction "VSS_U14") (pintype "passive"))
      (node (ref "U1") (pin "U16") (pinfunction "VSS_U16") (pintype "passive"))
      (node (ref "U1") (pin "U18") (pinfunction "VSS_U18") (pintype "passive"))
      (node (ref "U1") (pin "U2") (pinfunction "VSS_U2") (pintype "passive"))
      (node (ref "U1") (pin "U20") (pinfunction "VSS_U20") (pintype "passive"))
      (node (ref "U1") (pin "U4") (pinfunction "VSS_U4") (pintype "passive"))
      (node (ref "U1") (pin "U6") (pinfunction "VSS_U6") (pintype "passive"))
      (node (ref "U1") (pin "U8") (pinfunction "VSS_U8") (pintype "passive"))
      (node (ref "U1") (pin "V1") (pinfunction "VSS_V1") (pintype "passive"))
      (node (ref "U1") (pin "V11") (pinfunction "VSS_V11") (pintype "passive"))
      (node (ref "U1") (pin "V13") (pinfunction "VSS_V13") (pintype "passive"))
      (node (ref "U1") (pin "V15") (pinfunction "VSS_V15") (pintype "passive"))
      (node (ref "U1") (pin "V17") (pinfunction "VSS_V17") (pintype "passive"))
      (node (ref "U1") (pin "V19") (pinfunction "VSS_V19") (pintype "passive"))
      (node (ref "U1") (pin "V21") (pinfunction "VSS_V21") (pintype "passive"))
      (node (ref "U1") (pin "V22") (pinfunction "VSS_V22") (pintype "passive"))
      (node (ref "U1") (pin "V3") (pinfunction "VSS_V3") (pintype "passive"))
      (node (ref "U1") (pin "V5") (pinfunction "VSS_V5") (pintype "passive"))
      (node (ref "U1") (pin "V7") (pinfunction "VSS_V7") (pintype "passive"))
      (node (ref "U1") (pin "V9") (pinfunction "VSS_V9") (pintype "passive"))
      (node (ref "U1") (pin "W10") (pinfunction "VSS_W10") (pintype "passive"))
      (node (ref "U1") (pin "W12") (pinfunction "VSS_W12") (pintype "passive"))
      (node (ref "U1") (pin "W14") (pinfunction "VSS_W14") (pintype "passive"))
      (node (ref "U1") (pin "W16") (pinfunction "VSS_W16") (pintype "passive"))
      (node (ref "U1") (pin "W18") (pinfunction "VSS_W18") (pintype "passive"))
      (node (ref "U1") (pin "W2") (pinfunction "VSS_W2") (pintype "passive"))
      (node (ref "U1") (pin "W20") (pinfunction "VSS_W20") (pintype "passive"))
      (node (ref "U1") (pin "W4") (pinfunction "VSS_W4") (pintype "passive"))
      (node (ref "U1") (pin "W6") (pinfunction "VSS_W6") (pintype "passive"))
      (node (ref "U1") (pin "W8") (pinfunction "VSS_W8") (pintype "passive"))
      (node (ref "U1") (pin "Y1") (pinfunction "VSS_Y1") (pintype "passive"))
      (node (ref "U1") (pin "Y11") (pinfunction "VSS_Y11") (pintype "passive"))
      (node (ref "U1") (pin "Y13") (pinfunction "VSS_Y13") (pintype "passive"))
      (node (ref "U1") (pin "Y15") (pinfunction "VSS_Y15") (pintype "passive"))
      (node (ref "U1") (pin "Y17") (pinfunction "VSS_Y17") (pintype "passive"))
      (node (ref "U1") (pin "Y19") (pinfunction "VSS_Y19") (pintype "passive"))
      (node (ref "U1") (pin "Y21") (pinfunction "VSS_Y21") (pintype "passive"))
      (node (ref "U1") (pin "Y22") (pinfunction "VSS_Y22") (pintype "passive"))
      (node (ref "U1") (pin "Y3") (pinfunction "VSS_Y3") (pintype "passive"))
      (node (ref "U1") (pin "Y5") (pinfunction "VSS_Y5") (pintype "passive"))
      (node (ref "U1") (pin "Y7") (pinfunction "VSS_Y7") (pintype "passive"))
      (node (ref "U1") (pin "Y9") (pinfunction "VSS_Y9") (pintype "passive"))
      (node (ref "U2") (pin "A10") (pinfunction "VSS_A10") (pintype "passive"))
      (node (ref "U2") (pin "A12") (pinfunction "VSS_A12") (pintype "passive"))
      (node (ref "U2") (pin "A14") (pinfunction "VSS_A14") (pintype "passive"))
      (node (ref "U2") (pin "A16") (pinfunction "VSS_A16") (pintype "passive"))
      (node (ref "U2") (pin "A18") (pinfunction "VSS_A18") (pintype "passive"))
      (node (ref "U2") (pin "A2") (pinfunction "VSS_A2") (pintype "passive"))
      (node (ref "U2") (pin "A20") (pinfunction "VSS_A20") (pintype "passive"))
      (node (ref "U2") (pin "A4") (pinfunction "VSS_A4") (pintype "passive"))
      (node (ref "U2") (pin "A6") (pinfunction "VSS_A6") (pintype "passive"))
      (node (ref "U2") (pin "A8") (pinfunction "VSS_A8") (pintype "passive"))
      (node (ref "U2") (pin "AA10") (pinfunction "VSS_AA10") (pintype "passive"))
      (node (ref "U2") (pin "AA12") (pinfunction "VSS_AA12") (pintype "passive"))
      (node (ref "U2") (pin "AA14") (pinfunction "VSS_AA14") (pintype "passive"))
      (node (ref "U2") (pin "AA16") (pinfunction "VSS_AA16") (pintype "passive"))
      (node (ref "U2") (pin "AA18") (pinfunction "VSS_AA18") (pintype "passive"))
      (node (ref "U2") (pin "AA2") (pinfunction "VSS_AA2") (pintype "passive"))
      (node (ref "U2") (pin "AA4") (pinfunction "VSS_AA4") (pintype "passive"))
      (node (ref "U2") (pin "AA6") (pinfunction "VSS_AA6") (pintype "passive"))
      (node (ref "U2") (pin "AA8") (pinfunction "VSS_AA8") (pintype "passive"))
      (node (ref "U2") (pin "AB11") (pinfunction "VSS_AB11") (pintype "passive"))
      (node (ref "U2") (pin "AB13") (pinfunction "VSS_AB13") (pintype "passive"))
      (node (ref "U2") (pin "AB15") (pinfunction "VSS_AB15") (pintype "passive"))
      (node (ref "U2") (pin "AB17") (pinfunction "VSS_AB17") (pintype "passive"))
      (node (ref "U2") (pin "AB3") (pinfunction "VSS_AB3") (pintype "passive"))
      (node (ref "U2") (pin "AB5") (pinfunction "VSS_AB5") (pintype "passive"))
      (node (ref "U2") (pin "AB7") (pinfunction "VSS_AB7") (pintype "passive"))
      (node (ref "U2") (pin "AB9") (pinfunction "VSS_AB9") (pintype "passive"))
      (node (ref "U2") (pin "B1") (pinfunction "VSS_B1") (pintype "passive"))
      (node (ref "U2") (pin "B11") (pinfunction "VSS_B11") (pintype "passive"))
      (node (ref "U2") (pin "B13") (pinfunction "VSS_B13") (pintype "passive"))
      (node (ref "U2") (pin "B15") (pinfunction "VSS_B15") (pintype "passive"))
      (node (ref "U2") (pin "B17") (pinfunction "VSS_B17") (pintype "passive"))
      (node (ref "U2") (pin "B19") (pinfunction "VSS_B19") (pintype "passive"))
      (node (ref "U2") (pin "B21") (pinfunction "VSS_B21") (pintype "passive"))
      (node (ref "U2") (pin "B22") (pinfunction "VSS_B22") (pintype "passive"))
      (node (ref "U2") (pin "B3") (pinfunction "VSS_B3") (pintype "passive"))
      (node (ref "U2") (pin "B5") (pinfunction "VSS_B5") (pintype "passive"))
      (node (ref "U2") (pin "B7") (pinfunction "VSS_B7") (pintype "passive"))
      (node (ref "U2") (pin "B9") (pinfunction "VSS_B9") (pintype "passive"))
      (node (ref "U2") (pin "C10") (pinfunction "VSS_C10") (pintype "passive"))
      (node (ref "U2") (pin "C12") (pinfunction "VSS_C12") (pintype "passive"))
      (node (ref "U2") (pin "C14") (pinfunction "VSS_C14") (pintype "passive"))
      (node (ref "U2") (pin "C16") (pinfunction "VSS_C16") (pintype "passive"))
      (node (ref "U2") (pin "C18") (pinfunction "VSS_C18") (pintype "passive"))
      (node (ref "U2") (pin "C2") (pinfunction "VSS_C2") (pintype "passive"))
      (node (ref "U2") (pin "C20") (pinfunction "VSS_C20") (pintype "passive"))
      (node (ref "U2") (pin "C4") (pinfunction "VSS_C4") (pintype "passive"))
      (node (ref "U2") (pin "C6") (pinfunction "VSS_C6") (pintype "passive"))
      (node (ref "U2") (pin "C8") (pinfunction "VSS_C8") (pintype "passive"))
      (node (ref "U2") (pin "D1") (pinfunction "VSS_D1") (pintype "passive"))
      (node (ref "U2") (pin "D11") (pinfunction "VSS_D11") (pintype "passive"))
      (node (ref "U2") (pin "D13") (pinfunction "VSS_D13") (pintype "passive"))
      (node (ref "U2") (pin "D15") (pinfunction "VSS_D15") (pintype "passive"))
      (node (ref "U2") (pin "D17") (pinfunction "VSS_D17") (pintype "passive"))
      (node (ref "U2") (pin "D19") (pinfunction "VSS_D19") (pintype "passive"))
      (node (ref "U2") (pin "D21") (pinfunction "VSS_D21") (pintype "passive"))
      (node (ref "U2") (pin "D22") (pinfunction "VSS_D22") (pintype "passive"))
      (node (ref "U2") (pin "D3") (pinfunction "VSS_D3") (pintype "passive"))
      (node (ref "U2") (pin "D5") (pinfunction "VSS_D5") (pintype "passive"))
      (node (ref "U2") (pin "D7") (pinfunction "VSS_D7") (pintype "passive"))
      (node (ref "U2") (pin "D9") (pinfunction "VSS_D9") (pintype "passive"))
      (node (ref "U2") (pin "E10") (pinfunction "VSS_E10") (pintype "passive"))
      (node (ref "U2") (pin "E12") (pinfunction "VSS_E12") (pintype "passive"))
      (node (ref "U2") (pin "E14") (pinfunction "VSS_E14") (pintype "passive"))
      (node (ref "U2") (pin "E16") (pinfunction "VSS_E16") (pintype "passive"))
      (node (ref "U2") (pin "E18") (pinfunction "VSS_E18") (pintype "passive"))
      (node (ref "U2") (pin "E2") (pinfunction "VSS_E2") (pintype "passive"))
      (node (ref "U2") (pin "E20") (pinfunction "VSS_E20") (pintype "passive"))
      (node (ref "U2") (pin "E4") (pinfunction "VSS_E4") (pintype "passive"))
      (node (ref "U2") (pin "E6") (pinfunction "VSS_E6") (pintype "passive"))
      (node (ref "U2") (pin "E8") (pinfunction "VSS_E8") (pintype "passive"))
      (node (ref "U2") (pin "F1") (pinfunction "VSS_F1") (pintype "passive"))
      (node (ref "U2") (pin "F11") (pinfunction "VSS_F11") (pintype "passive"))
      (node (ref "U2") (pin "F13") (pinfunction "VSS_F13") (pintype "passive"))
      (node (ref "U2") (pin "F15") (pinfunction "VSS_F15") (pintype "passive"))
      (node (ref "U2") (pin "F17") (pinfunction "VSS_F17") (pintype "passive"))
      (node (ref "U2") (pin "F19") (pinfunction "VSS_F19") (pintype "passive"))
      (node (ref "U2") (pin "F21") (pinfunction "VSS_F21") (pintype "passive"))
      (node (ref "U2") (pin "F22") (pinfunction "VSS_F22") (pintype "passive"))
      (node (ref "U2") (pin "F3") (pinfunction "VSS_F3") (pintype "passive"))
      (node (ref "U2") (pin "F5") (pinfunction "VSS_F5") (pintype "passive"))
      (node (ref "U2") (pin "F7") (pinfunction "VSS_F7") (pintype "passive"))
      (node (ref "U2") (pin "F9") (pinfunction "VSS_F9") (pintype "passive"))
      (node (ref "U2") (pin "G10") (pinfunction "VSS_G10") (pintype "passive"))
      (node (ref "U2") (pin "G12") (pinfunction "VSS_G12") (pintype "passive"))
      (node (ref "U2") (pin "G14") (pinfunction "VSS_G14") (pintype "passive"))
      (node (ref "U2") (pin "G16") (pinfunction "VSS_G16") (pintype "passive"))
      (node (ref "U2") (pin "G18") (pinfunction "VSS_G18") (pintype "passive"))
      (node (ref "U2") (pin "G2") (pinfunction "VSS_G2") (pintype "passive"))
      (node (ref "U2") (pin "G20") (pinfunction "VSS_G20") (pintype "passive"))
      (node (ref "U2") (pin "G4") (pinfunction "VSS_G4") (pintype "passive"))
      (node (ref "U2") (pin "G6") (pinfunction "VSS_G6") (pintype "passive"))
      (node (ref "U2") (pin "G8") (pinfunction "VSS_G8") (pintype "passive"))
      (node (ref "U2") (pin "H1") (pinfunction "VSS_H1") (pintype "passive"))
      (node (ref "U2") (pin "H11") (pinfunction "VSS_H11") (pintype "passive"))
      (node (ref "U2") (pin "H13") (pinfunction "VSS_H13") (pintype "passive"))
      (node (ref "U2") (pin "H15") (pinfunction "VSS_H15") (pintype "passive"))
      (node (ref "U2") (pin "H17") (pinfunction "VSS_H17") (pintype "passive"))
      (node (ref "U2") (pin "H19") (pinfunction "VSS_H19") (pintype "passive"))
      (node (ref "U2") (pin "H21") (pinfunction "VSS_H21") (pintype "passive"))
      (node (ref "U2") (pin "H22") (pinfunction "VSS_H22") (pintype "passive"))
      (node (ref "U2") (pin "H3") (pinfunction "VSS_H3") (pintype "passive"))
      (node (ref "U2") (pin "H5") (pinfunction "VSS_H5") (pintype "passive"))
      (node (ref "U2") (pin "H7") (pinfunction "VSS_H7") (pintype "passive"))
      (node (ref "U2") (pin "H9") (pinfunction "VSS_H9") (pintype "passive"))
      (node (ref "U2") (pin "J10") (pinfunction "VSS_J10") (pintype "passive"))
      (node (ref "U2") (pin "J12") (pinfunction "VSS_J12") (pintype "passive"))
      (node (ref "U2") (pin "J14") (pinfunction "VSS_J14") (pintype "passive"))
      (node (ref "U2") (pin "J16") (pinfunction "VSS_J16") (pintype "passive"))
      (node (ref "U2") (pin "J18") (pinfunction "VSS_J18") (pintype "passive"))
      (node (ref "U2") (pin "J2") (pinfunction "VSS_J2") (pintype "passive"))
      (node (ref "U2") (pin "J20") (pinfunction "VSS_J20") (pintype "passive"))
      (node (ref "U2") (pin "J4") (pinfunction "VSS_J4") (pintype "passive"))
      (node (ref "U2") (pin "J6") (pinfunction "VSS_J6") (pintype "passive"))
      (node (ref "U2") (pin "J8") (pinfunction "VSS_J8") (pintype "passive"))
      (node (ref "U2") (pin "K1") (pinfunction "VSS_K1") (pintype "passive"))
      (node (ref "U2") (pin "K11") (pinfunction "VSS_K11") (pintype "passive"))
      (node (ref "U2") (pin "K13") (pinfunction "VSS_K13") (pintype "passive"))
      (node (ref "U2") (pin "K15") (pinfunction "VSS_K15") (pintype "passive"))
      (node (ref "U2") (pin "K17") (pinfunction "VSS_K17") (pintype "passive"))
      (node (ref "U2") (pin "K19") (pinfunction "VSS_K19") (pintype "passive"))
      (node (ref "U2") (pin "K21") (pinfunction "VSS_K21") (pintype "passive"))
      (node (ref "U2") (pin "K22") (pinfunction "VSS_K22") (pintype "passive"))
      (node (ref "U2") (pin "K3") (pinfunction "VSS_K3") (pintype "passive"))
      (node (ref "U2") (pin "K5") (pinfunction "VSS_K5") (pintype "passive"))
      (node (ref "U2") (pin "K7") (pinfunction "VSS_K7") (pintype "passive"))
      (node (ref "U2") (pin "K9") (pinfunction "VSS_K9") (pintype "passive"))
      (node (ref "U2") (pin "L10") (pinfunction "VSS_L10") (pintype "passive"))
      (node (ref "U2") (pin "L12") (pinfunction "VSS_L12") (pintype "passive"))
      (node (ref "U2") (pin "L14") (pinfunction "VSS_L14") (pintype "passive"))
      (node (ref "U2") (pin "L16") (pinfunction "VSS_L16") (pintype "passive"))
      (node (ref "U2") (pin "L18") (pinfunction "VSS_L18") (pintype "passive"))
      (node (ref "U2") (pin "L2") (pinfunction "VSS_L2") (pintype "passive"))
      (node (ref "U2") (pin "L20") (pinfunction "VSS_L20") (pintype "passive"))
      (node (ref "U2") (pin "L4") (pinfunction "VSS_L4") (pintype "passive"))
      (node (ref "U2") (pin "L6") (pinfunction "VSS_L6") (pintype "passive"))
      (node (ref "U2") (pin "L8") (pinfunction "VSS_L8") (pintype "passive"))
      (node (ref "U2") (pin "M1") (pinfunction "VSS_M1") (pintype "passive"))
      (node (ref "U2") (pin "M11") (pinfunction "VSS_M11") (pintype "passive"))
      (node (ref "U2") (pin "M13") (pinfunction "VSS_M13") (pintype "passive"))
      (node (ref "U2") (pin "M15") (pinfunction "VSS_M15") (pintype "passive"))
      (node (ref "U2") (pin "M17") (pinfunction "VSS_M17") (pintype "passive"))
      (node (ref "U2") (pin "M19") (pinfunction "VSS_M19") (pintype "passive"))
      (node (ref "U2") (pin "M21") (pinfunction "VSS_M21") (pintype "passive"))
      (node (ref "U2") (pin "M3") (pinfunction "VSS_M3") (pintype "passive"))
      (node (ref "U2") (pin "M5") (pinfunction "VSS_M5") (pintype "passive"))
      (node (ref "U2") (pin "M7") (pinfunction "VSS_M7") (pintype "passive"))
      (node (ref "U2") (pin "M9") (pinfunction "VSS_M9") (pintype "passive"))
      (node (ref "U2") (pin "N10") (pinfunction "VSS_N10") (pintype "passive"))
      (node (ref "U2") (pin "N12") (pinfunction "VSS_N12") (pintype "passive"))
      (node (ref "U2") (pin "N14") (pinfunction "VSS_N14") (pintype "passive"))
      (node (ref "U2") (pin "N16") (pinfunction "VSS_N16") (pintype "passive"))
      (node (ref "U2") (pin "N18") (pinfunction "VSS_N18") (pintype "passive"))
      (node (ref "U2") (pin "N2") (pinfunction "VSS_N2") (pintype "passive"))
      (node (ref "U2") (pin "N4") (pinfunction "VSS_N4") (pintype "passive"))
      (node (ref "U2") (pin "N6") (pinfunction "VSS_N6") (pintype "passive"))
      (node (ref "U2") (pin "N8") (pinfunction "VSS_N8") (pintype "passive"))
      (node (ref "U2") (pin "P1") (pinfunction "VSS_P1") (pintype "passive"))
      (node (ref "U2") (pin "P11") (pinfunction "VSS_P11") (pintype "passive"))
      (node (ref "U2") (pin "P13") (pinfunction "VSS_P13") (pintype "passive"))
      (node (ref "U2") (pin "P15") (pinfunction "VSS_P15") (pintype "passive"))
      (node (ref "U2") (pin "P17") (pinfunction "VSS_P17") (pintype "passive"))
      (node (ref "U2") (pin "P19") (pinfunction "VSS_P19") (pintype "passive"))
      (node (ref "U2") (pin "P21") (pinfunction "VSS_P21") (pintype "passive"))
      (node (ref "U2") (pin "P22") (pinfunction "VSS_P22") (pintype "passive"))
      (node (ref "U2") (pin "P3") (pinfunction "VSS_P3") (pintype "passive"))
      (node (ref "U2") (pin "P5") (pinfunction "VSS_P5") (pintype "passive"))
      (node (ref "U2") (pin "P7") (pinfunction "VSS_P7") (pintype "passive"))
      (node (ref "U2") (pin "P9") (pinfunction "VSS_P9") (pintype "passive"))
      (node (ref "U2") (pin "R10") (pinfunction "VSS_R10") (pintype "passive"))
      (node (ref "U2") (pin "R12") (pinfunction "VSS_R12") (pintype "passive"))
      (node (ref "U2") (pin "R14") (pinfunction "VSS_R14") (pintype "passive"))
      (node (ref "U2") (pin "R16") (pinfunction "VSS_R16") (pintype "passive"))
      (node (ref "U2") (pin "R18") (pinfunction "VSS_R18") (pintype "passive"))
      (node (ref "U2") (pin "R2") (pinfunction "VSS_R2") (pintype "passive"))
      (node (ref "U2") (pin "R20") (pinfunction "VSS_R20") (pintype "passive"))
      (node (ref "U2") (pin "R4") (pinfunction "VSS_R4") (pintype "passive"))
      (node (ref "U2") (pin "R6") (pinfunction "VSS_R6") (pintype "passive"))
      (node (ref "U2") (pin "R8") (pinfunction "VSS_R8") (pintype "passive"))
      (node (ref "U2") (pin "T1") (pinfunction "VSS_T1") (pintype "passive"))
      (node (ref "U2") (pin "T11") (pinfunction "VSS_T11") (pintype "passive"))
      (node (ref "U2") (pin "T13") (pinfunction "VSS_T13") (pintype "passive"))
      (node (ref "U2") (pin "T15") (pinfunction "VSS_T15") (pintype "passive"))
      (node (ref "U2") (pin "T17") (pinfunction "VSS_T17") (pintype "passive"))
      (node (ref "U2") (pin "T19") (pinfunction "VSS_T19") (pintype "passive"))
      (node (ref "U2") (pin "T21") (pinfunction "VSS_T21") (pintype "passive"))
      (node (ref "U2") (pin "T22") (pinfunction "VSS_T22") (pintype "passive"))
      (node (ref "U2") (pin "T3") (pinfunction "VSS_T3") (pintype "passive"))
      (node (ref "U2") (pin "T5") (pinfunction "VSS_T5") (pintype "passive"))
      (node (ref "U2") (pin "T7") (pinfunction "VSS_T7") (pintype "passive"))
      (node (ref "U2") (pin "T9") (pinfunction "VSS_T9") (pintype "passive"))
      (node (ref "U2") (pin "U10") (pinfunction "VSS_U10") (pintype "passive"))
      (node (ref "U2") (pin "U12") (pinfunction "VSS_U12") (pintype "passive"))
      (node (ref "U2") (pin "U14") (pinfunction "VSS_U14") (pintype "passive"))
      (node (ref "U2") (pin "U16") (pinfunction "VSS_U16") (pintype "passive"))
      (node (ref "U2") (pin "U18") (pinfunction "VSS_U18") (pintype "passive"))
      (node (ref "U2") (pin "U2") (pinfunction "VSS_U2") (pintype "passive"))
      (node (ref "U2") (pin "U20") (pinfunction "VSS_U20") (pintype "passive"))
      (node (ref "U2") (pin "U4") (pinfunction "VSS_U4") (pintype "passive"))
      (node (ref "U2") (pin "U6") (pinfunction "VSS_U6") (pintype "passive"))
      (node (ref "U2") (pin "U8") (pinfunction "VSS_U8") (pintype "passive"))
      (node (ref "U2") (pin "V1") (pinfunction "VSS_V1") (pintype "passive"))
      (node (ref "U2") (pin "V11") (pinfunction "VSS_V11") (pintype "passive"))
      (node (ref "U2") (pin "V13") (pinfunction "VSS_V13") (pintype "passive"))
      (node (ref "U2") (pin "V15") (pinfunction "VSS_V15") (pintype "passive"))
      (node (ref "U2") (pin "V17") (pinfunction "VSS_V17") (pintype "passive"))
      (node (ref "U2") (pin "V19") (pinfunction "VSS_V19") (pintype "passive"))
      (node (ref "U2") (pin "V21") (pinfunction "VSS_V21") (pintype "passive"))
      (node (ref "U2") (pin "V22") (pinfunction "VSS_V22") (pintype "passive"))
      (node (ref "U2") (pin "V3") (pinfunction "VSS_V3") (pintype "passive"))
      (node (ref "U2") (pin "V5") (pinfunction "VSS_V5") (pintype "passive"))
      (node (ref "U2") (pin "V7") (pinfunction "VSS_V7") (pintype "passive"))
      (node (ref "U2") (pin "V9") (pinfunction "VSS_V9") (pintype "passive"))
      (node (ref "U2") (pin "W10") (pinfunction "VSS_W10") (pintype "passive"))
      (node (ref "U2") (pin "W12") (pinfunction "VSS_W12") (pintype "passive"))
      (node (ref "U2") (pin "W14") (pinfunction "VSS_W14") (pintype "passive"))
      (node (ref "U2") (pin "W16") (pinfunction "VSS_W16") (pintype "passive"))
      (node (ref "U2") (pin "W18") (pinfunction "VSS_W18") (pintype "passive"))
      (node (ref "U2") (pin "W2") (pinfunction "VSS_W2") (pintype "passive"))
      (node (ref "U2") (pin "W20") (pinfunction "VSS_W20") (pintype "passive"))
      (node (ref "U2") (pin "W4") (pinfunction "VSS_W4") (pintype "passive"))
      (node (ref "U2") (pin "W6") (pinfunction "VSS_W6") (pintype "passive"))
      (node (ref "U2") (pin "W8") (pinfunction "VSS_W8") (pintype "passive"))
      (node (ref "U2") (pin "Y1") (pinfunction "VSS_Y1") (pintype "passive"))
      (node (ref "U2") (pin "Y11") (pinfunction "VSS_Y11") (pintype "passive"))
      (node (ref "U2") (pin "Y13") (pinfunction "VSS_Y13") (pintype "passive"))
      (node (ref "U2") (pin "Y15") (pinfunction "VSS_Y15") (pintype "passive"))
      (node (ref "U2") (pin "Y17") (pinfunction "VSS_Y17") (pintype "passive"))
      (node (ref "U2") (pin "Y19") (pinfunction "VSS_Y19") (pintype "passive"))
      (node (ref "U2") (pin "Y21") (pinfunction "VSS_Y21") (pintype "passive"))
      (node (ref "U2") (pin "Y22") (pinfunction "VSS_Y22") (pintype "passive"))
      (node (ref "U2") (pin "Y3") (pinfunction "VSS_Y3") (pintype "passive"))
      (node (ref "U2") (pin "Y5") (pinfunction "VSS_Y5") (pintype "passive"))
      (node (ref "U2") (pin "Y7") (pinfunction "VSS_Y7") (pintype "passive"))
      (node (ref "U2") (pin "Y9") (pinfunction "VSS_Y9") (pintype "passive"))
      (node (ref "U3") (pin "A10") (pinfunction "VSS_A10") (pintype "passive"))
      (node (ref "U3") (pin "A12") (pinfunction "VSS_A12") (pintype "passive"))
      (node (ref "U3") (pin "A14") (pinfunction "VSS_A14") (pintype "passive"))
      (node (ref "U3") (pin "A16") (pinfunction "VSS_A16") (pintype "passive"))
      (node (ref "U3") (pin "A18") (pinfunction "VSS_A18") (pintype "passive"))
      (node (ref "U3") (pin "A2") (pinfunction "VSS_A2") (pintype "passive"))
      (node (ref "U3") (pin "A20") (pinfunction "VSS_A20") (pintype "passive"))
      (node (ref "U3") (pin "A4") (pinfunction "VSS_A4") (pintype "passive"))
      (node (ref "U3") (pin "A6") (pinfunction "VSS_A6") (pintype "passive"))
      (node (ref "U3") (pin "A8") (pinfunction "VSS_A8") (pintype "passive"))
      (node (ref "U3") (pin "AA10") (pinfunction "VSS_AA10") (pintype "passive"))
      (node (ref "U3") (pin "AA12") (pinfunction "VSS_AA12") (pintype "passive"))
      (node (ref "U3") (pin "AA14") (pinfunction "VSS_AA14") (pintype "passive"))
      (node (ref "U3") (pin "AA16") (pinfunction "VSS_AA16") (pintype "passive"))
      (node (ref "U3") (pin "AA18") (pinfunction "VSS_AA18") (pintype "passive"))
      (node (ref "U3") (pin "AA2") (pinfunction "VSS_AA2") (pintype "passive"))
      (node (ref "U3") (pin "AA4") (pinfunction "VSS_AA4") (pintype "passive"))
      (node (ref "U3") (pin "AA6") (pinfunction "VSS_AA6") (pintype "passive"))
      (node (ref "U3") (pin "AA8") (pinfunction "VSS_AA8") (pintype "passive"))
      (node (ref "U3") (pin "AB11") (pinfunction "VSS_AB11") (pintype "passive"))
      (node (ref "U3") (pin "AB13") (pinfunction "VSS_AB13") (pintype "passive"))
      (node (ref "U3") (pin "AB15") (pinfunction "VSS_AB15") (pintype "passive"))
      (node (ref "U3") (pin "AB17") (pinfunction "VSS_AB17") (pintype "passive"))
      (node (ref "U3") (pin "AB3") (pinfunction "VSS_AB3") (pintype "passive"))
      (node (ref "U3") (pin "AB5") (pinfunction "VSS_AB5") (pintype "passive"))
      (node (ref "U3") (pin "AB7") (pinfunction "VSS_AB7") (pintype "passive"))
      (node (ref "U3") (pin "AB9") (pinfunction "VSS_AB9") (pintype "passive"))
      (node (ref "U3") (pin "B1") (pinfunction "VSS_B1") (pintype "passive"))
      (node (ref "U3") (pin "B11") (pinfunction "VSS_B11") (pintype "passive"))
      (node (ref "U3") (pin "B13") (pinfunction "VSS_B13") (pintype "passive"))
      (node (ref "U3") (pin "B15") (pinfunction "VSS_B15") (pintype "passive"))
      (node (ref "U3") (pin "B17") (pinfunction "VSS_B17") (pintype "passive"))
      (node (ref "U3") (pin "B19") (pinfunction "VSS_B19") (pintype "passive"))
      (node (ref "U3") (pin "B21") (pinfunction "VSS_B21") (pintype "passive"))
      (node (ref "U3") (pin "B22") (pinfunction "VSS_B22") (pintype "passive"))
      (node (ref "U3") (pin "B3") (pinfunction "VSS_B3") (pintype "passive"))
      (node (ref "U3") (pin "B5") (pinfunction "VSS_B5") (pintype "passive"))
      (node (ref "U3") (pin "B7") (pinfunction "VSS_B7") (pintype "passive"))
      (node (ref "U3") (pin "B9") (pinfunction "VSS_B9") (pintype "passive"))
      (node (ref "U3") (pin "C10") (pinfunction "VSS_C10") (pintype "passive"))
      (node (ref "U3") (pin "C12") (pinfunction "VSS_C12") (pintype "passive"))
      (node (ref "U3") (pin "C14") (pinfunction "VSS_C14") (pintype "passive"))
      (node (ref "U3") (pin "C16") (pinfunction "VSS_C16") (pintype "passive"))
      (node (ref "U3") (pin "C18") (pinfunction "VSS_C18") (pintype "passive"))
      (node (ref "U3") (pin "C2") (pinfunction "VSS_C2") (pintype "passive"))
      (node (ref "U3") (pin "C20") (pinfunction "VSS_C20") (pintype "passive"))
      (node (ref "U3") (pin "C4") (pinfunction "VSS_C4") (pintype "passive"))
      (node (ref "U3") (pin "C6") (pinfunction "VSS_C6") (pintype "passive"))
      (node (ref "U3") (pin "C8") (pinfunction "VSS_C8") (pintype "passive"))
      (node (ref "U3") (pin "D1") (pinfunction "VSS_D1") (pintype "passive"))
      (node (ref "U3") (pin "D11") (pinfunction "VSS_D11") (pintype "passive"))
      (node (ref "U3") (pin "D13") (pinfunction "VSS_D13") (pintype "passive"))
      (node (ref "U3") (pin "D15") (pinfunction "VSS_D15") (pintype "passive"))
      (node (ref "U3") (pin "D17") (pinfunction "VSS_D17") (pintype "passive"))
      (node (ref "U3") (pin "D19") (pinfunction "VSS_D19") (pintype "passive"))
      (node (ref "U3") (pin "D21") (pinfunction "VSS_D21") (pintype "passive"))
      (node (ref "U3") (pin "D22") (pinfunction "VSS_D22") (pintype "passive"))
      (node (ref "U3") (pin "D3") (pinfunction "VSS_D3") (pintype "passive"))
      (node (ref "U3") (pin "D5") (pinfunction "VSS_D5") (pintype "passive"))
      (node (ref "U3") (pin "D7") (pinfunction "VSS_D7") (pintype "passive"))
      (node (ref "U3") (pin "D9") (pinfunction "VSS_D9") (pintype "passive"))
      (node (ref "U3") (pin "E10") (pinfunction "VSS_E10") (pintype "passive"))
      (node (ref "U3") (pin "E12") (pinfunction "VSS_E12") (pintype "passive"))
      (node (ref "U3") (pin "E14") (pinfunction "VSS_E14") (pintype "passive"))
      (node (ref "U3") (pin "E16") (pinfunction "VSS_E16") (pintype "passive"))
      (node (ref "U3") (pin "E18") (pinfunction "VSS_E18") (pintype "passive"))
      (node (ref "U3") (pin "E2") (pinfunction "VSS_E2") (pintype "passive"))
      (node (ref "U3") (pin "E20") (pinfunction "VSS_E20") (pintype "passive"))
      (node (ref "U3") (pin "E4") (pinfunction "VSS_E4") (pintype "passive"))
      (node (ref "U3") (pin "E6") (pinfunction "VSS_E6") (pintype "passive"))
      (node (ref "U3") (pin "E8") (pinfunction "VSS_E8") (pintype "passive"))
      (node (ref "U3") (pin "F1") (pinfunction "VSS_F1") (pintype "passive"))
      (node (ref "U3") (pin "F11") (pinfunction "VSS_F11") (pintype "passive"))
      (node (ref "U3") (pin "F13") (pinfunction "VSS_F13") (pintype "passive"))
      (node (ref "U3") (pin "F15") (pinfunction "VSS_F15") (pintype "passive"))
      (node (ref "U3") (pin "F17") (pinfunction "VSS_F17") (pintype "passive"))
      (node (ref "U3") (pin "F19") (pinfunction "VSS_F19") (pintype "passive"))
      (node (ref "U3") (pin "F21") (pinfunction "VSS_F21") (pintype "passive"))
      (node (ref "U3") (pin "F22") (pinfunction "VSS_F22") (pintype "passive"))
      (node (ref "U3") (pin "F3") (pinfunction "VSS_F3") (pintype "passive"))
      (node (ref "U3") (pin "F5") (pinfunction "VSS_F5") (pintype "passive"))
      (node (ref "U3") (pin "F7") (pinfunction "VSS_F7") (pintype "passive"))
      (node (ref "U3") (pin "F9") (pinfunction "VSS_F9") (pintype "passive"))
      (node (ref "U3") (pin "G10") (pinfunction "VSS_G10") (pintype "passive"))
      (node (ref "U3") (pin "G12") (pinfunction "VSS_G12") (pintype "passive"))
      (node (ref "U3") (pin "G14") (pinfunction "VSS_G14") (pintype "passive"))
      (node (ref "U3") (pin "G16") (pinfunction "VSS_G16") (pintype "passive"))
      (node (ref "U3") (pin "G18") (pinfunction "VSS_G18") (pintype "passive"))
      (node (ref "U3") (pin "G2") (pinfunction "VSS_G2") (pintype "passive"))
      (node (ref "U3") (pin "G20") (pinfunction "VSS_G20") (pintype "passive"))
      (node (ref "U3") (pin "G4") (pinfunction "VSS_G4") (pintype "passive"))
      (node (ref "U3") (pin "G6") (pinfunction "VSS_G6") (pintype "passive"))
      (node (ref "U3") (pin "G8") (pinfunction "VSS_G8") (pintype "passive"))
      (node (ref "U3") (pin "H1") (pinfunction "VSS_H1") (pintype "passive"))
      (node (ref "U3") (pin "H11") (pinfunction "VSS_H11") (pintype "passive"))
      (node (ref "U3") (pin "H13") (pinfunction "VSS_H13") (pintype "passive"))
      (node (ref "U3") (pin "H15") (pinfunction "VSS_H15") (pintype "passive"))
      (node (ref "U3") (pin "H17") (pinfunction "VSS_H17") (pintype "passive"))
      (node (ref "U3") (pin "H19") (pinfunction "VSS_H19") (pintype "passive"))
      (node (ref "U3") (pin "H21") (pinfunction "VSS_H21") (pintype "passive"))
      (node (ref "U3") (pin "H22") (pinfunction "VSS_H22") (pintype "passive"))
      (node (ref "U3") (pin "H3") (pinfunction "VSS_H3") (pintype "passive"))
      (node (ref "U3") (pin "H5") (pinfunction "VSS_H5") (pintype "passive"))
      (node (ref "U3") (pin "H7") (pinfunction "VSS_H7") (pintype "passive"))
      (node (ref "U3") (pin "H9") (pinfunction "VSS_H9") (pintype "passive"))
      (node (ref "U3") (pin "J10") (pinfunction "VSS_J10") (pintype "passive"))
      (node (ref "U3") (pin "J12") (pinfunction "VSS_J12") (pintype "passive"))
      (node (ref "U3") (pin "J14") (pinfunction "VSS_J14") (pintype "passive"))
      (node (ref "U3") (pin "J16") (pinfunction "VSS_J16") (pintype "passive"))
      (node (ref "U3") (pin "J18") (pinfunction "VSS_J18") (pintype "passive"))
      (node (ref "U3") (pin "J2") (pinfunction "VSS_J2") (pintype "passive"))
      (node (ref "U3") (pin "J20") (pinfunction "VSS_J20") (pintype "passive"))
      (node (ref "U3") (pin "J4") (pinfunction "VSS_J4") (pintype "passive"))
      (node (ref "U3") (pin "J6") (pinfunction "VSS_J6") (pintype "passive"))
      (node (ref "U3") (pin "J8") (pinfunction "VSS_J8") (pintype "passive"))
      (node (ref "U3") (pin "K1") (pinfunction "VSS_K1") (pintype "passive"))
      (node (ref "U3") (pin "K11") (pinfunction "VSS_K11") (pintype "passive"))
      (node (ref "U3") (pin "K13") (pinfunction "VSS_K13") (pintype "passive"))
      (node (ref "U3") (pin "K15") (pinfunction "VSS_K15") (pintype "passive"))
      (node (ref "U3") (pin "K17") (pinfunction "VSS_K17") (pintype "passive"))
      (node (ref "U3") (pin "K19") (pinfunction "VSS_K19") (pintype "passive"))
      (node (ref "U3") (pin "K21") (pinfunction "VSS_K21") (pintype "passive"))
      (node (ref "U3") (pin "K22") (pinfunction "VSS_K22") (pintype "passive"))
      (node (ref "U3") (pin "K3") (pinfunction "VSS_K3") (pintype "passive"))
      (node (ref "U3") (pin "K5") (pinfunction "VSS_K5") (pintype "passive"))
      (node (ref "U3") (pin "K7") (pinfunction "VSS_K7") (pintype "passive"))
      (node (ref "U3") (pin "K9") (pinfunction "VSS_K9") (pintype "passive"))
      (node (ref "U3") (pin "L10") (pinfunction "VSS_L10") (pintype "passive"))
      (node (ref "U3") (pin "L12") (pinfunction "VSS_L12") (pintype "passive"))
      (node (ref "U3") (pin "L14") (pinfunction "VSS_L14") (pintype "passive"))
      (node (ref "U3") (pin "L16") (pinfunction "VSS_L16") (pintype "passive"))
      (node (ref "U3") (pin "L18") (pinfunction "VSS_L18") (pintype "passive"))
      (node (ref "U3") (pin "L2") (pinfunction "VSS_L2") (pintype "passive"))
      (node (ref "U3") (pin "L20") (pinfunction "VSS_L20") (pintype "passive"))
      (node (ref "U3") (pin "L4") (pinfunction "VSS_L4") (pintype "passive"))
      (node (ref "U3") (pin "L6") (pinfunction "VSS_L6") (pintype "passive"))
      (node (ref "U3") (pin "L8") (pinfunction "VSS_L8") (pintype "passive"))
      (node (ref "U3") (pin "M1") (pinfunction "VSS_M1") (pintype "passive"))
      (node (ref "U3") (pin "M11") (pinfunction "VSS_M11") (pintype "passive"))
      (node (ref "U3") (pin "M13") (pinfunction "VSS_M13") (pintype "passive"))
      (node (ref "U3") (pin "M15") (pinfunction "VSS_M15") (pintype "passive"))
      (node (ref "U3") (pin "M17") (pinfunction "VSS_M17") (pintype "passive"))
      (node (ref "U3") (pin "M19") (pinfunction "VSS_M19") (pintype "passive"))
      (node (ref "U3") (pin "M21") (pinfunction "VSS_M21") (pintype "passive"))
      (node (ref "U3") (pin "M3") (pinfunction "VSS_M3") (pintype "passive"))
      (node (ref "U3") (pin "M5") (pinfunction "VSS_M5") (pintype "passive"))
      (node (ref "U3") (pin "M7") (pinfunction "VSS_M7") (pintype "passive"))
      (node (ref "U3") (pin "M9") (pinfunction "VSS_M9") (pintype "passive"))
      (node (ref "U3") (pin "N10") (pinfunction "VSS_N10") (pintype "passive"))
      (node (ref "U3") (pin "N12") (pinfunction "VSS_N12") (pintype "passive"))
      (node (ref "U3") (pin "N14") (pinfunction "VSS_N14") (pintype "passive"))
      (node (ref "U3") (pin "N16") (pinfunction "VSS_N16") (pintype "passive"))
      (node (ref "U3") (pin "N18") (pinfunction "VSS_N18") (pintype "passive"))
      (node (ref "U3") (pin "N2") (pinfunction "VSS_N2") (pintype "passive"))
      (node (ref "U3") (pin "N4") (pinfunction "VSS_N4") (pintype "passive"))
      (node (ref "U3") (pin "N6") (pinfunction "VSS_N6") (pintype "passive"))
      (node (ref "U3") (pin "N8") (pinfunction "VSS_N8") (pintype "passive"))
      (node (ref "U3") (pin "P1") (pinfunction "VSS_P1") (pintype "passive"))
      (node (ref "U3") (pin "P11") (pinfunction "VSS_P11") (pintype "passive"))
      (node (ref "U3") (pin "P13") (pinfunction "VSS_P13") (pintype "passive"))
      (node (ref "U3") (pin "P15") (pinfunction "VSS_P15") (pintype "passive"))
      (node (ref "U3") (pin "P17") (pinfunction "VSS_P17") (pintype "passive"))
      (node (ref "U3") (pin "P19") (pinfunction "VSS_P19") (pintype "passive"))
      (node (ref "U3") (pin "P21") (pinfunction "VSS_P21") (pintype "passive"))
      (node (ref "U3") (pin "P22") (pinfunction "VSS_P22") (pintype "passive"))
      (node (ref "U3") (pin "P3") (pinfunction "VSS_P3") (pintype "passive"))
      (node (ref "U3") (pin "P5") (pinfunction "VSS_P5") (pintype "passive"))
      (node (ref "U3") (pin "P7") (pinfunction "VSS_P7") (pintype "passive"))
      (node (ref "U3") (pin "P9") (pinfunction "VSS_P9") (pintype "passive"))
      (node (ref "U3") (pin "R10") (pinfunction "VSS_R10") (pintype "passive"))
      (node (ref "U3") (pin "R12") (pinfunction "VSS_R12") (pintype "passive"))
      (node (ref "U3") (pin "R14") (pinfunction "VSS_R14") (pintype "passive"))
      (node (ref "U3") (pin "R16") (pinfunction "VSS_R16") (pintype "passive"))
      (node (ref "U3") (pin "R18") (pinfunction "VSS_R18") (pintype "passive"))
      (node (ref "U3") (pin "R2") (pinfunction "VSS_R2") (pintype "passive"))
      (node (ref "U3") (pin "R20") (pinfunction "VSS_R20") (pintype "passive"))
      (node (ref "U3") (pin "R4") (pinfunction "VSS_R4") (pintype "passive"))
      (node (ref "U3") (pin "R6") (pinfunction "VSS_R6") (pintype "passive"))
      (node (ref "U3") (pin "R8") (pinfunction "VSS_R8") (pintype "passive"))
      (node (ref "U3") (pin "T1") (pinfunction "VSS_T1") (pintype "passive"))
      (node (ref "U3") (pin "T11") (pinfunction "VSS_T11") (pintype "passive"))
      (node (ref "U3") (pin "T13") (pinfunction "VSS_T13") (pintype "passive"))
      (node (ref "U3") (pin "T15") (pinfunction "VSS_T15") (pintype "passive"))
      (node (ref "U3") (pin "T17") (pinfunction "VSS_T17") (pintype "passive"))
      (node (ref "U3") (pin "T19") (pinfunction "VSS_T19") (pintype "passive"))
      (node (ref "U3") (pin "T21") (pinfunction "VSS_T21") (pintype "passive"))
      (node (ref "U3") (pin "T22") (pinfunction "VSS_T22") (pintype "passive"))
      (node (ref "U3") (pin "T3") (pinfunction "VSS_T3") (pintype "passive"))
      (node (ref "U3") (pin "T5") (pinfunction "VSS_T5") (pintype "passive"))
      (node (ref "U3") (pin "T7") (pinfunction "VSS_T7") (pintype "passive"))
      (node (ref "U3") (pin "T9") (pinfunction "VSS_T9") (pintype "passive"))
      (node (ref "U3") (pin "U10") (pinfunction "VSS_U10") (pintype "passive"))
      (node (ref "U3") (pin "U12") (pinfunction "VSS_U12") (pintype "passive"))
      (node (ref "U3") (pin "U14") (pinfunction "VSS_U14") (pintype "passive"))
      (node (ref "U3") (pin "U16") (pinfunction "VSS_U16") (pintype "passive"))
      (node (ref "U3") (pin "U18") (pinfunction "VSS_U18") (pintype "passive"))
      (node (ref "U3") (pin "U2") (pinfunction "VSS_U2") (pintype "passive"))
      (node (ref "U3") (pin "U20") (pinfunction "VSS_U20") (pintype "passive"))
      (node (ref "U3") (pin "U4") (pinfunction "VSS_U4") (pintype "passive"))
      (node (ref "U3") (pin "U6") (pinfunction "VSS_U6") (pintype "passive"))
      (node (ref "U3") (pin "U8") (pinfunction "VSS_U8") (pintype "passive"))
      (node (ref "U3") (pin "V1") (pinfunction "VSS_V1") (pintype "passive"))
      (node (ref "U3") (pin "V11") (pinfunction "VSS_V11") (pintype "passive"))
      (node (ref "U3") (pin "V13") (pinfunction "VSS_V13") (pintype "passive"))
      (node (ref "U3") (pin "V15") (pinfunction "VSS_V15") (pintype "passive"))
      (node (ref "U3") (pin "V17") (pinfunction "VSS_V17") (pintype "passive"))
      (node (ref "U3") (pin "V19") (pinfunction "VSS_V19") (pintype "passive"))
      (node (ref "U3") (pin "V21") (pinfunction "VSS_V21") (pintype "passive"))
      (node (ref "U3") (pin "V22") (pinfunction "VSS_V22") (pintype "passive"))
      (node (ref "U3") (pin "V3") (pinfunction "VSS_V3") (pintype "passive"))
      (node (ref "U3") (pin "V5") (pinfunction "VSS_V5") (pintype "passive"))
      (node (ref "U3") (pin "V7") (pinfunction "VSS_V7") (pintype "passive"))
      (node (ref "U3") (pin "V9") (pinfunction "VSS_V9") (pintype "passive"))
      (node (ref "U3") (pin "W10") (pinfunction "VSS_W10") (pintype "passive"))
      (node (ref "U3") (pin "W12") (pinfunction "VSS_W12") (pintype "passive"))
      (node (ref "U3") (pin "W14") (pinfunction "VSS_W14") (pintype "passive"))
      (node (ref "U3") (pin "W16") (pinfunction "VSS_W16") (pintype "passive"))
      (node (ref "U3") (pin "W18") (pinfunction "VSS_W18") (pintype "passive"))
      (node (ref "U3") (pin "W2") (pinfunction "VSS_W2") (pintype "passive"))
      (node (ref "U3") (pin "W20") (pinfunction "VSS_W20") (pintype "passive"))
      (node (ref "U3") (pin "W4") (pinfunction "VSS_W4") (pintype "passive"))
      (node (ref "U3") (pin "W6") (pinfunction "VSS_W6") (pintype "passive"))
      (node (ref "U3") (pin "W8") (pinfunction "VSS_W8") (pintype "passive"))
      (node (ref "U3") (pin "Y1") (pinfunction "VSS_Y1") (pintype "passive"))
      (node (ref "U3") (pin "Y11") (pinfunction "VSS_Y11") (pintype "passive"))
      (node (ref "U3") (pin "Y13") (pinfunction "VSS_Y13") (pintype "passive"))
      (node (ref "U3") (pin "Y15") (pinfunction "VSS_Y15") (pintype "passive"))
      (node (ref "U3") (pin "Y17") (pinfunction "VSS_Y17") (pintype "passive"))
      (node (ref "U3") (pin "Y19") (pinfunction "VSS_Y19") (pintype "passive"))
      (node (ref "U3") (pin "Y21") (pinfunction "VSS_Y21") (pintype "passive"))
      (node (ref "U3") (pin "Y22") (pinfunction "VSS_Y22") (pintype "passive"))
      (node (ref "U3") (pin "Y3") (pinfunction "VSS_Y3") (pintype "passive"))
      (node (ref "U3") (pin "Y5") (pinfunction "VSS_Y5") (pintype "passive"))
      (node (ref "U3") (pin "Y7") (pinfunction "VSS_Y7") (pintype "passive"))
      (node (ref "U3") (pin "Y9") (pinfunction "VSS_Y9") (pintype "passive"))
      (node (ref "U4") (pin "A10") (pinfunction "VSS_A10") (pintype "passive"))
      (node (ref "U4") (pin "A12") (pinfunction "VSS_A12") (pintype "passive"))
      (node (ref "U4") (pin "A14") (pinfunction "VSS_A14") (pintype "passive"))
      (node (ref "U4") (pin "A16") (pinfunction "VSS_A16") (pintype "passive"))
      (node (ref "U4") (pin "A18") (pinfunction "VSS_A18") (pintype "passive"))
      (node (ref "U4") (pin "A2") (pinfunction "VSS_A2") (pintype "passive"))
      (node (ref "U4") (pin "A20") (pinfunction "VSS_A20") (pintype "passive"))
      (node (ref "U4") (pin "A4") (pinfunction "VSS_A4") (pintype "passive"))
      (node (ref "U4") (pin "A6") (pinfunction "VSS_A6") (pintype "passive"))
      (node (ref "U4") (pin "A8") (pinfunction "VSS_A8") (pintype "passive"))
      (node (ref "U4") (pin "AA10") (pinfunction "VSS_AA10") (pintype "passive"))
      (node (ref "U4") (pin "AA12") (pinfunction "VSS_AA12") (pintype "passive"))
      (node (ref "U4") (pin "AA14") (pinfunction "VSS_AA14") (pintype "passive"))
      (node (ref "U4") (pin "AA16") (pinfunction "VSS_AA16") (pintype "passive"))
      (node (ref "U4") (pin "AA18") (pinfunction "VSS_AA18") (pintype "passive"))
      (node (ref "U4") (pin "AA2") (pinfunction "VSS_AA2") (pintype "passive"))
      (node (ref "U4") (pin "AA4") (pinfunction "VSS_AA4") (pintype "passive"))
      (node (ref "U4") (pin "AA6") (pinfunction "VSS_AA6") (pintype "passive"))
      (node (ref "U4") (pin "AA8") (pinfunction "VSS_AA8") (pintype "passive"))
      (node (ref "U4") (pin "AB11") (pinfunction "VSS_AB11") (pintype "passive"))
      (node (ref "U4") (pin "AB13") (pinfunction "VSS_AB13") (pintype "passive"))
      (node (ref "U4") (pin "AB15") (pinfunction "VSS_AB15") (pintype "passive"))
      (node (ref "U4") (pin "AB17") (pinfunction "VSS_AB17") (pintype "passive"))
      (node (ref "U4") (pin "AB3") (pinfunction "VSS_AB3") (pintype "passive"))
      (node (ref "U4") (pin "AB5") (pinfunction "VSS_AB5") (pintype "passive"))
      (node (ref "U4") (pin "AB7") (pinfunction "VSS_AB7") (pintype "passive"))
      (node (ref "U4") (pin "AB9") (pinfunction "VSS_AB9") (pintype "passive"))
      (node (ref "U4") (pin "B1") (pinfunction "VSS_B1") (pintype "passive"))
      (node (ref "U4") (pin "B11") (pinfunction "VSS_B11") (pintype "passive"))
      (node (ref "U4") (pin "B13") (pinfunction "VSS_B13") (pintype "passive"))
      (node (ref "U4") (pin "B15") (pinfunction "VSS_B15") (pintype "passive"))
      (node (ref "U4") (pin "B17") (pinfunction "VSS_B17") (pintype "passive"))
      (node (ref "U4") (pin "B19") (pinfunction "VSS_B19") (pintype "passive"))
      (node (ref "U4") (pin "B21") (pinfunction "VSS_B21") (pintype "passive"))
      (node (ref "U4") (pin "B22") (pinfunction "VSS_B22") (pintype "passive"))
      (node (ref "U4") (pin "B3") (pinfunction "VSS_B3") (pintype "passive"))
      (node (ref "U4") (pin "B5") (pinfunction "VSS_B5") (pintype "passive"))
      (node (ref "U4") (pin "B7") (pinfunction "VSS_B7") (pintype "passive"))
      (node (ref "U4") (pin "B9") (pinfunction "VSS_B9") (pintype "passive"))
      (node (ref "U4") (pin "C10") (pinfunction "VSS_C10") (pintype "passive"))
      (node (ref "U4") (pin "C12") (pinfunction "VSS_C12") (pintype "passive"))
      (node (ref "U4") (pin "C14") (pinfunction "VSS_C14") (pintype "passive"))
      (node (ref "U4") (pin "C16") (pinfunction "VSS_C16") (pintype "passive"))
      (node (ref "U4") (pin "C18") (pinfunction "VSS_C18") (pintype "passive"))
      (node (ref "U4") (pin "C2") (pinfunction "VSS_C2") (pintype "passive"))
      (node (ref "U4") (pin "C20") (pinfunction "VSS_C20") (pintype "passive"))
      (node (ref "U4") (pin "C4") (pinfunction "VSS_C4") (pintype "passive"))
      (node (ref "U4") (pin "C6") (pinfunction "VSS_C6") (pintype "passive"))
      (node (ref "U4") (pin "C8") (pinfunction "VSS_C8") (pintype "passive"))
      (node (ref "U4") (pin "D1") (pinfunction "VSS_D1") (pintype "passive"))
      (node (ref "U4") (pin "D11") (pinfunction "VSS_D11") (pintype "passive"))
      (node (ref "U4") (pin "D13") (pinfunction "VSS_D13") (pintype "passive"))
      (node (ref "U4") (pin "D15") (pinfunction "VSS_D15") (pintype "passive"))
      (node (ref "U4") (pin "D17") (pinfunction "VSS_D17") (pintype "passive"))
      (node (ref "U4") (pin "D19") (pinfunction "VSS_D19") (pintype "passive"))
      (node (ref "U4") (pin "D21") (pinfunction "VSS_D21") (pintype "passive"))
      (node (ref "U4") (pin "D22") (pinfunction "VSS_D22") (pintype "passive"))
      (node (ref "U4") (pin "D3") (pinfunction "VSS_D3") (pintype "passive"))
      (node (ref "U4") (pin "D5") (pinfunction "VSS_D5") (pintype "passive"))
      (node (ref "U4") (pin "D7") (pinfunction "VSS_D7") (pintype "passive"))
      (node (ref "U4") (pin "D9") (pinfunction "VSS_D9") (pintype "passive"))
      (node (ref "U4") (pin "E10") (pinfunction "VSS_E10") (pintype "passive"))
      (node (ref "U4") (pin "E12") (pinfunction "VSS_E12") (pintype "passive"))
      (node (ref "U4") (pin "E14") (pinfunction "VSS_E14") (pintype "passive"))
      (node (ref "U4") (pin "E16") (pinfunction "VSS_E16") (pintype "passive"))
      (node (ref "U4") (pin "E18") (pinfunction "VSS_E18") (pintype "passive"))
      (node (ref "U4") (pin "E2") (pinfunction "VSS_E2") (pintype "passive"))
      (node (ref "U4") (pin "E20") (pinfunction "VSS_E20") (pintype "passive"))
      (node (ref "U4") (pin "E4") (pinfunction "VSS_E4") (pintype "passive"))
      (node (ref "U4") (pin "E6") (pinfunction "VSS_E6") (pintype "passive"))
      (node (ref "U4") (pin "E8") (pinfunction "VSS_E8") (pintype "passive"))
      (node (ref "U4") (pin "F1") (pinfunction "VSS_F1") (pintype "passive"))
      (node (ref "U4") (pin "F11") (pinfunction "VSS_F11") (pintype "passive"))
      (node (ref "U4") (pin "F13") (pinfunction "VSS_F13") (pintype "passive"))
      (node (ref "U4") (pin "F15") (pinfunction "VSS_F15") (pintype "passive"))
      (node (ref "U4") (pin "F17") (pinfunction "VSS_F17") (pintype "passive"))
      (node (ref "U4") (pin "F19") (pinfunction "VSS_F19") (pintype "passive"))
      (node (ref "U4") (pin "F21") (pinfunction "VSS_F21") (pintype "passive"))
      (node (ref "U4") (pin "F22") (pinfunction "VSS_F22") (pintype "passive"))
      (node (ref "U4") (pin "F3") (pinfunction "VSS_F3") (pintype "passive"))
      (node (ref "U4") (pin "F5") (pinfunction "VSS_F5") (pintype "passive"))
      (node (ref "U4") (pin "F7") (pinfunction "VSS_F7") (pintype "passive"))
      (node (ref "U4") (pin "F9") (pinfunction "VSS_F9") (pintype "passive"))
      (node (ref "U4") (pin "G10") (pinfunction "VSS_G10") (pintype "passive"))
      (node (ref "U4") (pin "G12") (pinfunction "VSS_G12") (pintype "passive"))
      (node (ref "U4") (pin "G14") (pinfunction "VSS_G14") (pintype "passive"))
      (node (ref "U4") (pin "G16") (pinfunction "VSS_G16") (pintype "passive"))
      (node (ref "U4") (pin "G18") (pinfunction "VSS_G18") (pintype "passive"))
      (node (ref "U4") (pin "G2") (pinfunction "VSS_G2") (pintype "passive"))
      (node (ref "U4") (pin "G20") (pinfunction "VSS_G20") (pintype "passive"))
      (node (ref "U4") (pin "G4") (pinfunction "VSS_G4") (pintype "passive"))
      (node (ref "U4") (pin "G6") (pinfunction "VSS_G6") (pintype "passive"))
      (node (ref "U4") (pin "G8") (pinfunction "VSS_G8") (pintype "passive"))
      (node (ref "U4") (pin "H1") (pinfunction "VSS_H1") (pintype "passive"))
      (node (ref "U4") (pin "H11") (pinfunction "VSS_H11") (pintype "passive"))
      (node (ref "U4") (pin "H13") (pinfunction "VSS_H13") (pintype "passive"))
      (node (ref "U4") (pin "H15") (pinfunction "VSS_H15") (pintype "passive"))
      (node (ref "U4") (pin "H17") (pinfunction "VSS_H17") (pintype "passive"))
      (node (ref "U4") (pin "H19") (pinfunction "VSS_H19") (pintype "passive"))
      (node (ref "U4") (pin "H21") (pinfunction "VSS_H21") (pintype "passive"))
      (node (ref "U4") (pin "H22") (pinfunction "VSS_H22") (pintype "passive"))
      (node (ref "U4") (pin "H3") (pinfunction "VSS_H3") (pintype "passive"))
      (node (ref "U4") (pin "H5") (pinfunction "VSS_H5") (pintype "passive"))
      (node (ref "U4") (pin "H7") (pinfunction "VSS_H7") (pintype "passive"))
      (node (ref "U4") (pin "H9") (pinfunction "VSS_H9") (pintype "passive"))
      (node (ref "U4") (pin "J10") (pinfunction "VSS_J10") (pintype "passive"))
      (node (ref "U4") (pin "J12") (pinfunction "VSS_J12") (pintype "passive"))
      (node (ref "U4") (pin "J14") (pinfunction "VSS_J14") (pintype "passive"))
      (node (ref "U4") (pin "J16") (pinfunction "VSS_J16") (pintype "passive"))
      (node (ref "U4") (pin "J18") (pinfunction "VSS_J18") (pintype "passive"))
      (node (ref "U4") (pin "J2") (pinfunction "VSS_J2") (pintype "passive"))
      (node (ref "U4") (pin "J20") (pinfunction "VSS_J20") (pintype "passive"))
      (node (ref "U4") (pin "J4") (pinfunction "VSS_J4") (pintype "passive"))
      (node (ref "U4") (pin "J6") (pinfunction "VSS_J6") (pintype "passive"))
      (node (ref "U4") (pin "J8") (pinfunction "VSS_J8") (pintype "passive"))
      (node (ref "U4") (pin "K1") (pinfunction "VSS_K1") (pintype "passive"))
      (node (ref "U4") (pin "K11") (pinfunction "VSS_K11") (pintype "passive"))
      (node (ref "U4") (pin "K13") (pinfunction "VSS_K13") (pintype "passive"))
      (node (ref "U4") (pin "K15") (pinfunction "VSS_K15") (pintype "passive"))
      (node (ref "U4") (pin "K17") (pinfunction "VSS_K17") (pintype "passive"))
      (node (ref "U4") (pin "K19") (pinfunction "VSS_K19") (pintype "passive"))
      (node (ref "U4") (pin "K21") (pinfunction "VSS_K21") (pintype "passive"))
      (node (ref "U4") (pin "K22") (pinfunction "VSS_K22") (pintype "passive"))
      (node (ref "U4") (pin "K3") (pinfunction "VSS_K3") (pintype "passive"))
      (node (ref "U4") (pin "K5") (pinfunction "VSS_K5") (pintype "passive"))
      (node (ref "U4") (pin "K7") (pinfunction "VSS_K7") (pintype "passive"))
      (node (ref "U4") (pin "K9") (pinfunction "VSS_K9") (pintype "passive"))
      (node (ref "U4") (pin "L10") (pinfunction "VSS_L10") (pintype "passive"))
      (node (ref "U4") (pin "L12") (pinfunction "VSS_L12") (pintype "passive"))
      (node (ref "U4") (pin "L14") (pinfunction "VSS_L14") (pintype "passive"))
      (node (ref "U4") (pin "L16") (pinfunction "VSS_L16") (pintype "passive"))
      (node (ref "U4") (pin "L18") (pinfunction "VSS_L18") (pintype "passive"))
      (node (ref "U4") (pin "L2") (pinfunction "VSS_L2") (pintype "passive"))
      (node (ref "U4") (pin "L20") (pinfunction "VSS_L20") (pintype "passive"))
      (node (ref "U4") (pin "L4") (pinfunction "VSS_L4") (pintype "passive"))
      (node (ref "U4") (pin "L6") (pinfunction "VSS_L6") (pintype "passive"))
      (node (ref "U4") (pin "L8") (pinfunction "VSS_L8") (pintype "passive"))
      (node (ref "U4") (pin "M1") (pinfunction "VSS_M1") (pintype "passive"))
      (node (ref "U4") (pin "M11") (pinfunction "VSS_M11") (pintype "passive"))
      (node (ref "U4") (pin "M13") (pinfunction "VSS_M13") (pintype "passive"))
      (node (ref "U4") (pin "M15") (pinfunction "VSS_M15") (pintype "passive"))
      (node (ref "U4") (pin "M17") (pinfunction "VSS_M17") (pintype "passive"))
      (node (ref "U4") (pin "M19") (pinfunction "VSS_M19") (pintype "passive"))
      (node (ref "U4") (pin "M21") (pinfunction "VSS_M21") (pintype "passive"))
      (node (ref "U4") (pin "M3") (pinfunction "VSS_M3") (pintype "passive"))
      (node (ref "U4") (pin "M5") (pinfunction "VSS_M5") (pintype "passive"))
      (node (ref "U4") (pin "M7") (pinfunction "VSS_M7") (pintype "passive"))
      (node (ref "U4") (pin "M9") (pinfunction "VSS_M9") (pintype "passive"))
      (node (ref "U4") (pin "N10") (pinfunction "VSS_N10") (pintype "passive"))
      (node (ref "U4") (pin "N12") (pinfunction "VSS_N12") (pintype "passive"))
      (node (ref "U4") (pin "N14") (pinfunction "VSS_N14") (pintype "passive"))
      (node (ref "U4") (pin "N16") (pinfunction "VSS_N16") (pintype "passive"))
      (node (ref "U4") (pin "N18") (pinfunction "VSS_N18") (pintype "passive"))
      (node (ref "U4") (pin "N2") (pinfunction "VSS_N2") (pintype "passive"))
      (node (ref "U4") (pin "N4") (pinfunction "VSS_N4") (pintype "passive"))
      (node (ref "U4") (pin "N6") (pinfunction "VSS_N6") (pintype "passive"))
      (node (ref "U4") (pin "N8") (pinfunction "VSS_N8") (pintype "passive"))
      (node (ref "U4") (pin "P1") (pinfunction "VSS_P1") (pintype "passive"))
      (node (ref "U4") (pin "P11") (pinfunction "VSS_P11") (pintype "passive"))
      (node (ref "U4") (pin "P13") (pinfunction "VSS_P13") (pintype "passive"))
      (node (ref "U4") (pin "P15") (pinfunction "VSS_P15") (pintype "passive"))
      (node (ref "U4") (pin "P17") (pinfunction "VSS_P17") (pintype "passive"))
      (node (ref "U4") (pin "P19") (pinfunction "VSS_P19") (pintype "passive"))
      (node (ref "U4") (pin "P21") (pinfunction "VSS_P21") (pintype "passive"))
      (node (ref "U4") (pin "P22") (pinfunction "VSS_P22") (pintype "passive"))
      (node (ref "U4") (pin "P3") (pinfunction "VSS_P3") (pintype "passive"))
      (node (ref "U4") (pin "P5") (pinfunction "VSS_P5") (pintype "passive"))
      (node (ref "U4") (pin "P7") (pinfunction "VSS_P7") (pintype "passive"))
      (node (ref "U4") (pin "P9") (pinfunction "VSS_P9") (pintype "passive"))
      (node (ref "U4") (pin "R10") (pinfunction "VSS_R10") (pintype "passive"))
      (node (ref "U4") (pin "R12") (pinfunction "VSS_R12") (pintype "passive"))
      (node (ref "U4") (pin "R14") (pinfunction "VSS_R14") (pintype "passive"))
      (node (ref "U4") (pin "R16") (pinfunction "VSS_R16") (pintype "passive"))
      (node (ref "U4") (pin "R18") (pinfunction "VSS_R18") (pintype "passive"))
      (node (ref "U4") (pin "R2") (pinfunction "VSS_R2") (pintype "passive"))
      (node (ref "U4") (pin "R20") (pinfunction "VSS_R20") (pintype "passive"))
      (node (ref "U4") (pin "R4") (pinfunction "VSS_R4") (pintype "passive"))
      (node (ref "U4") (pin "R6") (pinfunction "VSS_R6") (pintype "passive"))
      (node (ref "U4") (pin "R8") (pinfunction "VSS_R8") (pintype "passive"))
      (node (ref "U4") (pin "T1") (pinfunction "VSS_T1") (pintype "passive"))
      (node (ref "U4") (pin "T11") (pinfunction "VSS_T11") (pintype "passive"))
      (node (ref "U4") (pin "T13") (pinfunction "VSS_T13") (pintype "passive"))
      (node (ref "U4") (pin "T15") (pinfunction "VSS_T15") (pintype "passive"))
      (node (ref "U4") (pin "T17") (pinfunction "VSS_T17") (pintype "passive"))
      (node (ref "U4") (pin "T19") (pinfunction "VSS_T19") (pintype "passive"))
      (node (ref "U4") (pin "T21") (pinfunction "VSS_T21") (pintype "passive"))
      (node (ref "U4") (pin "T22") (pinfunction "VSS_T22") (pintype "passive"))
      (node (ref "U4") (pin "T3") (pinfunction "VSS_T3") (pintype "passive"))
      (node (ref "U4") (pin "T5") (pinfunction "VSS_T5") (pintype "passive"))
      (node (ref "U4") (pin "T7") (pinfunction "VSS_T7") (pintype "passive"))
      (node (ref "U4") (pin "T9") (pinfunction "VSS_T9") (pintype "passive"))
      (node (ref "U4") (pin "U10") (pinfunction "VSS_U10") (pintype "passive"))
      (node (ref "U4") (pin "U12") (pinfunction "VSS_U12") (pintype "passive"))
      (node (ref "U4") (pin "U14") (pinfunction "VSS_U14") (pintype "passive"))
      (node (ref "U4") (pin "U16") (pinfunction "VSS_U16") (pintype "passive"))
      (node (ref "U4") (pin "U18") (pinfunction "VSS_U18") (pintype "passive"))
      (node (ref "U4") (pin "U2") (pinfunction "VSS_U2") (pintype "passive"))
      (node (ref "U4") (pin "U20") (pinfunction "VSS_U20") (pintype "passive"))
      (node (ref "U4") (pin "U4") (pinfunction "VSS_U4") (pintype "passive"))
      (node (ref "U4") (pin "U6") (pinfunction "VSS_U6") (pintype "passive"))
      (node (ref "U4") (pin "U8") (pinfunction "VSS_U8") (pintype "passive"))
      (node (ref "U4") (pin "V1") (pinfunction "VSS_V1") (pintype "passive"))
      (node (ref "U4") (pin "V11") (pinfunction "VSS_V11") (pintype "passive"))
      (node (ref "U4") (pin "V13") (pinfunction "VSS_V13") (pintype "passive"))
      (node (ref "U4") (pin "V15") (pinfunction "VSS_V15") (pintype "passive"))
      (node (ref "U4") (pin "V17") (pinfunction "VSS_V17") (pintype "passive"))
      (node (ref "U4") (pin "V19") (pinfunction "VSS_V19") (pintype "passive"))
      (node (ref "U4") (pin "V21") (pinfunction "VSS_V21") (pintype "passive"))
      (node (ref "U4") (pin "V22") (pinfunction "VSS_V22") (pintype "passive"))
      (node (ref "U4") (pin "V3") (pinfunction "VSS_V3") (pintype "passive"))
      (node (ref "U4") (pin "V5") (pinfunction "VSS_V5") (pintype "passive"))
      (node (ref "U4") (pin "V7") (pinfunction "VSS_V7") (pintype "passive"))
      (node (ref "U4") (pin "V9") (pinfunction "VSS_V9") (pintype "passive"))
      (node (ref "U4") (pin "W10") (pinfunction "VSS_W10") (pintype "passive"))
      (node (ref "U4") (pin "W12") (pinfunction "VSS_W12") (pintype "passive"))
      (node (ref "U4") (pin "W14") (pinfunction "VSS_W14") (pintype "passive"))
      (node (ref "U4") (pin "W16") (pinfunction "VSS_W16") (pintype "passive"))
      (node (ref "U4") (pin "W18") (pinfunction "VSS_W18") (pintype "passive"))
      (node (ref "U4") (pin "W2") (pinfunction "VSS_W2") (pintype "passive"))
      (node (ref "U4") (pin "W20") (pinfunction "VSS_W20") (pintype "passive"))
      (node (ref "U4") (pin "W4") (pinfunction "VSS_W4") (pintype "passive"))
      (node (ref "U4") (pin "W6") (pinfunction "VSS_W6") (pintype "passive"))
      (node (ref "U4") (pin "W8") (pinfunction "VSS_W8") (pintype "passive"))
      (node (ref "U4") (pin "Y1") (pinfunction "VSS_Y1") (pintype "passive"))
      (node (ref "U4") (pin "Y11") (pinfunction "VSS_Y11") (pintype "passive"))
      (node (ref "U4") (pin "Y13") (pinfunction "VSS_Y13") (pintype "passive"))
      (node (ref "U4") (pin "Y15") (pinfunction "VSS_Y15") (pintype "passive"))
      (node (ref "U4") (pin "Y17") (pinfunction "VSS_Y17") (pintype "passive"))
      (node (ref "U4") (pin "Y19") (pinfunction "VSS_Y19") (pintype "passive"))
      (node (ref "U4") (pin "Y21") (pinfunction "VSS_Y21") (pintype "passive"))
      (node (ref "U4") (pin "Y22") (pinfunction "VSS_Y22") (pintype "passive"))
      (node (ref "U4") (pin "Y3") (pinfunction "VSS_Y3") (pintype "passive"))
      (node (ref "U4") (pin "Y5") (pinfunction "VSS_Y5") (pintype "passive"))
      (node (ref "U4") (pin "Y7") (pinfunction "VSS_Y7") (pintype "passive"))
      (node (ref "U4") (pin "Y9") (pinfunction "VSS_Y9") (pintype "passive"))
    )
  )
)
